# Schematic.net
KiCad netlist of a schematic drawn in Altium Designer
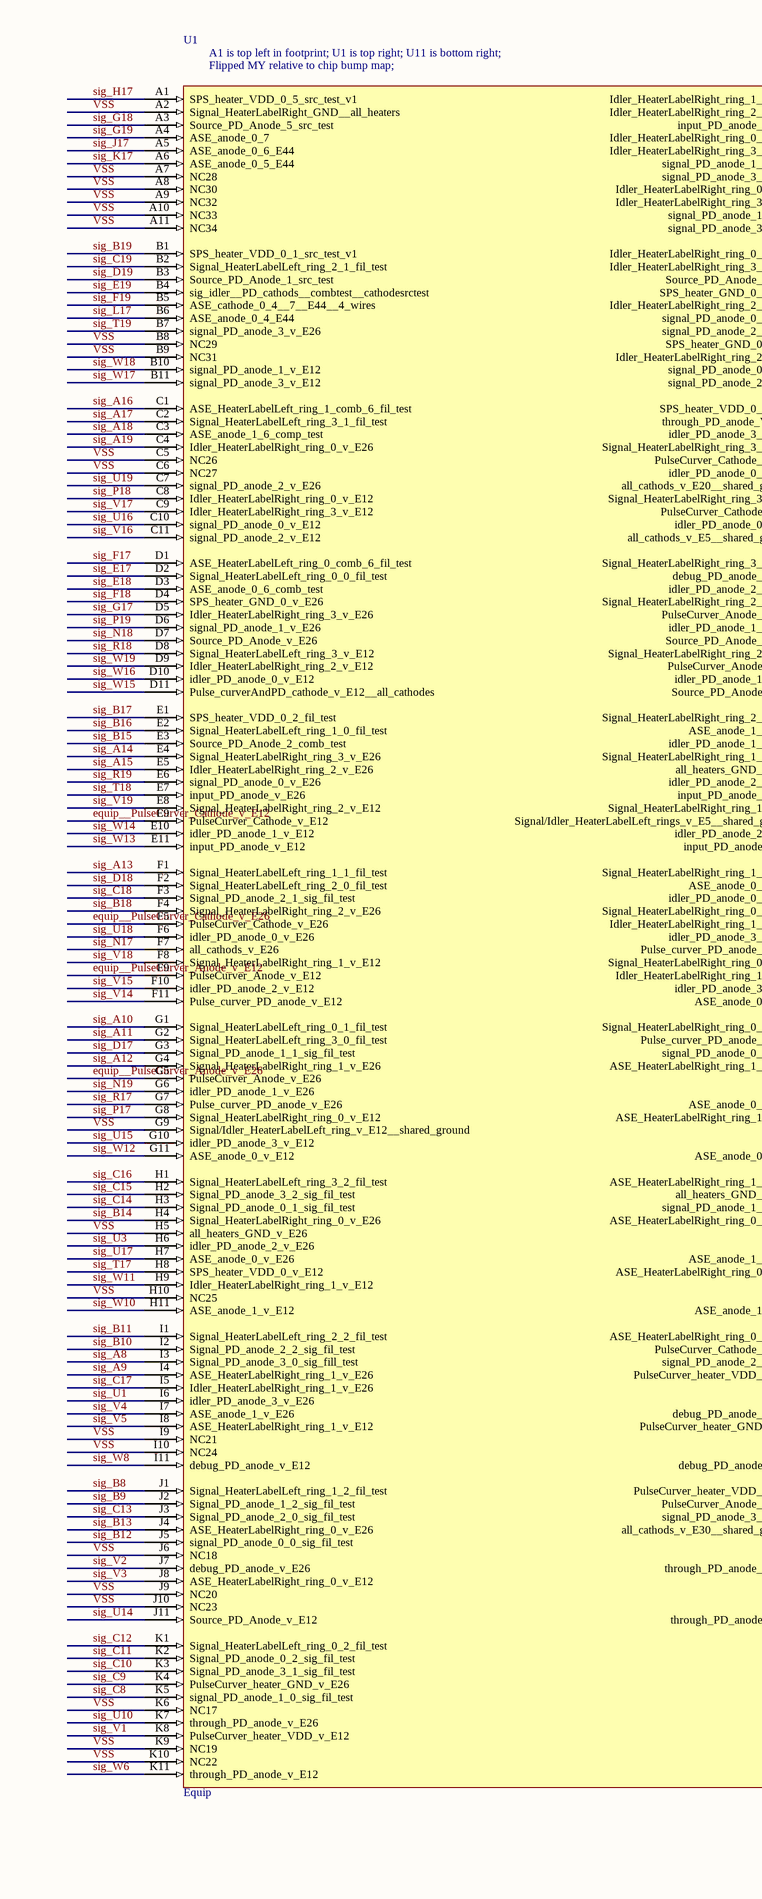
[diagram p0: Schematic.SchDoc, top left]
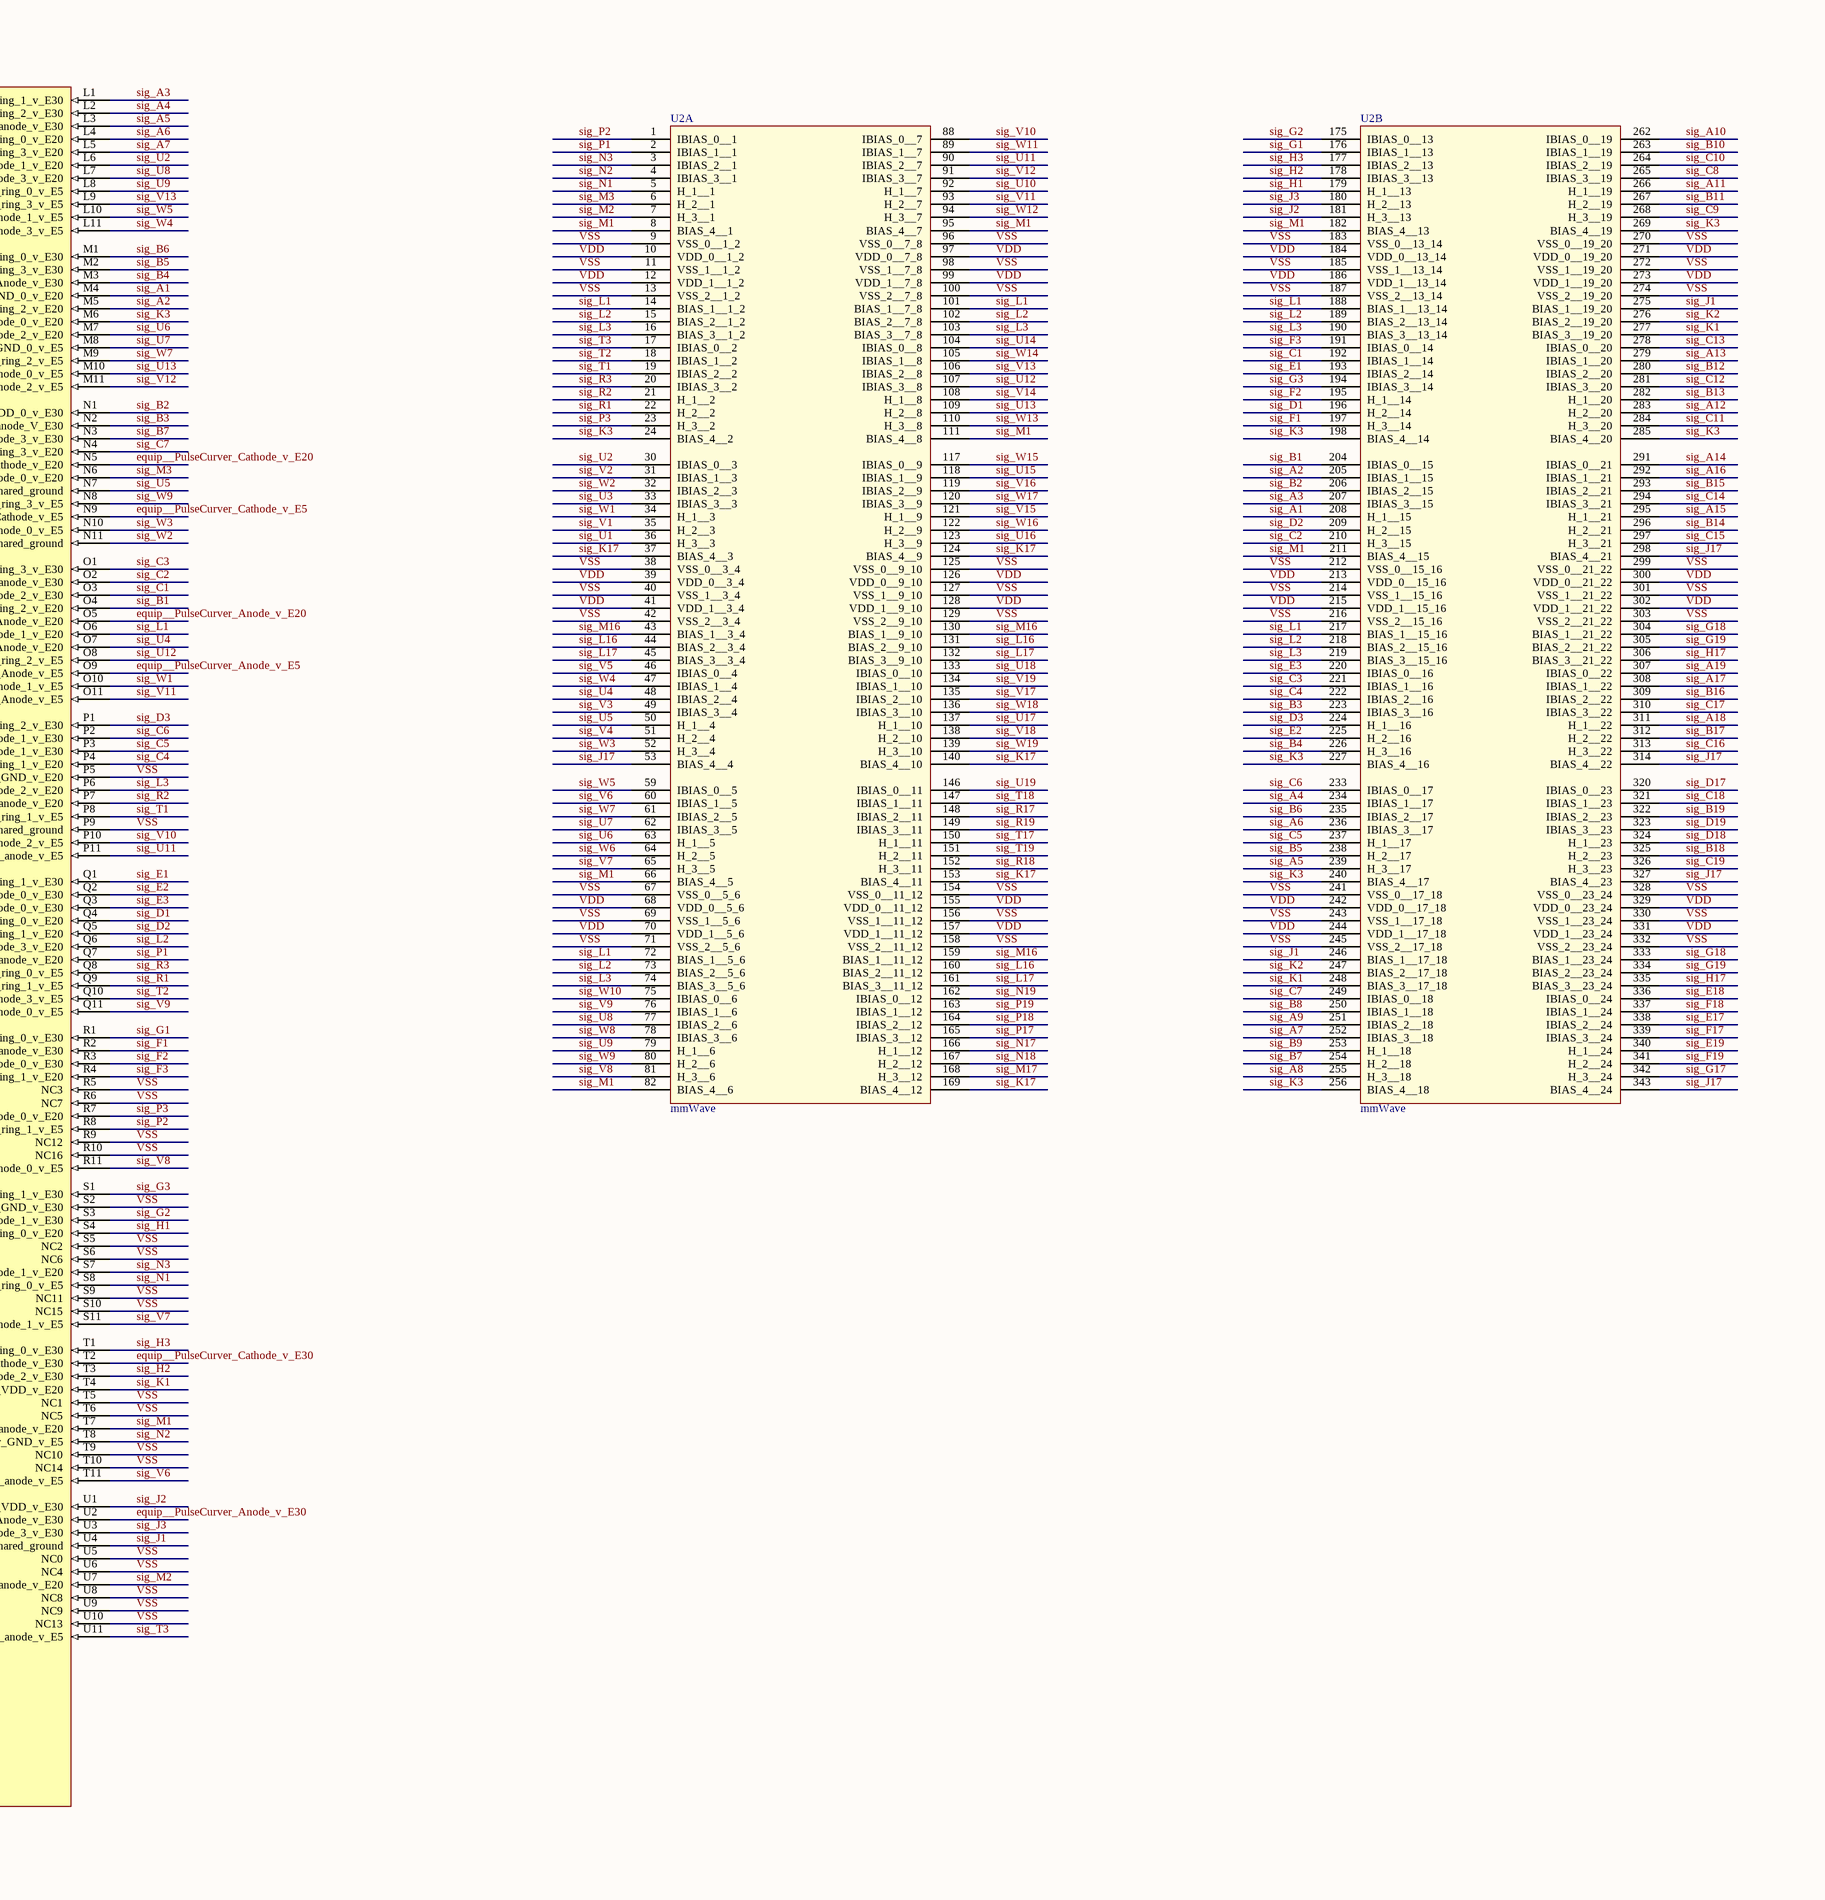
[diagram p1: Schematic.SchDoc, top middle]
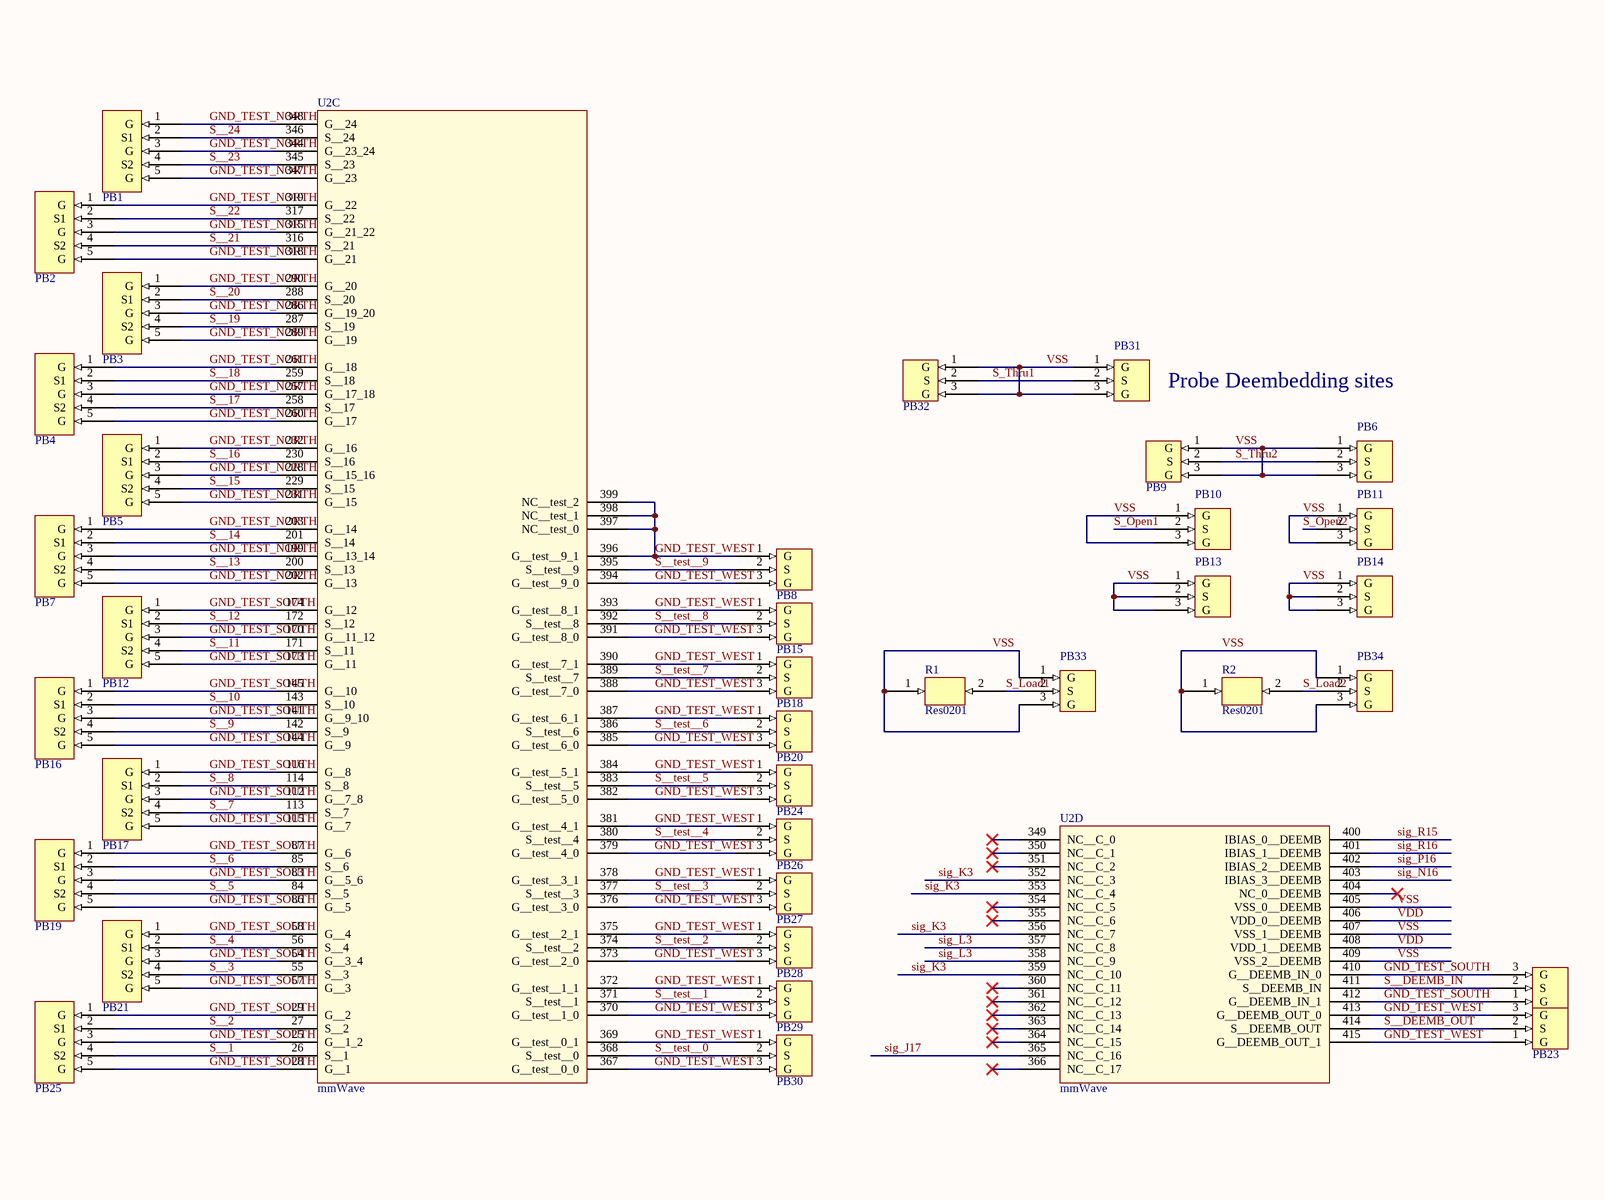
[diagram p2: Schematic.SchDoc, top right]
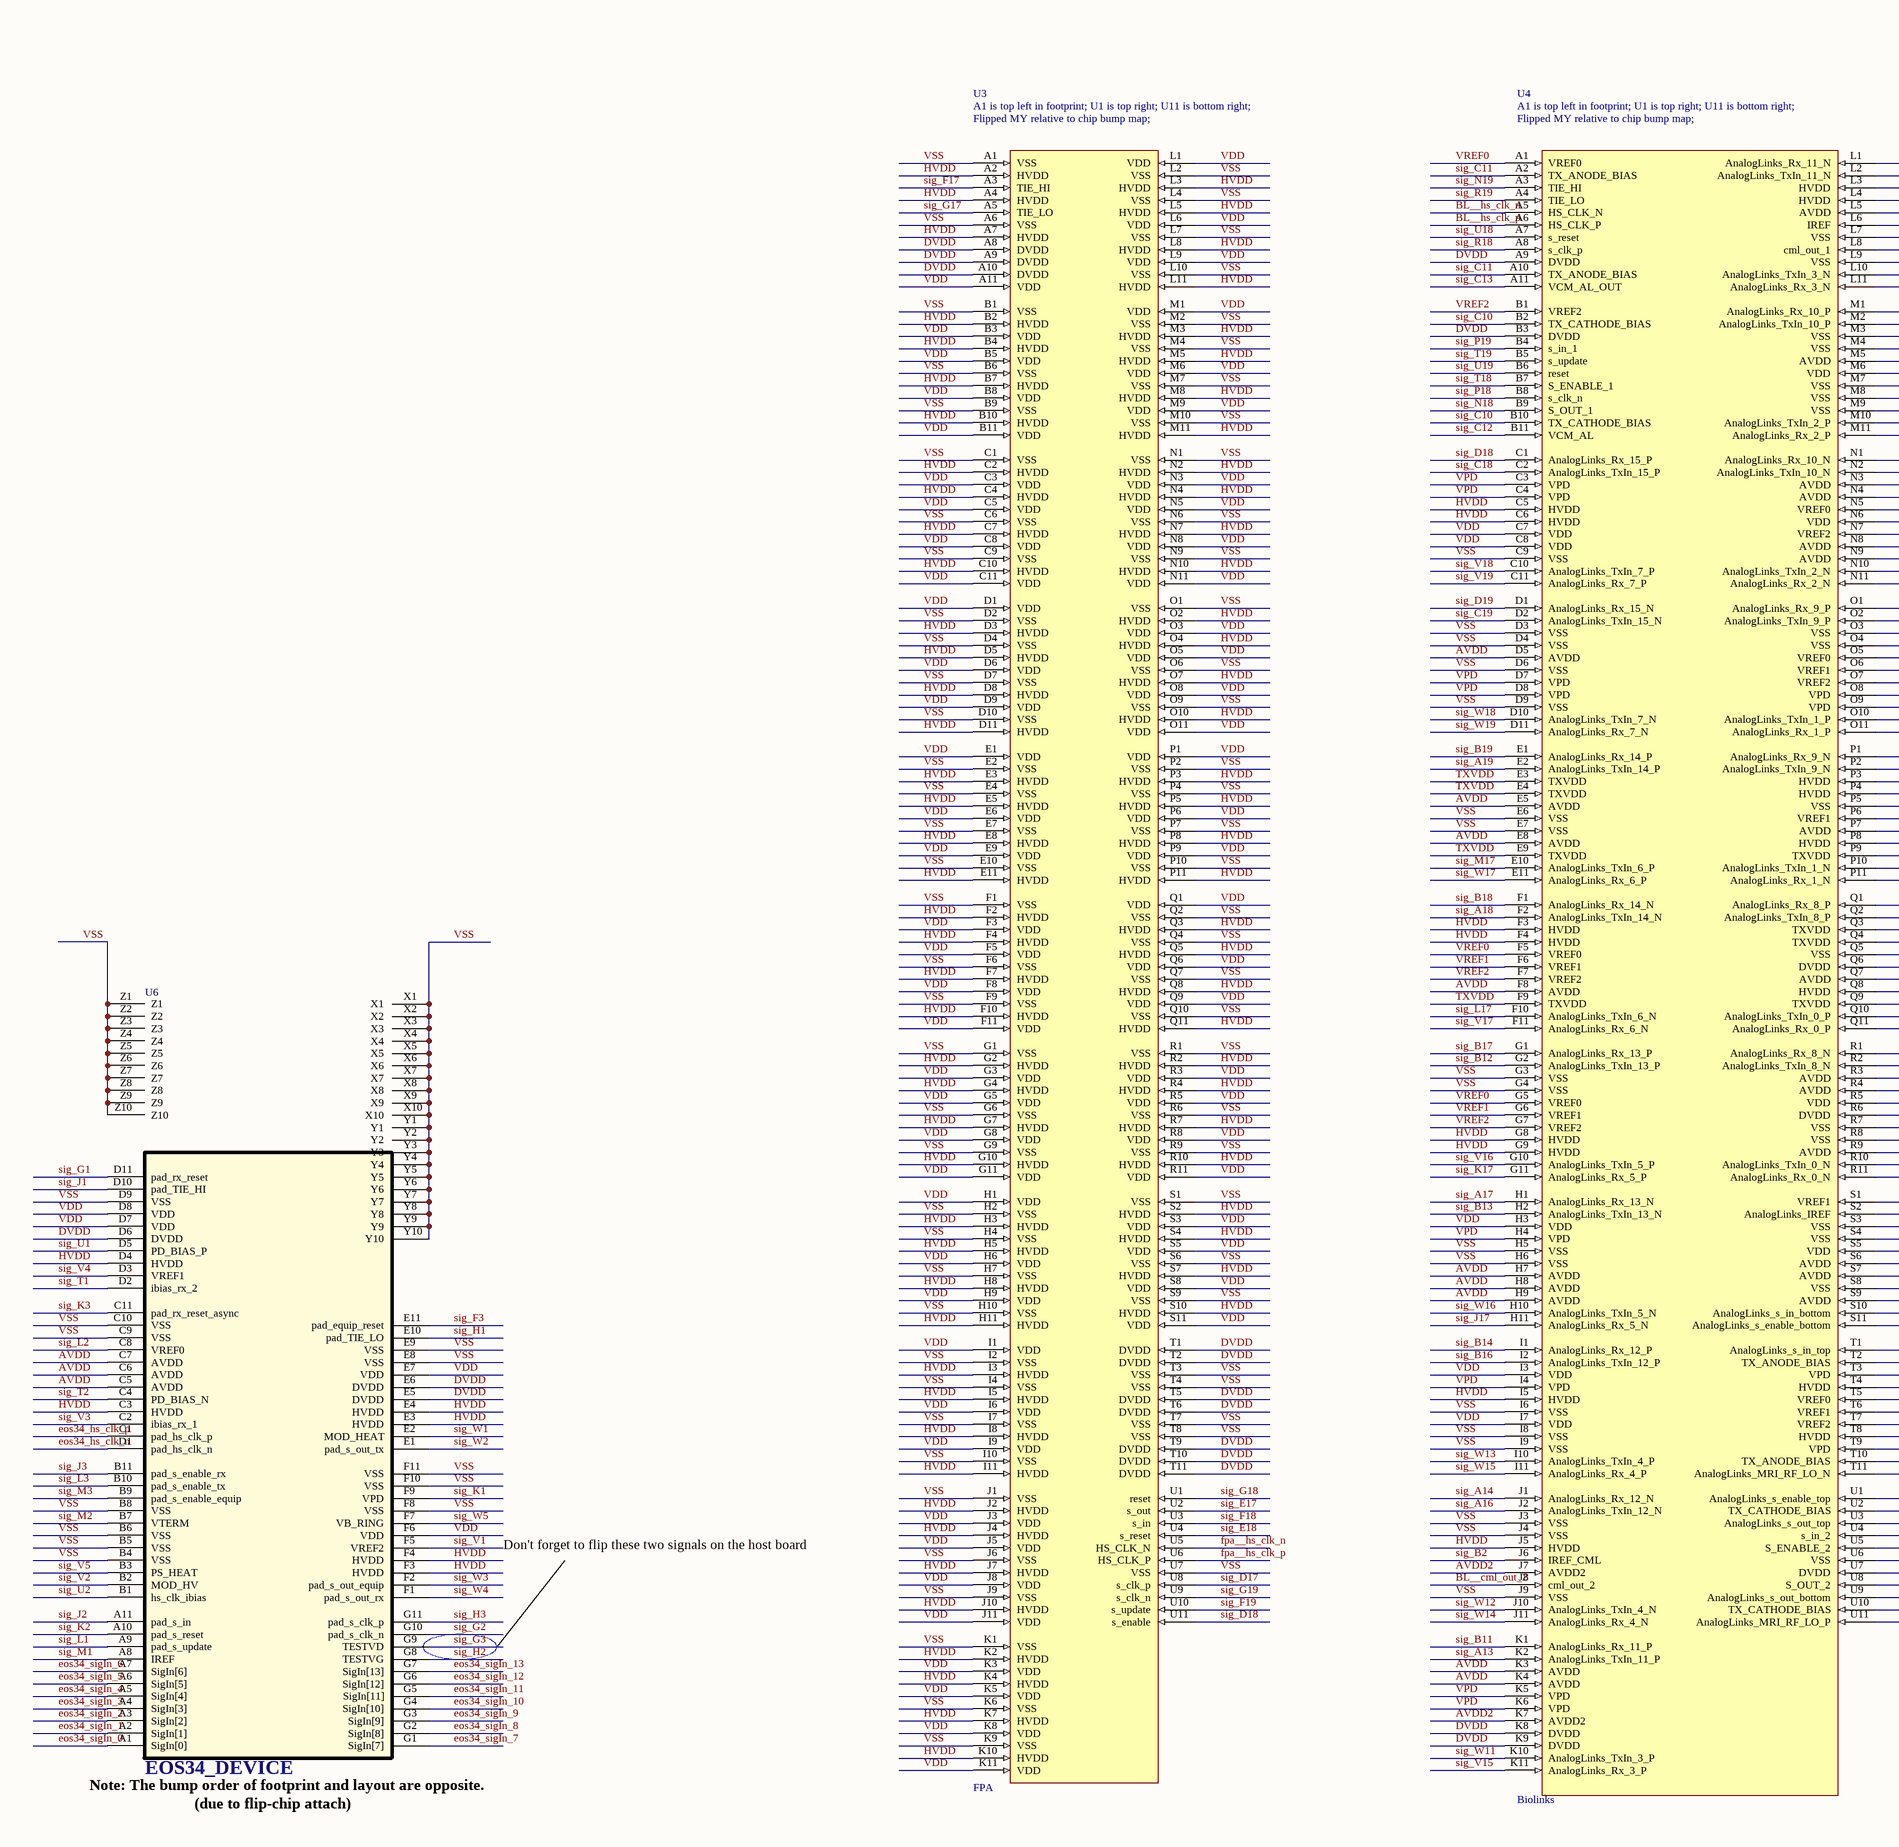
[diagram p3: Schematic.SchDoc, bottom left]
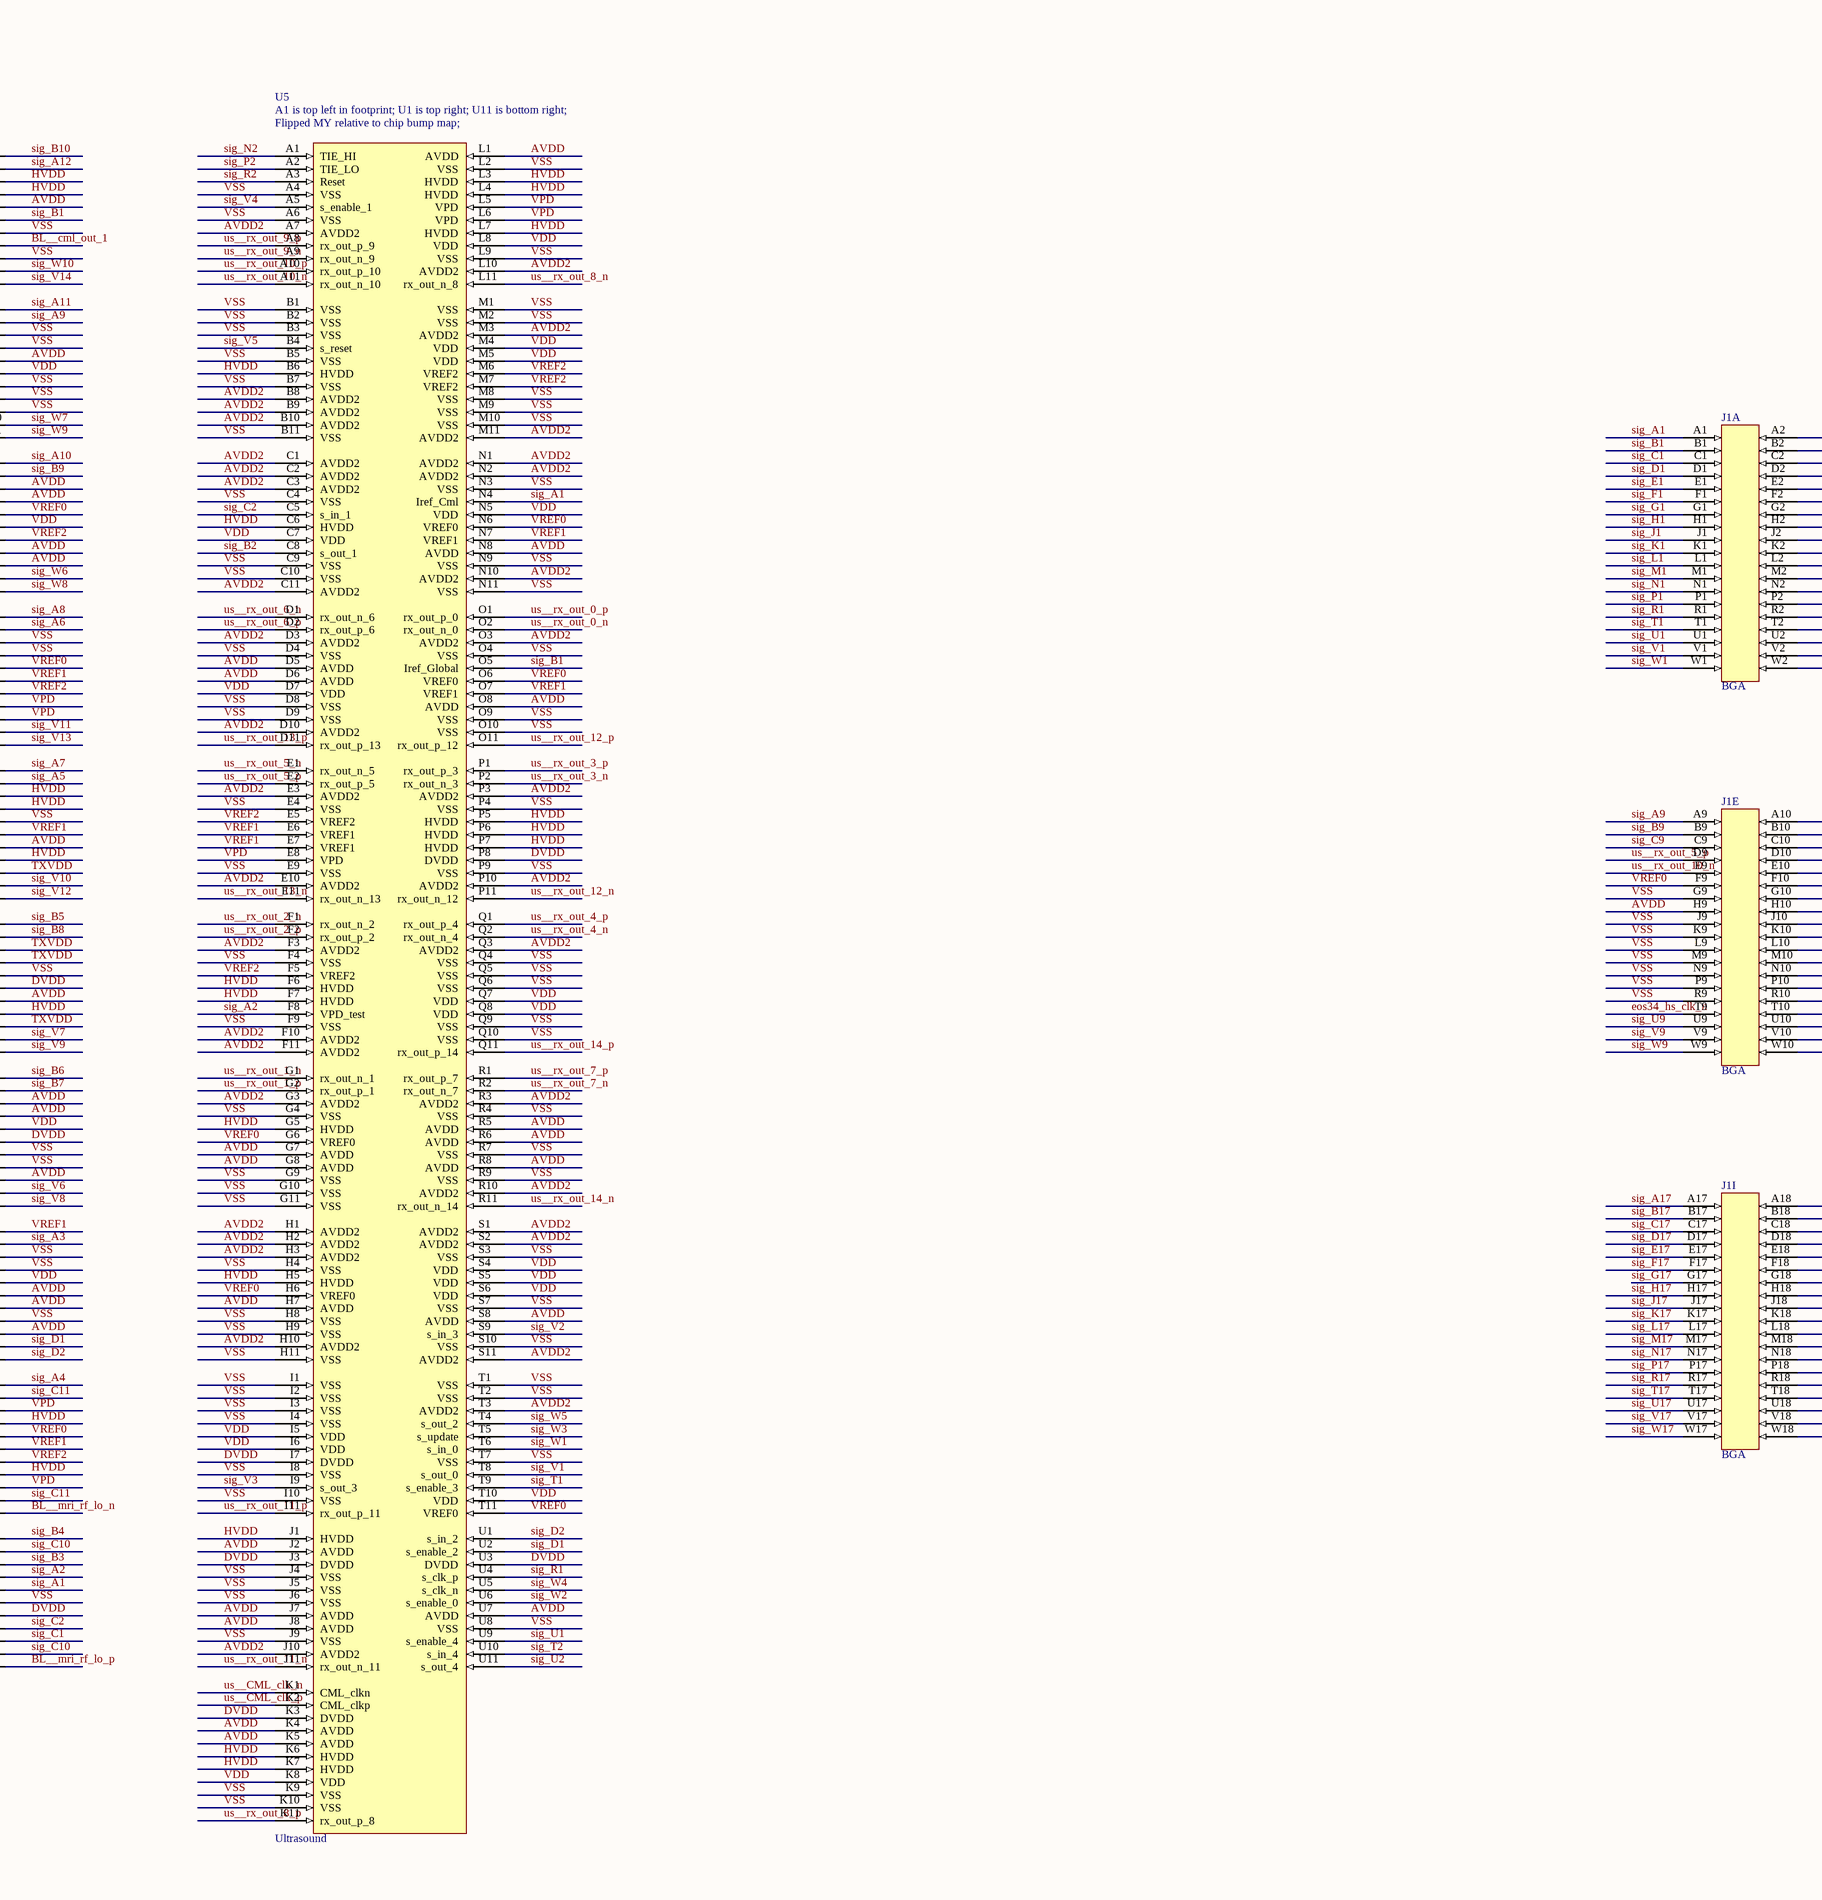
[diagram p4: Schematic.SchDoc, bottom middle]
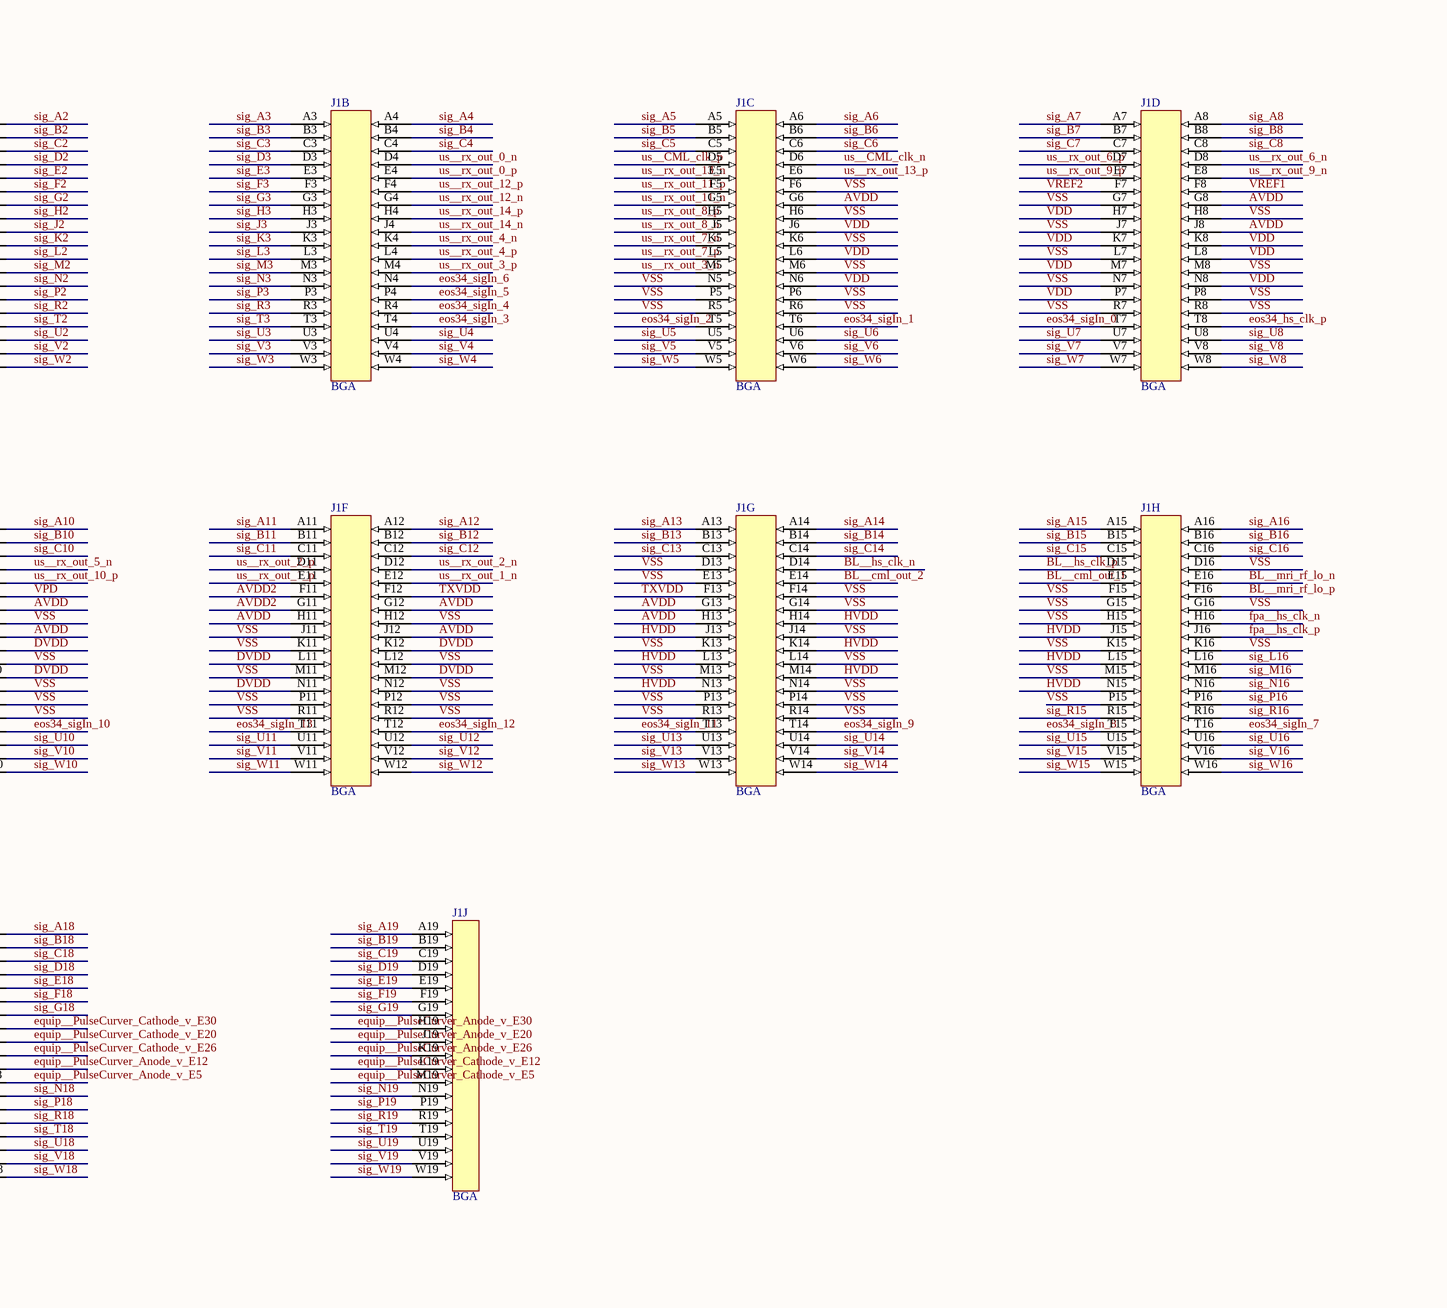
[diagram p5: Schematic.SchDoc, bottom right]

(export (version "E")
  (design (tool "Eeschema 10.0.6"))
  (components
    (comp (ref "J1") (value "BGA") (footprint "BGA361x19") (libsource (lib "Schlib") (part "BGA")))
    (comp (ref "PB1") (value "GSGSG") (footprint "GSGSG_Probe") (libsource (lib "Schlib") (part "GSGSG")))
    (comp (ref "PB2") (value "GSGSG") (footprint "GSGSG_Probe") (libsource (lib "Schlib") (part "GSGSG")))
    (comp (ref "PB3") (value "GSGSG") (footprint "GSGSG_Probe") (libsource (lib "Schlib") (part "GSGSG")))
    (comp (ref "PB4") (value "GSGSG") (footprint "GSGSG_Probe") (libsource (lib "Schlib") (part "GSGSG")))
    (comp (ref "PB5") (value "GSGSG") (footprint "GSGSG_Probe") (libsource (lib "Schlib") (part "GSGSG")))
    (comp (ref "PB6")
      (value "GSG_Probe_Pads")
      (footprint "GSG_Probe")
      (libsource (lib "") (part "GSG_Probe_Pads_1"))
    )
    (comp (ref "PB7") (value "GSGSG") (footprint "GSGSG_Probe") (libsource (lib "Schlib") (part "GSGSG")))
    (comp (ref "PB8")
      (value "GSG_Probe_Pads")
      (footprint "GSG_Probe")
      (libsource (lib "") (part "GSG_Probe_Pads_1"))
    )
    (comp (ref "PB9")
      (value "GSG_Probe_Pads")
      (footprint "GSG_Probe")
      (libsource (lib "") (part "GSG_Probe_Pads_2"))
    )
    (comp (ref "PB10")
      (value "GSG_Probe_Pads")
      (footprint "GSG_Probe")
      (libsource (lib "") (part "GSG_Probe_Pads_1"))
    )
    (comp (ref "PB11")
      (value "GSG_Probe_Pads")
      (footprint "GSG_Probe")
      (libsource (lib "") (part "GSG_Probe_Pads_1"))
    )
    (comp (ref "PB12") (value "GSGSG") (footprint "GSGSG_Probe") (libsource (lib "Schlib") (part "GSGSG")))
    (comp (ref "PB13")
      (value "GSG_Probe_Pads")
      (footprint "GSG_Probe")
      (libsource (lib "") (part "GSG_Probe_Pads_1"))
    )
    (comp (ref "PB14")
      (value "GSG_Probe_Pads")
      (footprint "GSG_Probe")
      (libsource (lib "") (part "GSG_Probe_Pads_1"))
    )
    (comp (ref "PB15")
      (value "GSG_Probe_Pads")
      (footprint "GSG_Probe")
      (libsource (lib "") (part "GSG_Probe_Pads_1"))
    )
    (comp (ref "PB16") (value "GSGSG") (footprint "GSGSG_Probe") (libsource (lib "Schlib") (part "GSGSG")))
    (comp (ref "PB17") (value "GSGSG") (footprint "GSGSG_Probe") (libsource (lib "Schlib") (part "GSGSG")))
    (comp (ref "PB18")
      (value "GSG_Probe_Pads")
      (footprint "GSG_Probe")
      (libsource (lib "") (part "GSG_Probe_Pads_1"))
    )
    (comp (ref "PB19") (value "GSGSG") (footprint "GSGSG_Probe") (libsource (lib "Schlib") (part "GSGSG")))
    (comp (ref "PB20")
      (value "GSG_Probe_Pads")
      (footprint "GSG_Probe")
      (libsource (lib "") (part "GSG_Probe_Pads_1"))
    )
    (comp (ref "PB21") (value "GSGSG") (footprint "GSGSG_Probe") (libsource (lib "Schlib") (part "GSGSG")))
    (comp (ref "PB22")
      (value "GSG_Probe_Pads")
      (footprint "GSG_Probe")
      (libsource (lib "Schlib") (part "GSG_Probe_Pads"))
    )
    (comp (ref "PB23")
      (value "GSG_Probe_Pads")
      (footprint "GSG_Probe")
      (libsource (lib "Schlib") (part "GSG_Probe_Pads"))
    )
    (comp (ref "PB24")
      (value "GSG_Probe_Pads")
      (footprint "GSG_Probe")
      (libsource (lib "") (part "GSG_Probe_Pads_1"))
    )
    (comp (ref "PB25") (value "GSGSG") (footprint "GSGSG_Probe") (libsource (lib "Schlib") (part "GSGSG")))
    (comp (ref "PB26")
      (value "GSG_Probe_Pads")
      (footprint "GSG_Probe")
      (libsource (lib "") (part "GSG_Probe_Pads_1"))
    )
    (comp (ref "PB27")
      (value "GSG_Probe_Pads")
      (footprint "GSG_Probe")
      (libsource (lib "") (part "GSG_Probe_Pads_1"))
    )
    (comp (ref "PB28")
      (value "GSG_Probe_Pads")
      (footprint "GSG_Probe")
      (libsource (lib "") (part "GSG_Probe_Pads_1"))
    )
    (comp (ref "PB29")
      (value "GSG_Probe_Pads")
      (footprint "GSG_Probe")
      (libsource (lib "") (part "GSG_Probe_Pads_1"))
    )
    (comp (ref "PB30")
      (value "GSG_Probe_Pads")
      (footprint "GSG_Probe")
      (libsource (lib "") (part "GSG_Probe_Pads_1"))
    )
    (comp (ref "PB31")
      (value "GSG_Probe_Pads")
      (footprint "GSG_Probe")
      (libsource (lib "") (part "GSG_Probe_Pads_1"))
    )
    (comp (ref "PB32")
      (value "GSG_Probe_Pads")
      (footprint "GSG_Probe")
      (libsource (lib "") (part "GSG_Probe_Pads_2"))
    )
    (comp (ref "PB33")
      (value "GSG_Probe_Pads")
      (footprint "GSG_Probe")
      (libsource (lib "") (part "GSG_Probe_Pads_1"))
    )
    (comp (ref "PB34")
      (value "GSG_Probe_Pads")
      (footprint "GSG_Probe")
      (libsource (lib "") (part "GSG_Probe_Pads_1"))
    )
    (comp (ref "R1") (value "Res0201") (footprint "Res0201_V2") (libsource (lib "Schlib") (part "Res0201")))
    (comp (ref "R2") (value "Res0201") (footprint "Res0201_V2") (libsource (lib "Schlib") (part "Res0201")))
    (comp (ref "U1") (value "Equip") (footprint "Bart_Bravo") (libsource (lib "Schlib") (part "Equip")))
    (comp (ref "U2") (value "mmWave") (footprint "mmWave") (libsource (lib "Schlib") (part "mmWave")))
    (comp (ref "U3") (value "FPA") (footprint "Bart_Bravo") (libsource (lib "Schlib") (part "FPA")))
    (comp (ref "U4") (value "Biolinks") (footprint "Bart_Bravo") (libsource (lib "Schlib") (part "Biolinks")))
    (comp (ref "U5")
      (value "Ultrasound")
      (footprint "Bart_Bravo")
      (libsource (lib "Schlib") (part "Ultrasound"))
    )
    (comp (ref "U6")
      (value "EOS34_DEVICE")
      (footprint "EOS34_device")
      (libsource (lib "Schlib") (part "EOS34_DEVICE"))
    )
  )
  (nets
    (net (code "1") (name "/AVDD") (class "Default")
      (node (ref "J1") (pin "G10") (pintype "input"))
      (node (ref "J1") (pin "G12") (pintype "input"))
      (node (ref "J1") (pin "G13") (pintype "input"))
      (node (ref "J1") (pin "G6") (pintype "input"))
      (node (ref "J1") (pin "G8") (pintype "input"))
      (node (ref "J1") (pin "H11") (pintype "input"))
      (node (ref "J1") (pin "H13") (pintype "input"))
      (node (ref "J1") (pin "H9") (pintype "input"))
      (node (ref "J1") (pin "J10") (pintype "input"))
      (node (ref "J1") (pin "J12") (pintype "input"))
      (node (ref "J1") (pin "J8") (pintype "input"))
      (node (ref "U4") (pin "D5") (pinfunction "AVDD_D5") (pintype "input"))
      (node (ref "U4") (pin "E5") (pinfunction "AVDD_E5") (pintype "input"))
      (node (ref "U4") (pin "E8") (pinfunction "AVDD_E8") (pintype "input"))
      (node (ref "U4") (pin "F8") (pinfunction "AVDD_F8") (pintype "input"))
      (node (ref "U4") (pin "H7") (pinfunction "AVDD_H7") (pintype "input"))
      (node (ref "U4") (pin "H8") (pinfunction "AVDD_H8") (pintype "input"))
      (node (ref "U4") (pin "H9") (pinfunction "AVDD_H9") (pintype "input"))
      (node (ref "U4") (pin "K3") (pinfunction "AVDD_K3") (pintype "input"))
      (node (ref "U4") (pin "K4") (pinfunction "AVDD_K4") (pintype "input"))
      (node (ref "U4") (pin "L5") (pinfunction "AVDD_L5") (pintype "input"))
      (node (ref "U4") (pin "M5") (pinfunction "AVDD_M5") (pintype "input"))
      (node (ref "U4") (pin "N3") (pinfunction "AVDD_N3") (pintype "input"))
      (node (ref "U4") (pin "N4") (pinfunction "AVDD_N4") (pintype "input"))
      (node (ref "U4") (pin "N8") (pinfunction "AVDD_N8") (pintype "input"))
      (node (ref "U4") (pin "N9") (pinfunction "AVDD_N9") (pintype "input"))
      (node (ref "U4") (pin "P7") (pinfunction "AVDD_P7") (pintype "input"))
      (node (ref "U4") (pin "Q7") (pinfunction "AVDD_Q7") (pintype "input"))
      (node (ref "U4") (pin "R3") (pinfunction "AVDD_R3") (pintype "input"))
      (node (ref "U4") (pin "R4") (pinfunction "AVDD_R4") (pintype "input"))
      (node (ref "U4") (pin "R9") (pinfunction "AVDD_R9") (pintype "input"))
      (node (ref "U4") (pin "S6") (pinfunction "AVDD_S6") (pintype "input"))
      (node (ref "U4") (pin "S7") (pinfunction "AVDD_S7") (pintype "input"))
      (node (ref "U4") (pin "S9") (pinfunction "AVDD_S9") (pintype "input"))
      (node (ref "U5") (pin "D5") (pinfunction "AVDD_D5") (pintype "input"))
      (node (ref "U5") (pin "D6") (pinfunction "AVDD_D6") (pintype "input"))
      (node (ref "U5") (pin "G7") (pinfunction "AVDD_G7") (pintype "input"))
      (node (ref "U5") (pin "G8") (pinfunction "AVDD_G8") (pintype "input"))
      (node (ref "U5") (pin "H7") (pinfunction "AVDD_H7") (pintype "input"))
      (node (ref "U5") (pin "J2") (pinfunction "AVDD_J2") (pintype "input"))
      (node (ref "U5") (pin "J7") (pinfunction "AVDD_J7") (pintype "input"))
      (node (ref "U5") (pin "J8") (pinfunction "AVDD_J8") (pintype "input"))
      (node (ref "U5") (pin "K4") (pinfunction "AVDD_K4") (pintype "input"))
      (node (ref "U5") (pin "K5") (pinfunction "AVDD_K5") (pintype "input"))
      (node (ref "U5") (pin "L1") (pinfunction "AVDD_L1") (pintype "input"))
      (node (ref "U5") (pin "N8") (pinfunction "AVDD_N8") (pintype "input"))
      (node (ref "U5") (pin "O8") (pinfunction "AVDD_O8") (pintype "input"))
      (node (ref "U5") (pin "R5") (pinfunction "AVDD_R5") (pintype "input"))
      (node (ref "U5") (pin "R6") (pinfunction "AVDD_R6") (pintype "input"))
      (node (ref "U5") (pin "R8") (pinfunction "AVDD_R8") (pintype "input"))
      (node (ref "U5") (pin "S8") (pinfunction "AVDD_S8") (pintype "input"))
      (node (ref "U5") (pin "U7") (pinfunction "AVDD_U7") (pintype "input"))
      (node (ref "U6") (pin "C5") (pinfunction "AVDD_C5") (pintype "passive"))
      (node (ref "U6") (pin "C6") (pinfunction "AVDD_C6") (pintype "passive"))
      (node (ref "U6") (pin "C7") (pinfunction "AVDD_C7") (pintype "passive"))
    )
    (net (code "2") (name "/AVDD2") (class "Default")
      (node (ref "J1") (pin "F11") (pintype "input"))
      (node (ref "J1") (pin "G11") (pintype "input"))
      (node (ref "U4") (pin "J7") (pinfunction "AVDD2_J7") (pintype "input"))
      (node (ref "U4") (pin "K7") (pinfunction "AVDD2_K7") (pintype "input"))
      (node (ref "U5") (pin "A7") (pinfunction "AVDD2_A7") (pintype "input"))
      (node (ref "U5") (pin "B10") (pinfunction "AVDD2_B10") (pintype "input"))
      (node (ref "U5") (pin "B8") (pinfunction "AVDD2_B8") (pintype "input"))
      (node (ref "U5") (pin "B9") (pinfunction "AVDD2_B9") (pintype "input"))
      (node (ref "U5") (pin "C1") (pinfunction "AVDD2_C1") (pintype "input"))
      (node (ref "U5") (pin "C11") (pinfunction "AVDD2_C11") (pintype "input"))
      (node (ref "U5") (pin "C2") (pinfunction "AVDD2_C2") (pintype "input"))
      (node (ref "U5") (pin "C3") (pinfunction "AVDD2_C3") (pintype "input"))
      (node (ref "U5") (pin "D10") (pinfunction "AVDD2_D10") (pintype "input"))
      (node (ref "U5") (pin "D3") (pinfunction "AVDD2_D3") (pintype "input"))
      (node (ref "U5") (pin "E10") (pinfunction "AVDD2_E10") (pintype "input"))
      (node (ref "U5") (pin "E3") (pinfunction "AVDD2_E3") (pintype "input"))
      (node (ref "U5") (pin "F10") (pinfunction "AVDD2_F10") (pintype "input"))
      (node (ref "U5") (pin "F11") (pinfunction "AVDD2_F11") (pintype "input"))
      (node (ref "U5") (pin "F3") (pinfunction "AVDD2_F3") (pintype "input"))
      (node (ref "U5") (pin "G3") (pinfunction "AVDD2_G3") (pintype "input"))
      (node (ref "U5") (pin "H1") (pinfunction "AVDD2_H1") (pintype "input"))
      (node (ref "U5") (pin "H10") (pinfunction "AVDD2_H10") (pintype "input"))
      (node (ref "U5") (pin "H2") (pinfunction "AVDD2_H2") (pintype "input"))
      (node (ref "U5") (pin "H3") (pinfunction "AVDD2_H3") (pintype "input"))
      (node (ref "U5") (pin "J10") (pinfunction "AVDD2_J10") (pintype "input"))
      (node (ref "U5") (pin "L10") (pinfunction "AVDD2_L10") (pintype "input"))
      (node (ref "U5") (pin "M11") (pinfunction "AVDD2_M11") (pintype "input"))
      (node (ref "U5") (pin "M3") (pinfunction "AVDD2_M3") (pintype "input"))
      (node (ref "U5") (pin "N1") (pinfunction "AVDD2_N1") (pintype "input"))
      (node (ref "U5") (pin "N10") (pinfunction "AVDD2_N10") (pintype "input"))
      (node (ref "U5") (pin "N2") (pinfunction "AVDD2_N2") (pintype "input"))
      (node (ref "U5") (pin "O3") (pinfunction "AVDD2_O3") (pintype "input"))
      (node (ref "U5") (pin "P10") (pinfunction "AVDD2_P10") (pintype "input"))
      (node (ref "U5") (pin "P3") (pinfunction "AVDD2_P3") (pintype "input"))
      (node (ref "U5") (pin "Q3") (pinfunction "AVDD2_Q3") (pintype "input"))
      (node (ref "U5") (pin "R10") (pinfunction "AVDD2_R10") (pintype "input"))
      (node (ref "U5") (pin "R3") (pinfunction "AVDD2_R3") (pintype "input"))
      (node (ref "U5") (pin "S1") (pinfunction "AVDD2_S1") (pintype "input"))
      (node (ref "U5") (pin "S11") (pinfunction "AVDD2_S11") (pintype "input"))
      (node (ref "U5") (pin "S2") (pinfunction "AVDD2_S2") (pintype "input"))
      (node (ref "U5") (pin "T3") (pinfunction "AVDD2_T3") (pintype "input"))
    )
    (net (code "3") (name "/BL__cml_out_1") (class "Default")
      (node (ref "J1") (pin "E15") (pintype "input"))
      (node (ref "U4") (pin "L8") (pinfunction "cml_out_1_L8") (pintype "input"))
    )
    (net (code "4") (name "/BL__cml_out_2") (class "Default")
      (node (ref "J1") (pin "E14") (pintype "input"))
      (node (ref "U4") (pin "J8") (pinfunction "cml_out_2_J8") (pintype "input"))
    )
    (net (code "5") (name "/BL__hs_clk_n") (class "Default")
      (node (ref "J1") (pin "D14") (pintype "input"))
      (node (ref "U4") (pin "A5") (pinfunction "HS_CLK_N_A5") (pintype "input"))
    )
    (net (code "6") (name "/BL__hs_clk_p") (class "Default")
      (node (ref "J1") (pin "D15") (pintype "input"))
      (node (ref "U4") (pin "A6") (pinfunction "HS_CLK_P_A6") (pintype "input"))
    )
    (net (code "7") (name "/BL__mri_rf_lo_n") (class "Default")
      (node (ref "J1") (pin "E16") (pintype "input"))
      (node (ref "U4") (pin "T11") (pinfunction "AnalogLinks_MRI_RF_LO_N_T11") (pintype "input"))
    )
    (net (code "8") (name "/BL__mri_rf_lo_p") (class "Default")
      (node (ref "J1") (pin "F16") (pintype "input"))
      (node (ref "U4") (pin "U11") (pinfunction "AnalogLinks_MRI_RF_LO_P_U11") (pintype "input"))
    )
    (net (code "9") (name "/DVDD") (class "Default")
      (node (ref "J1") (pin "K10") (pintype "input"))
      (node (ref "J1") (pin "K12") (pintype "input"))
      (node (ref "J1") (pin "L11") (pintype "input"))
      (node (ref "J1") (pin "M10") (pintype "input"))
      (node (ref "J1") (pin "M12") (pintype "input"))
      (node (ref "J1") (pin "N11") (pintype "input"))
      (node (ref "U3") (pin "A10") (pinfunction "DVDD_A10") (pintype "input"))
      (node (ref "U3") (pin "A8") (pinfunction "DVDD_A8") (pintype "input"))
      (node (ref "U3") (pin "A9") (pinfunction "DVDD_A9") (pintype "input"))
      (node (ref "U3") (pin "T1") (pinfunction "DVDD_T1") (pintype "input"))
      (node (ref "U3") (pin "T10") (pinfunction "DVDD_T10") (pintype "input"))
      (node (ref "U3") (pin "T11") (pinfunction "DVDD_T11") (pintype "input"))
      (node (ref "U3") (pin "T2") (pinfunction "DVDD_T2") (pintype "input"))
      (node (ref "U3") (pin "T5") (pinfunction "DVDD_T5") (pintype "input"))
      (node (ref "U3") (pin "T6") (pinfunction "DVDD_T6") (pintype "input"))
      (node (ref "U3") (pin "T9") (pinfunction "DVDD_T9") (pintype "input"))
      (node (ref "U4") (pin "A9") (pinfunction "DVDD_A9") (pintype "input"))
      (node (ref "U4") (pin "B3") (pinfunction "DVDD_B3") (pintype "input"))
      (node (ref "U4") (pin "K8") (pinfunction "DVDD_K8") (pintype "input"))
      (node (ref "U4") (pin "K9") (pinfunction "DVDD_K9") (pintype "input"))
      (node (ref "U4") (pin "Q6") (pinfunction "DVDD_Q6") (pintype "input"))
      (node (ref "U4") (pin "R6") (pinfunction "DVDD_R6") (pintype "input"))
      (node (ref "U4") (pin "U7") (pinfunction "DVDD_U7") (pintype "input"))
      (node (ref "U5") (pin "I7") (pinfunction "DVDD_I7") (pintype "input"))
      (node (ref "U5") (pin "J3") (pinfunction "DVDD_J3") (pintype "input"))
      (node (ref "U5") (pin "K3") (pinfunction "DVDD_K3") (pintype "input"))
      (node (ref "U5") (pin "P8") (pinfunction "DVDD_P8") (pintype "input"))
      (node (ref "U5") (pin "U3") (pinfunction "DVDD_U3") (pintype "input"))
      (node (ref "U6") (pin "D6") (pinfunction "DVDD_D6") (pintype "passive"))
      (node (ref "U6") (pin "E5") (pinfunction "DVDD_E5") (pintype "passive"))
      (node (ref "U6") (pin "E6") (pinfunction "DVDD_E6") (pintype "passive"))
    )
    (net (code "10") (name "/GND_TEST_NORTH") (class "Default")
      (node (ref "PB1") (pin "1") (pinfunction "G_1") (pintype "input"))
      (node (ref "PB1") (pin "3") (pinfunction "G_3") (pintype "input"))
      (node (ref "PB1") (pin "5") (pinfunction "G_5") (pintype "input"))
      (node (ref "PB2") (pin "1") (pinfunction "G_1") (pintype "input"))
      (node (ref "PB2") (pin "3") (pinfunction "G_3") (pintype "input"))
      (node (ref "PB2") (pin "5") (pinfunction "G_5") (pintype "input"))
      (node (ref "PB3") (pin "1") (pinfunction "G_1") (pintype "input"))
      (node (ref "PB3") (pin "3") (pinfunction "G_3") (pintype "input"))
      (node (ref "PB3") (pin "5") (pinfunction "G_5") (pintype "input"))
      (node (ref "PB4") (pin "1") (pinfunction "G_1") (pintype "input"))
      (node (ref "PB4") (pin "3") (pinfunction "G_3") (pintype "input"))
      (node (ref "PB4") (pin "5") (pinfunction "G_5") (pintype "input"))
      (node (ref "PB5") (pin "1") (pinfunction "G_1") (pintype "input"))
      (node (ref "PB5") (pin "3") (pinfunction "G_3") (pintype "input"))
      (node (ref "PB5") (pin "5") (pinfunction "G_5") (pintype "input"))
      (node (ref "PB7") (pin "1") (pinfunction "G_1") (pintype "input"))
      (node (ref "PB7") (pin "3") (pinfunction "G_3") (pintype "input"))
      (node (ref "PB7") (pin "5") (pinfunction "G_5") (pintype "input"))
      (node (ref "U2") (pin "199") (pinfunction "G__13_14_199") (pintype "passive"))
      (node (ref "U2") (pin "202") (pinfunction "G__13_202") (pintype "passive"))
      (node (ref "U2") (pin "203") (pinfunction "G__14_203") (pintype "passive"))
      (node (ref "U2") (pin "228") (pinfunction "G__15_16_228") (pintype "passive"))
      (node (ref "U2") (pin "231") (pinfunction "G__15_231") (pintype "passive"))
      (node (ref "U2") (pin "232") (pinfunction "G__16_232") (pintype "passive"))
      (node (ref "U2") (pin "257") (pinfunction "G__17_18_257") (pintype "passive"))
      (node (ref "U2") (pin "260") (pinfunction "G__17_260") (pintype "passive"))
      (node (ref "U2") (pin "261") (pinfunction "G__18_261") (pintype "passive"))
      (node (ref "U2") (pin "286") (pinfunction "G__19_20_286") (pintype "passive"))
      (node (ref "U2") (pin "289") (pinfunction "G__19_289") (pintype "passive"))
      (node (ref "U2") (pin "290") (pinfunction "G__20_290") (pintype "passive"))
      (node (ref "U2") (pin "315") (pinfunction "G__21_22_315") (pintype "passive"))
      (node (ref "U2") (pin "318") (pinfunction "G__21_318") (pintype "passive"))
      (node (ref "U2") (pin "319") (pinfunction "G__22_319") (pintype "passive"))
      (node (ref "U2") (pin "344") (pinfunction "G__23_24_344") (pintype "passive"))
      (node (ref "U2") (pin "347") (pinfunction "G__23_347") (pintype "passive"))
      (node (ref "U2") (pin "348") (pinfunction "G__24_348") (pintype "passive"))
    )
    (net (code "11") (name "/GND_TEST_SOUTH") (class "Default")
      (node (ref "PB12") (pin "1") (pinfunction "G_1") (pintype "input"))
      (node (ref "PB12") (pin "3") (pinfunction "G_3") (pintype "input"))
      (node (ref "PB12") (pin "5") (pinfunction "G_5") (pintype "input"))
      (node (ref "PB16") (pin "1") (pinfunction "G_1") (pintype "input"))
      (node (ref "PB16") (pin "3") (pinfunction "G_3") (pintype "input"))
      (node (ref "PB16") (pin "5") (pinfunction "G_5") (pintype "input"))
      (node (ref "PB17") (pin "1") (pinfunction "G_1") (pintype "input"))
      (node (ref "PB17") (pin "3") (pinfunction "G_3") (pintype "input"))
      (node (ref "PB17") (pin "5") (pinfunction "G_5") (pintype "input"))
      (node (ref "PB19") (pin "1") (pinfunction "G_1") (pintype "input"))
      (node (ref "PB19") (pin "3") (pinfunction "G_3") (pintype "input"))
      (node (ref "PB19") (pin "5") (pinfunction "G_5") (pintype "input"))
      (node (ref "PB21") (pin "1") (pinfunction "G_1") (pintype "input"))
      (node (ref "PB21") (pin "3") (pinfunction "G_3") (pintype "input"))
      (node (ref "PB21") (pin "5") (pinfunction "G_5") (pintype "input"))
      (node (ref "PB22") (pin "1") (pinfunction "G_1") (pintype "input"))
      (node (ref "PB22") (pin "3") (pinfunction "G_3") (pintype "input"))
      (node (ref "PB25") (pin "1") (pinfunction "G_1") (pintype "input"))
      (node (ref "PB25") (pin "3") (pinfunction "G_3") (pintype "input"))
      (node (ref "PB25") (pin "5") (pinfunction "G_5") (pintype "input"))
      (node (ref "U2") (pin "112") (pinfunction "G__7_8_112") (pintype "passive"))
      (node (ref "U2") (pin "115") (pinfunction "G__7_115") (pintype "passive"))
      (node (ref "U2") (pin "116") (pinfunction "G__8_116") (pintype "passive"))
      (node (ref "U2") (pin "141") (pinfunction "G__9_10_141") (pintype "passive"))
      (node (ref "U2") (pin "144") (pinfunction "G__9_144") (pintype "passive"))
      (node (ref "U2") (pin "145") (pinfunction "G__10_145") (pintype "passive"))
      (node (ref "U2") (pin "170") (pinfunction "G__11_12_170") (pintype "passive"))
      (node (ref "U2") (pin "173") (pinfunction "G__11_173") (pintype "passive"))
      (node (ref "U2") (pin "174") (pinfunction "G__12_174") (pintype "passive"))
      (node (ref "U2") (pin "25") (pinfunction "G__1_2_25") (pintype "passive"))
      (node (ref "U2") (pin "28") (pinfunction "G__1_28") (pintype "passive"))
      (node (ref "U2") (pin "29") (pinfunction "G__2_29") (pintype "passive"))
      (node (ref "U2") (pin "410") (pinfunction "G__DEEMB_IN_0_410") (pintype "passive"))
      (node (ref "U2") (pin "412") (pinfunction "G__DEEMB_IN_1_412") (pintype "passive"))
      (node (ref "U2") (pin "54") (pinfunction "G__3_4_54") (pintype "passive"))
      (node (ref "U2") (pin "57") (pinfunction "G__3_57") (pintype "passive"))
      (node (ref "U2") (pin "58") (pinfunction "G__4_58") (pintype "passive"))
      (node (ref "U2") (pin "83") (pinfunction "G__5_6_83") (pintype "passive"))
      (node (ref "U2") (pin "86") (pinfunction "G__5_86") (pintype "passive"))
      (node (ref "U2") (pin "87") (pinfunction "G__6_87") (pintype "passive"))
    )
    (net (code "12") (name "/GND_TEST_WEST") (class "Default")
      (node (ref "PB15") (pin "1") (pinfunction "G_1") (pintype "input"))
      (node (ref "PB15") (pin "3") (pinfunction "G_3") (pintype "input"))
      (node (ref "PB18") (pin "1") (pinfunction "G_1") (pintype "input"))
      (node (ref "PB18") (pin "3") (pinfunction "G_3") (pintype "input"))
      (node (ref "PB20") (pin "1") (pinfunction "G_1") (pintype "input"))
      (node (ref "PB20") (pin "3") (pinfunction "G_3") (pintype "input"))
      (node (ref "PB23") (pin "1") (pinfunction "G_1") (pintype "input"))
      (node (ref "PB23") (pin "3") (pinfunction "G_3") (pintype "input"))
      (node (ref "PB24") (pin "1") (pinfunction "G_1") (pintype "input"))
      (node (ref "PB24") (pin "3") (pinfunction "G_3") (pintype "input"))
      (node (ref "PB26") (pin "1") (pinfunction "G_1") (pintype "input"))
      (node (ref "PB26") (pin "3") (pinfunction "G_3") (pintype "input"))
      (node (ref "PB27") (pin "1") (pinfunction "G_1") (pintype "input"))
      (node (ref "PB27") (pin "3") (pinfunction "G_3") (pintype "input"))
      (node (ref "PB28") (pin "1") (pinfunction "G_1") (pintype "input"))
      (node (ref "PB28") (pin "3") (pinfunction "G_3") (pintype "input"))
      (node (ref "PB29") (pin "1") (pinfunction "G_1") (pintype "input"))
      (node (ref "PB29") (pin "3") (pinfunction "G_3") (pintype "input"))
      (node (ref "PB30") (pin "1") (pinfunction "G_1") (pintype "input"))
      (node (ref "PB30") (pin "3") (pinfunction "G_3") (pintype "input"))
      (node (ref "PB8") (pin "1") (pinfunction "G_1") (pintype "input"))
      (node (ref "PB8") (pin "3") (pinfunction "G_3") (pintype "input"))
      (node (ref "U2") (pin "367") (pinfunction "G__test__0_0_367") (pintype "passive"))
      (node (ref "U2") (pin "369") (pinfunction "G__test__0_1_369") (pintype "passive"))
      (node (ref "U2") (pin "370") (pinfunction "G__test__1_0_370") (pintype "passive"))
      (node (ref "U2") (pin "372") (pinfunction "G__test__1_1_372") (pintype "passive"))
      (node (ref "U2") (pin "373") (pinfunction "G__test__2_0_373") (pintype "passive"))
      (node (ref "U2") (pin "375") (pinfunction "G__test__2_1_375") (pintype "passive"))
      (node (ref "U2") (pin "376") (pinfunction "G__test__3_0_376") (pintype "passive"))
      (node (ref "U2") (pin "378") (pinfunction "G__test__3_1_378") (pintype "passive"))
      (node (ref "U2") (pin "379") (pinfunction "G__test__4_0_379") (pintype "passive"))
      (node (ref "U2") (pin "381") (pinfunction "G__test__4_1_381") (pintype "passive"))
      (node (ref "U2") (pin "382") (pinfunction "G__test__5_0_382") (pintype "passive"))
      (node (ref "U2") (pin "384") (pinfunction "G__test__5_1_384") (pintype "passive"))
      (node (ref "U2") (pin "385") (pinfunction "G__test__6_0_385") (pintype "passive"))
      (node (ref "U2") (pin "387") (pinfunction "G__test__6_1_387") (pintype "passive"))
      (node (ref "U2") (pin "388") (pinfunction "G__test__7_0_388") (pintype "passive"))
      (node (ref "U2") (pin "390") (pinfunction "G__test__7_1_390") (pintype "passive"))
      (node (ref "U2") (pin "391") (pinfunction "G__test__8_0_391") (pintype "passive"))
      (node (ref "U2") (pin "393") (pinfunction "G__test__8_1_393") (pintype "passive"))
      (node (ref "U2") (pin "394") (pinfunction "G__test__9_0_394") (pintype "passive"))
      (node (ref "U2") (pin "396") (pinfunction "G__test__9_1_396") (pintype "passive"))
      (node (ref "U2") (pin "397") (pinfunction "NC__test_0_397") (pintype "passive"))
      (node (ref "U2") (pin "398") (pinfunction "NC__test_1_398") (pintype "passive"))
      (node (ref "U2") (pin "399") (pinfunction "NC__test_2_399") (pintype "passive"))
      (node (ref "U2") (pin "413") (pinfunction "G__DEEMB_OUT_0_413") (pintype "passive"))
      (node (ref "U2") (pin "415") (pinfunction "G__DEEMB_OUT_1_415") (pintype "passive"))
    )
    (net (code "13") (name "/HVDD") (class "Default")
      (node (ref "J1") (pin "H14") (pintype "input"))
      (node (ref "J1") (pin "J13") (pintype "input"))
      (node (ref "J1") (pin "J15") (pintype "input"))
      (node (ref "J1") (pin "K14") (pintype "input"))
      (node (ref "J1") (pin "L13") (pintype "input"))
      (node (ref "J1") (pin "L15") (pintype "input"))
      (node (ref "J1") (pin "M14") (pintype "input"))
      (node (ref "J1") (pin "N13") (pintype "input"))
      (node (ref "J1") (pin "N15") (pintype "input"))
      (node (ref "U3") (pin "A2") (pinfunction "HVDD_A2") (pintype "input"))
      (node (ref "U3") (pin "A4") (pinfunction "HVDD_A4") (pintype "input"))
      (node (ref "U3") (pin "A7") (pinfunction "HVDD_A7") (pintype "input"))
      (node (ref "U3") (pin "B10") (pinfunction "HVDD_B10") (pintype "input"))
      (node (ref "U3") (pin "B2") (pinfunction "HVDD_B2") (pintype "input"))
      (node (ref "U3") (pin "B4") (pinfunction "HVDD_B4") (pintype "input"))
      (node (ref "U3") (pin "B7") (pinfunction "HVDD_B7") (pintype "input"))
      (node (ref "U3") (pin "C10") (pinfunction "HVDD_C10") (pintype "input"))
      (node (ref "U3") (pin "C2") (pinfunction "HVDD_C2") (pintype "input"))
      (node (ref "U3") (pin "C4") (pinfunction "HVDD_C4") (pintype "input"))
      (node (ref "U3") (pin "C7") (pinfunction "HVDD_C7") (pintype "input"))
      (node (ref "U3") (pin "D11") (pinfunction "HVDD_D11") (pintype "input"))
      (node (ref "U3") (pin "D3") (pinfunction "HVDD_D3") (pintype "input"))
      (node (ref "U3") (pin "D5") (pinfunction "HVDD_D5") (pintype "input"))
      (node (ref "U3") (pin "D8") (pinfunction "HVDD_D8") (pintype "input"))
      (node (ref "U3") (pin "E11") (pinfunction "HVDD_E11") (pintype "input"))
      (node (ref "U3") (pin "E3") (pinfunction "HVDD_E3") (pintype "input"))
      (node (ref "U3") (pin "E5") (pinfunction "HVDD_E5") (pintype "input"))
      (node (ref "U3") (pin "E8") (pinfunction "HVDD_E8") (pintype "input"))
      (node (ref "U3") (pin "F10") (pinfunction "HVDD_F10") (pintype "input"))
      (node (ref "U3") (pin "F2") (pinfunction "HVDD_F2") (pintype "input"))
      (node (ref "U3") (pin "F4") (pinfunction "HVDD_F4") (pintype "input"))
      (node (ref "U3") (pin "F7") (pinfunction "HVDD_F7") (pintype "input"))
      (node (ref "U3") (pin "G10") (pinfunction "HVDD_G10") (pintype "input"))
      (node (ref "U3") (pin "G2") (pinfunction "HVDD_G2") (pintype "input"))
      (node (ref "U3") (pin "G4") (pinfunction "HVDD_G4") (pintype "input"))
      (node (ref "U3") (pin "G7") (pinfunction "HVDD_G7") (pintype "input"))
      (node (ref "U3") (pin "H11") (pinfunction "HVDD_H11") (pintype "input"))
      (node (ref "U3") (pin "H3") (pinfunction "HVDD_H3") (pintype "input"))
      (node (ref "U3") (pin "H5") (pinfunction "HVDD_H5") (pintype "input"))
      (node (ref "U3") (pin "H8") (pinfunction "HVDD_H8") (pintype "input"))
      (node (ref "U3") (pin "I11") (pinfunction "HVDD_I11") (pintype "input"))
      (node (ref "U3") (pin "I3") (pinfunction "HVDD_I3") (pintype "input"))
      (node (ref "U3") (pin "I5") (pinfunction "HVDD_I5") (pintype "input"))
      (node (ref "U3") (pin "I8") (pinfunction "HVDD_I8") (pintype "input"))
      (node (ref "U3") (pin "J10") (pinfunction "HVDD_J10") (pintype "input"))
      (node (ref "U3") (pin "J2") (pinfunction "HVDD_J2") (pintype "input"))
      (node (ref "U3") (pin "J4") (pinfunction "HVDD_J4") (pintype "input"))
      (node (ref "U3") (pin "J7") (pinfunction "HVDD_J7") (pintype "input"))
      (node (ref "U3") (pin "K10") (pinfunction "HVDD_K10") (pintype "input"))
      (node (ref "U3") (pin "K2") (pinfunction "HVDD_K2") (pintype "input"))
      (node (ref "U3") (pin "K4") (pinfunction "HVDD_K4") (pintype "input"))
      (node (ref "U3") (pin "K7") (pinfunction "HVDD_K7") (pintype "input"))
      (node (ref "U3") (pin "L11") (pinfunction "HVDD_L11") (pintype "input"))
      (node (ref "U3") (pin "L3") (pinfunction "HVDD_L3") (pintype "input"))
      (node (ref "U3") (pin "L5") (pinfunction "HVDD_L5") (pintype "input"))
      (node (ref "U3") (pin "L8") (pinfunction "HVDD_L8") (pintype "input"))
      (node (ref "U3") (pin "M11") (pinfunction "HVDD_M11") (pintype "input"))
      (node (ref "U3") (pin "M3") (pinfunction "HVDD_M3") (pintype "input"))
      (node (ref "U3") (pin "M5") (pinfunction "HVDD_M5") (pintype "input"))
      (node (ref "U3") (pin "M8") (pinfunction "HVDD_M8") (pintype "input"))
      (node (ref "U3") (pin "N10") (pinfunction "HVDD_N10") (pintype "input"))
      (node (ref "U3") (pin "N2") (pinfunction "HVDD_N2") (pintype "input"))
      (node (ref "U3") (pin "N4") (pinfunction "HVDD_N4") (pintype "input"))
      (node (ref "U3") (pin "N7") (pinfunction "HVDD_N7") (pintype "input"))
      (node (ref "U3") (pin "O10") (pinfunction "HVDD_O10") (pintype "input"))
      (node (ref "U3") (pin "O2") (pinfunction "HVDD_O2") (pintype "input"))
      (node (ref "U3") (pin "O4") (pinfunction "HVDD_O4") (pintype "input"))
      (node (ref "U3") (pin "O7") (pinfunction "HVDD_O7") (pintype "input"))
      (node (ref "U3") (pin "P11") (pinfunction "HVDD_P11") (pintype "input"))
      (node (ref "U3") (pin "P3") (pinfunction "HVDD_P3") (pintype "input"))
      (node (ref "U3") (pin "P5") (pinfunction "HVDD_P5") (pintype "input"))
      (node (ref "U3") (pin "P8") (pinfunction "HVDD_P8") (pintype "input"))
      (node (ref "U3") (pin "Q11") (pinfunction "HVDD_Q11") (pintype "input"))
      (node (ref "U3") (pin "Q3") (pinfunction "HVDD_Q3") (pintype "input"))
      (node (ref "U3") (pin "Q5") (pinfunction "HVDD_Q5") (pintype "input"))
      (node (ref "U3") (pin "Q8") (pinfunction "HVDD_Q8") (pintype "input"))
      (node (ref "U3") (pin "R10") (pinfunction "HVDD_R10") (pintype "input"))
      (node (ref "U3") (pin "R2") (pinfunction "HVDD_R2") (pintype "input"))
      (node (ref "U3") (pin "R4") (pinfunction "HVDD_R4") (pintype "input"))
      (node (ref "U3") (pin "R7") (pinfunction "HVDD_R7") (pintype "input"))
      (node (ref "U3") (pin "S10") (pinfunction "HVDD_S10") (pintype "input"))
      (node (ref "U3") (pin "S2") (pinfunction "HVDD_S2") (pintype "input"))
      (node (ref "U3") (pin "S4") (pinfunction "HVDD_S4") (pintype "input"))
      (node (ref "U3") (pin "S7") (pinfunction "HVDD_S7") (pintype "input"))
      (node (ref "U4") (pin "C5") (pinfunction "HVDD_C5") (pintype "input"))
      (node (ref "U4") (pin "C6") (pinfunction "HVDD_C6") (pintype "input"))
      (node (ref "U4") (pin "F3") (pinfunction "HVDD_F3") (pintype "input"))
      (node (ref "U4") (pin "F4") (pinfunction "HVDD_F4") (pintype "input"))
      (node (ref "U4") (pin "G8") (pinfunction "HVDD_G8") (pintype "input"))
      (node (ref "U4") (pin "G9") (pinfunction "HVDD_G9") (pintype "input"))
      (node (ref "U4") (pin "I5") (pinfunction "HVDD_I5") (pintype "input"))
      (node (ref "U4") (pin "J5") (pinfunction "HVDD_J5") (pintype "input"))
      (node (ref "U4") (pin "L3") (pinfunction "HVDD_L3") (pintype "input"))
      (node (ref "U4") (pin "L4") (pinfunction "HVDD_L4") (pintype "input"))
      (node (ref "U4") (pin "P3") (pinfunction "HVDD_P3") (pintype "input"))
      (node (ref "U4") (pin "P4") (pinfunction "HVDD_P4") (pintype "input"))
      (node (ref "U4") (pin "P8") (pinfunction "HVDD_P8") (pintype "input"))
      (node (ref "U4") (pin "Q8") (pinfunction "HVDD_Q8") (pintype "input"))
      (node (ref "U4") (pin "T4") (pinfunction "HVDD_T4") (pintype "input"))
      (node (ref "U4") (pin "T8") (pinfunction "HVDD_T8") (pintype "input"))
      (node (ref "U5") (pin "B6") (pinfunction "HVDD_B6") (pintype "input"))
      (node (ref "U5") (pin "C6") (pinfunction "HVDD_C6") (pintype "input"))
      (node (ref "U5") (pin "F6") (pinfunction "HVDD_F6") (pintype "input"))
      (node (ref "U5") (pin "F7") (pinfunction "HVDD_F7") (pintype "input"))
      (node (ref "U5") (pin "G5") (pinfunction "HVDD_G5") (pintype "input"))
      (node (ref "U5") (pin "H5") (pinfunction "HVDD_H5") (pintype "input"))
      (node (ref "U5") (pin "J1") (pinfunction "HVDD_J1") (pintype "input"))
      (node (ref "U5") (pin "K6") (pinfunction "HVDD_K6") (pintype "input"))
      (node (ref "U5") (pin "K7") (pinfunction "HVDD_K7") (pintype "input"))
      (node (ref "U5") (pin "L3") (pinfunction "HVDD_L3") (pintype "input"))
      (node (ref "U5") (pin "L4") (pinfunction "HVDD_L4") (pintype "input"))
      (node (ref "U5") (pin "L7") (pinfunction "HVDD_L7") (pintype "input"))
      (node (ref "U5") (pin "P5") (pinfunction "HVDD_P5") (pintype "input"))
      (node (ref "U5") (pin "P6") (pinfunction "HVDD_P6") (pintype "input"))
      (node (ref "U5") (pin "P7") (pinfunction "HVDD_P7") (pintype "input"))
      (node (ref "U6") (pin "C3") (pinfunction "HVDD_C3") (pintype "passive"))
      (node (ref "U6") (pin "D4") (pinfunction "HVDD_D4") (pintype "passive"))
      (node (ref "U6") (pin "E3") (pinfunction "HVDD_E3") (pintype "passive"))
      (node (ref "U6") (pin "E4") (pinfunction "HVDD_E4") (pintype "passive"))
      (node (ref "U6") (pin "F3") (pinfunction "HVDD_F3") (pintype "passive"))
      (node (ref "U6") (pin "F4") (pinfunction "HVDD_F4") (pintype "passive"))
    )
    (net (code "14") (name "/S_Load1") (class "Default")
      (node (ref "PB33") (pin "2") (pinfunction "S_2") (pintype "input"))
      (node (ref "R1") (pin "2") (pintype "input"))
    )
    (net (code "15") (name "/S_Load2") (class "Default")
      (node (ref "PB34") (pin "2") (pinfunction "S_2") (pintype "input"))
      (node (ref "R2") (pin "2") (pintype "input"))
    )
    (net (code "16") (name "/S_Open1") (class "Default")
      (node (ref "PB10") (pin "2") (pinfunction "S_2") (pintype "input"))
    )
    (net (code "17") (name "/S_Open2") (class "Default")
      (node (ref "PB11") (pin "2") (pinfunction "S_2") (pintype "input"))
    )
    (net (code "18") (name "/S_Thru1") (class "Default")
      (node (ref "PB31") (pin "2") (pinfunction "S_2") (pintype "input"))
      (node (ref "PB32") (pin "2") (pinfunction "S_2") (pintype "input"))
    )
    (net (code "19") (name "/S_Thru2") (class "Default")
      (node (ref "PB6") (pin "2") (pinfunction "S_2") (pintype "input"))
      (node (ref "PB9") (pin "2") (pinfunction "S_2") (pintype "input"))
    )
    (net (code "20") (name "/S__1") (class "Default")
      (node (ref "PB25") (pin "4") (pinfunction "S2_4") (pintype "input"))
      (node (ref "U2") (pin "26") (pinfunction "S__1_26") (pintype "passive"))
    )
    (net (code "21") (name "/S__2") (class "Default")
      (node (ref "PB25") (pin "2") (pinfunction "S1_2") (pintype "input"))
      (node (ref "U2") (pin "27") (pinfunction "S__2_27") (pintype "passive"))
    )
    (net (code "22") (name "/S__3") (class "Default")
      (node (ref "PB21") (pin "4") (pinfunction "S2_4") (pintype "input"))
      (node (ref "U2") (pin "55") (pinfunction "S__3_55") (pintype "passive"))
    )
    (net (code "23") (name "/S__4") (class "Default")
      (node (ref "PB21") (pin "2") (pinfunction "S1_2") (pintype "input"))
      (node (ref "U2") (pin "56") (pinfunction "S__4_56") (pintype "passive"))
    )
    (net (code "24") (name "/S__5") (class "Default")
      (node (ref "PB19") (pin "4") (pinfunction "S2_4") (pintype "input"))
      (node (ref "U2") (pin "84") (pinfunction "S__5_84") (pintype "passive"))
    )
    (net (code "25") (name "/S__6") (class "Default")
      (node (ref "PB19") (pin "2") (pinfunction "S1_2") (pintype "input"))
      (node (ref "U2") (pin "85") (pinfunction "S__6_85") (pintype "passive"))
    )
    (net (code "26") (name "/S__7") (class "Default")
      (node (ref "PB17") (pin "4") (pinfunction "S2_4") (pintype "input"))
      (node (ref "U2") (pin "113") (pinfunction "S__7_113") (pintype "passive"))
    )
    (net (code "27") (name "/S__8") (class "Default")
      (node (ref "PB17") (pin "2") (pinfunction "S1_2") (pintype "input"))
      (node (ref "U2") (pin "114") (pinfunction "S__8_114") (pintype "passive"))
    )
    (net (code "28") (name "/S__9") (class "Default")
      (node (ref "PB16") (pin "4") (pinfunction "S2_4") (pintype "input"))
      (node (ref "U2") (pin "142") (pinfunction "S__9_142") (pintype "passive"))
    )
    (net (code "29") (name "/S__10") (class "Default")
      (node (ref "PB16") (pin "2") (pinfunction "S1_2") (pintype "input"))
      (node (ref "U2") (pin "143") (pinfunction "S__10_143") (pintype "passive"))
    )
    (net (code "30") (name "/S__11") (class "Default")
      (node (ref "PB12") (pin "4") (pinfunction "S2_4") (pintype "input"))
      (node (ref "U2") (pin "171") (pinfunction "S__11_171") (pintype "passive"))
    )
    (net (code "31") (name "/S__12") (class "Default")
      (node (ref "PB12") (pin "2") (pinfunction "S1_2") (pintype "input"))
      (node (ref "U2") (pin "172") (pinfunction "S__12_172") (pintype "passive"))
    )
    (net (code "32") (name "/S__13") (class "Default")
      (node (ref "PB7") (pin "4") (pinfunction "S2_4") (pintype "input"))
      (node (ref "U2") (pin "200") (pinfunction "S__13_200") (pintype "passive"))
    )
    (net (code "33") (name "/S__14") (class "Default")
      (node (ref "PB7") (pin "2") (pinfunction "S1_2") (pintype "input"))
      (node (ref "U2") (pin "201") (pinfunction "S__14_201") (pintype "passive"))
    )
    (net (code "34") (name "/S__15") (class "Default")
      (node (ref "PB5") (pin "4") (pinfunction "S2_4") (pintype "input"))
      (node (ref "U2") (pin "229") (pinfunction "S__15_229") (pintype "passive"))
    )
    (net (code "35") (name "/S__16") (class "Default")
      (node (ref "PB5") (pin "2") (pinfunction "S1_2") (pintype "input"))
      (node (ref "U2") (pin "230") (pinfunction "S__16_230") (pintype "passive"))
    )
    (net (code "36") (name "/S__17") (class "Default")
      (node (ref "PB4") (pin "4") (pinfunction "S2_4") (pintype "input"))
      (node (ref "U2") (pin "258") (pinfunction "S__17_258") (pintype "passive"))
    )
    (net (code "37") (name "/S__18") (class "Default")
      (node (ref "PB4") (pin "2") (pinfunction "S1_2") (pintype "input"))
      (node (ref "U2") (pin "259") (pinfunction "S__18_259") (pintype "passive"))
    )
    (net (code "38") (name "/S__19") (class "Default")
      (node (ref "PB3") (pin "4") (pinfunction "S2_4") (pintype "input"))
      (node (ref "U2") (pin "287") (pinfunction "S__19_287") (pintype "passive"))
    )
    (net (code "39") (name "/S__20") (class "Default")
      (node (ref "PB3") (pin "2") (pinfunction "S1_2") (pintype "input"))
      (node (ref "U2") (pin "288") (pinfunction "S__20_288") (pintype "passive"))
    )
    (net (code "40") (name "/S__21") (class "Default")
      (node (ref "PB2") (pin "4") (pinfunction "S2_4") (pintype "input"))
      (node (ref "U2") (pin "316") (pinfunction "S__21_316") (pintype "passive"))
    )
    (net (code "41") (name "/S__22") (class "Default")
      (node (ref "PB2") (pin "2") (pinfunction "S1_2") (pintype "input"))
      (node (ref "U2") (pin "317") (pinfunction "S__22_317") (pintype "passive"))
    )
    (net (code "42") (name "/S__23") (class "Default")
      (node (ref "PB1") (pin "4") (pinfunction "S2_4") (pintype "input"))
      (node (ref "U2") (pin "345") (pinfunction "S__23_345") (pintype "passive"))
    )
    (net (code "43") (name "/S__24") (class "Default")
      (node (ref "PB1") (pin "2") (pinfunction "S1_2") (pintype "input"))
      (node (ref "U2") (pin "346") (pinfunction "S__24_346") (pintype "passive"))
    )
    (net (code "44") (name "/S__DEEMB_IN") (class "Default")
      (node (ref "PB22") (pin "2") (pinfunction "S_2") (pintype "input"))
      (node (ref "U2") (pin "411") (pinfunction "S__DEEMB_IN_411") (pintype "passive"))
    )
    (net (code "45") (name "/S__DEEMB_OUT") (class "Default")
      (node (ref "PB23") (pin "2") (pinfunction "S_2") (pintype "input"))
      (node (ref "U2") (pin "414") (pinfunction "S__DEEMB_OUT_414") (pintype "passive"))
    )
    (net (code "46") (name "/S__test__0") (class "Default")
      (node (ref "PB30") (pin "2") (pinfunction "S_2") (pintype "input"))
      (node (ref "U2") (pin "368") (pinfunction "S__test__0_368") (pintype "passive"))
    )
    (net (code "47") (name "/S__test__1") (class "Default")
      (node (ref "PB29") (pin "2") (pinfunction "S_2") (pintype "input"))
      (node (ref "U2") (pin "371") (pinfunction "S__test__1_371") (pintype "passive"))
    )
    (net (code "48") (name "/S__test__2") (class "Default")
      (node (ref "PB28") (pin "2") (pinfunction "S_2") (pintype "input"))
      (node (ref "U2") (pin "374") (pinfunction "S__test__2_374") (pintype "passive"))
    )
    (net (code "49") (name "/S__test__3") (class "Default")
      (node (ref "PB27") (pin "2") (pinfunction "S_2") (pintype "input"))
      (node (ref "U2") (pin "377") (pinfunction "S__test__3_377") (pintype "passive"))
    )
    (net (code "50") (name "/S__test__4") (class "Default")
      (node (ref "PB26") (pin "2") (pinfunction "S_2") (pintype "input"))
      (node (ref "U2") (pin "380") (pinfunction "S__test__4_380") (pintype "passive"))
    )
    (net (code "51") (name "/S__test__5") (class "Default")
      (node (ref "PB24") (pin "2") (pinfunction "S_2") (pintype "input"))
      (node (ref "U2") (pin "383") (pinfunction "S__test__5_383") (pintype "passive"))
    )
    (net (code "52") (name "/S__test__6") (class "Default")
      (node (ref "PB20") (pin "2") (pinfunction "S_2") (pintype "input"))
      (node (ref "U2") (pin "386") (pinfunction "S__test__6_386") (pintype "passive"))
    )
    (net (code "53") (name "/S__test__7") (class "Default")
      (node (ref "PB18") (pin "2") (pinfunction "S_2") (pintype "input"))
      (node (ref "U2") (pin "389") (pinfunction "S__test__7_389") (pintype "passive"))
    )
    (net (code "54") (name "/S__test__8") (class "Default")
      (node (ref "PB15") (pin "2") (pinfunction "S_2") (pintype "input"))
      (node (ref "U2") (pin "392") (pinfunction "S__test__8_392") (pintype "passive"))
    )
    (net (code "55") (name "/S__test__9") (class "Default")
      (node (ref "PB8") (pin "2") (pinfunction "S_2") (pintype "input"))
      (node (ref "U2") (pin "395") (pinfunction "S__test__9_395") (pintype "passive"))
    )
    (net (code "56") (name "/TXVDD") (class "Default")
      (node (ref "J1") (pin "F12") (pintype "input"))
      (node (ref "J1") (pin "F13") (pintype "input"))
      (node (ref "U4") (pin "E3") (pinfunction "TXVDD_E3") (pintype "input"))
      (node (ref "U4") (pin "E4") (pinfunction "TXVDD_E4") (pintype "input"))
      (node (ref "U4") (pin "E9") (pinfunction "TXVDD_E9") (pintype "input"))
      (node (ref "U4") (pin "F9") (pinfunction "TXVDD_F9") (pintype "input"))
      (node (ref "U4") (pin "P9") (pinfunction "TXVDD_P9") (pintype "input"))
      (node (ref "U4") (pin "Q3") (pinfunction "TXVDD_Q3") (pintype "input"))
      (node (ref "U4") (pin "Q4") (pinfunction "TXVDD_Q4") (pintype "input"))
      (node (ref "U4") (pin "Q9") (pinfunction "TXVDD_Q9") (pintype "input"))
    )
    (net (code "57") (name "/VDD") (class "Default")
      (node (ref "J1") (pin "H7") (pintype "input"))
      (node (ref "J1") (pin "J6") (pintype "input"))
      (node (ref "J1") (pin "K7") (pintype "input"))
      (node (ref "J1") (pin "K8") (pintype "input"))
      (node (ref "J1") (pin "L6") (pintype "input"))
      (node (ref "J1") (pin "L8") (pintype "input"))
      (node (ref "J1") (pin "M7") (pintype "input"))
      (node (ref "J1") (pin "N6") (pintype "input"))
      (node (ref "J1") (pin "N8") (pintype "input"))
      (node (ref "J1") (pin "P7") (pintype "input"))
      (node (ref "U2") (pin "10") (pinfunction "VDD_0__1_2_10") (pintype "passive"))
      (node (ref "U2") (pin "12") (pinfunction "VDD_1__1_2_12") (pintype "passive"))
      (node (ref "U2") (pin "126") (pinfunction "VDD_0__9_10_126") (pintype "passive"))
      (node (ref "U2") (pin "128") (pinfunction "VDD_1__9_10_128") (pintype "passive"))
      (node (ref "U2") (pin "155") (pinfunction "VDD_0__11_12_155") (pintype "passive"))
      (node (ref "U2") (pin "157") (pinfunction "VDD_1__11_12_157") (pintype "passive"))
      (node (ref "U2") (pin "184") (pinfunction "VDD_0__13_14_184") (pintype "passive"))
      (node (ref "U2") (pin "186") (pinfunction "VDD_1__13_14_186") (pintype "passive"))
      (node (ref "U2") (pin "213") (pinfunction "VDD_0__15_16_213") (pintype "passive"))
      (node (ref "U2") (pin "215") (pinfunction "VDD_1__15_16_215") (pintype "passive"))
      (node (ref "U2") (pin "242") (pinfunction "VDD_0__17_18_242") (pintype "passive"))
      (node (ref "U2") (pin "244") (pinfunction "VDD_1__17_18_244") (pintype "passive"))
      (node (ref "U2") (pin "271") (pinfunction "VDD_0__19_20_271") (pintype "passive"))
      (node (ref "U2") (pin "273") (pinfunction "VDD_1__19_20_273") (pintype "passive"))
      (node (ref "U2") (pin "300") (pinfunction "VDD_0__21_22_300") (pintype "passive"))
      (node (ref "U2") (pin "302") (pinfunction "VDD_1__21_22_302") (pintype "passive"))
      (node (ref "U2") (pin "329") (pinfunction "VDD_0__23_24_329") (pintype "passive"))
      (node (ref "U2") (pin "331") (pinfunction "VDD_1__23_24_331") (pintype "passive"))
      (node (ref "U2") (pin "39") (pinfunction "VDD_0__3_4_39") (pintype "passive"))
      (node (ref "U2") (pin "406") (pinfunction "VDD_0__DEEMB_406") (pintype "passive"))
      (node (ref "U2") (pin "408") (pinfunction "VDD_1__DEEMB_408") (pintype "passive"))
      (node (ref "U2") (pin "41") (pinfunction "VDD_1__3_4_41") (pintype "passive"))
      (node (ref "U2") (pin "68") (pinfunction "VDD_0__5_6_68") (pintype "passive"))
      (node (ref "U2") (pin "70") (pinfunction "VDD_1__5_6_70") (pintype "passive"))
      (node (ref "U2") (pin "97") (pinfunction "VDD_0__7_8_97") (pintype "passive"))
      (node (ref "U2") (pin "99") (pinfunction "VDD_1__7_8_99") (pintype "passive"))
      (node (ref "U3") (pin "A11") (pinfunction "VDD_A11") (pintype "input"))
      (node (ref "U3") (pin "B11") (pinfunction "VDD_B11") (pintype "input"))
      (node (ref "U3") (pin "B3") (pinfunction "VDD_B3") (pintype "input"))
      (node (ref "U3") (pin "B5") (pinfunction "VDD_B5") (pintype "input"))
      (node (ref "U3") (pin "B8") (pinfunction "VDD_B8") (pintype "input"))
      (node (ref "U3") (pin "C11") (pinfunction "VDD_C11") (pintype "input"))
      (node (ref "U3") (pin "C3") (pinfunction "VDD_C3") (pintype "input"))
      (node (ref "U3") (pin "C5") (pinfunction "VDD_C5") (pintype "input"))
      (node (ref "U3") (pin "C8") (pinfunction "VDD_C8") (pintype "input"))
      (node (ref "U3") (pin "D1") (pinfunction "VDD_D1") (pintype "input"))
      (node (ref "U3") (pin "D6") (pinfunction "VDD_D6") (pintype "input"))
      (node (ref "U3") (pin "D9") (pinfunction "VDD_D9") (pintype "input"))
      (node (ref "U3") (pin "E1") (pinfunction "VDD_E1") (pintype "input"))
      (node (ref "U3") (pin "E6") (pinfunction "VDD_E6") (pintype "input"))
      (node (ref "U3") (pin "E9") (pinfunction "VDD_E9") (pintype "input"))
      (node (ref "U3") (pin "F11") (pinfunction "VDD_F11") (pintype "input"))
      (node (ref "U3") (pin "F3") (pinfunction "VDD_F3") (pintype "input"))
      (node (ref "U3") (pin "F5") (pinfunction "VDD_F5") (pintype "input"))
      (node (ref "U3") (pin "F8") (pinfunction "VDD_F8") (pintype "input"))
      (node (ref "U3") (pin "G11") (pinfunction "VDD_G11") (pintype "input"))
      (node (ref "U3") (pin "G3") (pinfunction "VDD_G3") (pintype "input"))
      (node (ref "U3") (pin "G5") (pinfunction "VDD_G5") (pintype "input"))
      (node (ref "U3") (pin "G8") (pinfunction "VDD_G8") (pintype "input"))
      (node (ref "U3") (pin "H1") (pinfunction "VDD_H1") (pintype "input"))
      (node (ref "U3") (pin "H6") (pinfunction "VDD_H6") (pintype "input"))
      (node (ref "U3") (pin "H9") (pinfunction "VDD_H9") (pintype "input"))
      (node (ref "U3") (pin "I1") (pinfunction "VDD_I1") (pintype "input"))
      (node (ref "U3") (pin "I6") (pinfunction "VDD_I6") (pintype "input"))
      (node (ref "U3") (pin "I9") (pinfunction "VDD_I9") (pintype "input"))
      (node (ref "U3") (pin "J11") (pinfunction "VDD_J11") (pintype "input"))
      (node (ref "U3") (pin "J3") (pinfunction "VDD_J3") (pintype "input"))
      (node (ref "U3") (pin "J5") (pinfunction "VDD_J5") (pintype "input"))
      (node (ref "U3") (pin "J8") (pinfunction "VDD_J8") (pintype "input"))
      (node (ref "U3") (pin "K11") (pinfunction "VDD_K11") (pintype "input"))
      (node (ref "U3") (pin "K3") (pinfunction "VDD_K3") (pintype "input"))
      (node (ref "U3") (pin "K5") (pinfunction "VDD_K5") (pintype "input"))
      (node (ref "U3") (pin "K8") (pinfunction "VDD_K8") (pintype "input"))
      (node (ref "U3") (pin "L1") (pinfunction "VDD_L1") (pintype "input"))
      (node (ref "U3") (pin "L6") (pinfunction "VDD_L6") (pintype "input"))
      (node (ref "U3") (pin "L9") (pinfunction "VDD_L9") (pintype "input"))
      (node (ref "U3") (pin "M1") (pinfunction "VDD_M1") (pintype "input"))
      (node (ref "U3") (pin "M6") (pinfunction "VDD_M6") (pintype "input"))
      (node (ref "U3") (pin "M9") (pinfunction "VDD_M9") (pintype "input"))
      (node (ref "U3") (pin "N11") (pinfunction "VDD_N11") (pintype "input"))
      (node (ref "U3") (pin "N3") (pinfunction "VDD_N3") (pintype "input"))
      (node (ref "U3") (pin "N5") (pinfunction "VDD_N5") (pintype "input"))
      (node (ref "U3") (pin "N8") (pinfunction "VDD_N8") (pintype "input"))
      (node (ref "U3") (pin "O11") (pinfunction "VDD_O11") (pintype "input"))
      (node (ref "U3") (pin "O3") (pinfunction "VDD_O3") (pintype "input"))
      (node (ref "U3") (pin "O5") (pinfunction "VDD_O5") (pintype "input"))
      (node (ref "U3") (pin "O8") (pinfunction "VDD_O8") (pintype "input"))
      (node (ref "U3") (pin "P1") (pinfunction "VDD_P1") (pintype "input"))
      (node (ref "U3") (pin "P6") (pinfunction "VDD_P6") (pintype "input"))
      (node (ref "U3") (pin "P9") (pinfunction "VDD_P9") (pintype "input"))
      (node (ref "U3") (pin "Q1") (pinfunction "VDD_Q1") (pintype "input"))
      (node (ref "U3") (pin "Q6") (pinfunction "VDD_Q6") (pintype "input"))
      (node (ref "U3") (pin "Q9") (pinfunction "VDD_Q9") (pintype "input"))
      (node (ref "U3") (pin "R11") (pinfunction "VDD_R11") (pintype "input"))
      (node (ref "U3") (pin "R3") (pinfunction "VDD_R3") (pintype "input"))
      (node (ref "U3") (pin "R5") (pinfunction "VDD_R5") (pintype "input"))
      (node (ref "U3") (pin "R8") (pinfunction "VDD_R8") (pintype "input"))
      (node (ref "U3") (pin "S11") (pinfunction "VDD_S11") (pintype "input"))
      (node (ref "U3") (pin "S3") (pinfunction "VDD_S3") (pintype "input"))
      (node (ref "U3") (pin "S5") (pinfunction "VDD_S5") (pintype "input"))
      (node (ref "U3") (pin "S8") (pinfunction "VDD_S8") (pintype "input"))
      (node (ref "U4") (pin "C7") (pinfunction "VDD_C7") (pintype "input"))
      (node (ref "U4") (pin "C8") (pinfunction "VDD_C8") (pintype "input"))
      (node (ref "U4") (pin "H3") (pinfunction "VDD_H3") (pintype "input"))
      (node (ref "U4") (pin "I3") (pinfunction "VDD_I3") (pintype "input"))
      (node (ref "U4") (pin "I7") (pinfunction "VDD_I7") (pintype "input"))
      (node (ref "U4") (pin "M6") (pinfunction "VDD_M6") (pintype "input"))
      (node (ref "U4") (pin "N6") (pinfunction "VDD_N6") (pintype "input"))
      (node (ref "U4") (pin "R5") (pinfunction "VDD_R5") (pintype "input"))
      (node (ref "U4") (pin "S5") (pinfunction "VDD_S5") (pintype "input"))
      (node (ref "U5") (pin "C7") (pinfunction "VDD_C7") (pintype "input"))
      (node (ref "U5") (pin "D7") (pinfunction "VDD_D7") (pintype "input"))
      (node (ref "U5") (pin "I5") (pinfunction "VDD_I5") (pintype "input"))
      (node (ref "U5") (pin "I6") (pinfunction "VDD_I6") (pintype "input"))
      (node (ref "U5") (pin "K8") (pinfunction "VDD_K8") (pintype "input"))
      (node (ref "U5") (pin "L8") (pinfunction "VDD_L8") (pintype "input"))
      (node (ref "U5") (pin "M4") (pinfunction "VDD_M4") (pintype "input"))
      (node (ref "U5") (pin "M5") (pinfunction "VDD_M5") (pintype "input"))
      (node (ref "U5") (pin "N5") (pinfunction "VDD_N5") (pintype "input"))
      (node (ref "U5") (pin "Q7") (pinfunction "VDD_Q7") (pintype "input"))
      (node (ref "U5") (pin "Q8") (pinfunction "VDD_Q8") (pintype "input"))
      (node (ref "U5") (pin "S4") (pinfunction "VDD_S4") (pintype "input"))
      (node (ref "U5") (pin "S5") (pinfunction "VDD_S5") (pintype "input"))
      (node (ref "U5") (pin "S6") (pinfunction "VDD_S6") (pintype "input"))
      (node (ref "U5") (pin "T10") (pinfunction "VDD_T10") (pintype "input"))
      (node (ref "U6") (pin "D7") (pinfunction "VDD_D7") (pintype "passive"))
      (node (ref "U6") (pin "D8") (pinfunction "VDD_D8") (pintype "passive"))
      (node (ref "U6") (pin "E7") (pinfunction "VDD_E7") (pintype "passive"))
      (node (ref "U6") (pin "F6") (pinfunction "VDD_F6") (pintype "passive"))
    )
    (net (code "58") (name "/VPD") (class "Default")
      (node (ref "J1") (pin "F10") (pintype "input"))
      (node (ref "U4") (pin "C3") (pinfunction "VPD_C3") (pintype "input"))
      (node (ref "U4") (pin "C4") (pinfunction "VPD_C4") (pintype "input"))
      (node (ref "U4") (pin "D7") (pinfunction "VPD_D7") (pintype "input"))
      (node (ref "U4") (pin "D8") (pinfunction "VPD_D8") (pintype "input"))
      (node (ref "U4") (pin "H4") (pinfunction "VPD_H4") (pintype "input"))
      (node (ref "U4") (pin "I4") (pinfunction "VPD_I4") (pintype "input"))
      (node (ref "U4") (pin "K5") (pinfunction "VPD_K5") (pintype "input"))
      (node (ref "U4") (pin "K6") (pinfunction "VPD_K6") (pintype "input"))
      (node (ref "U4") (pin "O8") (pinfunction "VPD_O8") (pintype "input"))
      (node (ref "U4") (pin "O9") (pinfunction "VPD_O9") (pintype "input"))
      (node (ref "U4") (pin "T3") (pinfunction "VPD_T3") (pintype "input"))
      (node (ref "U4") (pin "T9") (pinfunction "VPD_T9") (pintype "input"))
      (node (ref "U5") (pin "E8") (pinfunction "VPD_E8") (pintype "input"))
      (node (ref "U5") (pin "L5") (pinfunction "VPD_L5") (pintype "input"))
      (node (ref "U5") (pin "L6") (pinfunction "VPD_L6") (pintype "input"))
    )
    (net (code "59") (name "/VREF0") (class "Default")
      (node (ref "J1") (pin "F9") (pintype "input"))
      (node (ref "U4") (pin "A1") (pinfunction "VREF0_A1") (pintype "input"))
      (node (ref "U4") (pin "F5") (pinfunction "VREF0_F5") (pintype "input"))
      (node (ref "U4") (pin "G5") (pinfunction "VREF0_G5") (pintype "input"))
      (node (ref "U4") (pin "N5") (pinfunction "VREF0_N5") (pintype "input"))
      (node (ref "U4") (pin "O5") (pinfunction "VREF0_O5") (pintype "input"))
      (node (ref "U4") (pin "T5") (pinfunction "VREF0_T5") (pintype "input"))
      (node (ref "U5") (pin "G6") (pinfunction "VREF0_G6") (pintype "input"))
      (node (ref "U5") (pin "H6") (pinfunction "VREF0_H6") (pintype "input"))
      (node (ref "U5") (pin "N6") (pinfunction "VREF0_N6") (pintype "input"))
      (node (ref "U5") (pin "O6") (pinfunction "VREF0_O6") (pintype "input"))
      (node (ref "U5") (pin "T11") (pinfunction "VREF0_T11") (pintype "input"))
    )
    (net (code "60") (name "/VREF1") (class "Default")
      (node (ref "J1") (pin "F8") (pintype "input"))
      (node (ref "U4") (pin "F6") (pinfunction "VREF1_F6") (pintype "input"))
      (node (ref "U4") (pin "G6") (pinfunction "VREF1_G6") (pintype "input"))
      (node (ref "U4") (pin "O6") (pinfunction "VREF1_O6") (pintype "input"))
      (node (ref "U4") (pin "P6") (pinfunction "VREF1_P6") (pintype "input"))
      (node (ref "U4") (pin "S1") (pinfunction "VREF1_S1") (pintype "input"))
      (node (ref "U4") (pin "T6") (pinfunction "VREF1_T6") (pintype "input"))
      (node (ref "U5") (pin "E6") (pinfunction "VREF1_E6") (pintype "input"))
      (node (ref "U5") (pin "E7") (pinfunction "VREF1_E7") (pintype "input"))
      (node (ref "U5") (pin "N7") (pinfunction "VREF1_N7") (pintype "input"))
      (node (ref "U5") (pin "O7") (pinfunction "VREF1_O7") (pintype "input"))
    )
    (net (code "61") (name "/VREF2") (class "Default")
      (node (ref "J1") (pin "F7") (pintype "input"))
      (node (ref "U4") (pin "B1") (pinfunction "VREF2_B1") (pintype "input"))
      (node (ref "U4") (pin "F7") (pinfunction "VREF2_F7") (pintype "input"))
      (node (ref "U4") (pin "G7") (pinfunction "VREF2_G7") (pintype "input"))
      (node (ref "U4") (pin "N7") (pinfunction "VREF2_N7") (pintype "input"))
      (node (ref "U4") (pin "O7") (pinfunction "VREF2_O7") (pintype "input"))
      (node (ref "U4") (pin "T7") (pinfunction "VREF2_T7") (pintype "input"))
      (node (ref "U5") (pin "E5") (pinfunction "VREF2_E5") (pintype "input"))
      (node (ref "U5") (pin "F5") (pinfunction "VREF2_F5") (pintype "input"))
      (node (ref "U5") (pin "M6") (pinfunction "VREF2_M6") (pintype "input"))
      (node (ref "U5") (pin "M7") (pinfunction "VREF2_M7") (pintype "input"))
    )
    (net (code "62") (name "/VSS") (class "Default")
      (node (ref "J1") (pin "D13") (pintype "input"))
      (node (ref "J1") (pin "D16") (pintype "input"))
      (node (ref "J1") (pin "E13") (pintype "input"))
      (node (ref "J1") (pin "F14") (pintype "input"))
      (node (ref "J1") (pin "F15") (pintype "input"))
      (node (ref "J1") (pin "F6") (pintype "input"))
      (node (ref "J1") (pin "G14") (pintype "input"))
      (node (ref "J1") (pin "G15") (pintype "input"))
      (node (ref "J1") (pin "G16") (pintype "input"))
      (node (ref "J1") (pin "G7") (pintype "input"))
      (node (ref "J1") (pin "G9") (pintype "input"))
      (node (ref "J1") (pin "H10") (pintype "input"))
      (node (ref "J1") (pin "H12") (pintype "input"))
      (node (ref "J1") (pin "H15") (pintype "input"))
      (node (ref "J1") (pin "H6") (pintype "input"))
      (node (ref "J1") (pin "H8") (pintype "input"))
      (node (ref "J1") (pin "J11") (pintype "input"))
      (node (ref "J1") (pin "J14") (pintype "input"))
      (node (ref "J1") (pin "J7") (pintype "input"))
      (node (ref "J1") (pin "J9") (pintype "input"))
      (node (ref "J1") (pin "K11") (pintype "input"))
      (node (ref "J1") (pin "K13") (pintype "input"))
      (node (ref "J1") (pin "K15") (pintype "input"))
      (node (ref "J1") (pin "K16") (pintype "input"))
      (node (ref "J1") (pin "K6") (pintype "input"))
      (node (ref "J1") (pin "K9") (pintype "input"))
      (node (ref "J1") (pin "L10") (pintype "input"))
      (node (ref "J1") (pin "L12") (pintype "input"))
      (node (ref "J1") (pin "L14") (pintype "input"))
      (node (ref "J1") (pin "L7") (pintype "input"))
      (node (ref "J1") (pin "L9") (pintype "input"))
      (node (ref "J1") (pin "M11") (pintype "input"))
      (node (ref "J1") (pin "M13") (pintype "input"))
      (node (ref "J1") (pin "M15") (pintype "input"))
      (node (ref "J1") (pin "M6") (pintype "input"))
      (node (ref "J1") (pin "M8") (pintype "input"))
      (node (ref "J1") (pin "M9") (pintype "input"))
      (node (ref "J1") (pin "N10") (pintype "input"))
      (node (ref "J1") (pin "N12") (pintype "input"))
      (node (ref "J1") (pin "N14") (pintype "input"))
      (node (ref "J1") (pin "N5") (pintype "input"))
      (node (ref "J1") (pin "N7") (pintype "input"))
      (node (ref "J1") (pin "N9") (pintype "input"))
      (node (ref "J1") (pin "P10") (pintype "input"))
      (node (ref "J1") (pin "P11") (pintype "input"))
      (node (ref "J1") (pin "P12") (pintype "input"))
      (node (ref "J1") (pin "P13") (pintype "input"))
      (node (ref "J1") (pin "P14") (pintype "input"))
      (node (ref "J1") (pin "P15") (pintype "input"))
      (node (ref "J1") (pin "P5") (pintype "input"))
      (node (ref "J1") (pin "P6") (pintype "input"))
      (node (ref "J1") (pin "P8") (pintype "input"))
      (node (ref "J1") (pin "P9") (pintype "input"))
      (node (ref "J1") (pin "R10") (pintype "input"))
      (node (ref "J1") (pin "R11") (pintype "input"))
      (node (ref "J1") (pin "R12") (pintype "input"))
      (node (ref "J1") (pin "R13") (pintype "input"))
      (node (ref "J1") (pin "R14") (pintype "input"))
      (node (ref "J1") (pin "R5") (pintype "input"))
      (node (ref "J1") (pin "R6") (pintype "input"))
      (node (ref "J1") (pin "R7") (pintype "input"))
      (node (ref "J1") (pin "R8") (pintype "input"))
      (node (ref "J1") (pin "R9") (pintype "input"))
      (node (ref "PB10") (pin "1") (pinfunction "G_1") (pintype "input"))
      (node (ref "PB10") (pin "3") (pinfunction "G_3") (pintype "input"))
      (node (ref "PB11") (pin "1") (pinfunction "G_1") (pintype "input"))
      (node (ref "PB11") (pin "3") (pinfunction "G_3") (pintype "input"))
      (node (ref "PB13") (pin "1") (pinfunction "G_1") (pintype "input"))
      (node (ref "PB13") (pin "2") (pinfunction "S_2") (pintype "input"))
      (node (ref "PB13") (pin "3") (pinfunction "G_3") (pintype "input"))
      (node (ref "PB14") (pin "1") (pinfunction "G_1") (pintype "input"))
      (node (ref "PB14") (pin "2") (pinfunction "S_2") (pintype "input"))
      (node (ref "PB14") (pin "3") (pinfunction "G_3") (pintype "input"))
      (node (ref "PB31") (pin "1") (pinfunction "G_1") (pintype "input"))
      (node (ref "PB31") (pin "3") (pinfunction "G_3") (pintype "input"))
      (node (ref "PB32") (pin "1") (pinfunction "G_1") (pintype "input"))
      (node (ref "PB32") (pin "3") (pinfunction "G_3") (pintype "input"))
      (node (ref "PB33") (pin "1") (pinfunction "G_1") (pintype "input"))
      (node (ref "PB33") (pin "3") (pinfunction "G_3") (pintype "input"))
      (node (ref "PB34") (pin "1") (pinfunction "G_1") (pintype "input"))
      (node (ref "PB34") (pin "3") (pinfunction "G_3") (pintype "input"))
      (node (ref "PB6") (pin "1") (pinfunction "G_1") (pintype "input"))
      (node (ref "PB6") (pin "3") (pinfunction "G_3") (pintype "input"))
      (node (ref "PB9") (pin "1") (pinfunction "G_1") (pintype "input"))
      (node (ref "PB9") (pin "3") (pinfunction "G_3") (pintype "input"))
      (node (ref "R1") (pin "1") (pintype "input"))
      (node (ref "R2") (pin "1") (pintype "input"))
      (node (ref "U1") (pin "A10") (pinfunction "NC33_A10") (pintype "input"))
      (node (ref "U1") (pin "A11") (pinfunction "NC34_A11") (pintype "input"))
      (node (ref "U1") (pin "A2") (pinfunction "Signal_HeaterLabelRight_GND__all_heaters_A2") (pintype "input"))
      (node (ref "U1") (pin "A7") (pinfunction "NC28_A7") (pintype "input"))
      (node (ref "U1") (pin "A8") (pinfunction "NC30_A8") (pintype "input"))
      (node (ref "U1") (pin "A9") (pinfunction "NC32_A9") (pintype "input"))
      (node (ref "U1") (pin "B8") (pinfunction "NC29_B8") (pintype "input"))
      (node (ref "U1") (pin "B9") (pinfunction "NC31_B9") (pintype "input"))
      (node (ref "U1") (pin "C5") (pinfunction "NC26_C5") (pintype "input"))
      (node (ref "U1") (pin "C6") (pinfunction "NC27_C6") (pintype "input"))
      (node (ref "U1") (pin "G9") (pinfunction "Signal/Idler_HeaterLabelLeft_ring_v_E12__shared_ground_G9") (pintype "input"))
      (node (ref "U1") (pin "H10") (pinfunction "NC25_H10") (pintype "input"))
      (node (ref "U1") (pin "H5") (pinfunction "all_heaters_GND_v_E26_H5") (pintype "input"))
      (node (ref "U1") (pin "I10") (pinfunction "NC24_I10") (pintype "input"))
      (node (ref "U1") (pin "I9") (pinfunction "NC21_I9") (pintype "input"))
      (node (ref "U1") (pin "J10") (pinfunction "NC23_J10") (pintype "input"))
      (node (ref "U1") (pin "J6") (pinfunction "NC18_J6") (pintype "input"))
      (node (ref "U1") (pin "J9") (pinfunction "NC20_J9") (pintype "input"))
      (node (ref "U1") (pin "K10") (pinfunction "NC22_K10") (pintype "input"))
      (node (ref "U1") (pin "K6") (pinfunction "NC17_K6") (pintype "input"))
      (node (ref "U1") (pin "K9") (pinfunction "NC19_K9") (pintype "input"))
      (node (ref "U1") (pin "P5") (pinfunction "all_heaters_GND_v_E20_P5") (pintype "input"))
      (node (ref "U1") (pin "P9") (pinfunction "Signal/Idler_HeaterLabelLeft_rings_v_E5__shared_ground_P9") (pintype "input"))
      (node (ref "U1") (pin "R10") (pinfunction "NC16_R10") (pintype "input"))
      (node (ref "U1") (pin "R5") (pinfunction "NC3_R5") (pintype "input"))
      (node (ref "U1") (pin "R6") (pinfunction "NC7_R6") (pintype "input"))
      (node (ref "U1") (pin "R9") (pinfunction "NC12_R9") (pintype "input"))
      (node (ref "U1") (pin "S10") (pinfunction "NC15_S10") (pintype "input"))
      (node (ref "U1") (pin "S2") (pinfunction "all_heaters_GND_v_E30_S2") (pintype "input"))
      (node (ref "U1") (pin "S5") (pinfunction "NC2_S5") (pintype "input"))
      (node (ref "U1") (pin "S6") (pinfunction "NC6_S6") (pintype "input"))
      (node (ref "U1") (pin "S9") (pinfunction "NC11_S9") (pintype "input"))
      (node (ref "U1") (pin "T10") (pinfunction "NC14_T10") (pintype "input"))
      (node (ref "U1") (pin "T5") (pinfunction "NC1_T5") (pintype "input"))
      (node (ref "U1") (pin "T6") (pinfunction "NC5_T6") (pintype "input"))
      (node (ref "U1") (pin "T9") (pinfunction "NC10_T9") (pintype "input"))
      (node (ref "U1") (pin "U10") (pinfunction "NC13_U10") (pintype "input"))
      (node (ref "U1") (pin "U5") (pinfunction "NC0_U5") (pintype "input"))
      (node (ref "U1") (pin "U6") (pinfunction "NC4_U6") (pintype "input"))
      (node (ref "U1") (pin "U8") (pinfunction "NC8_U8") (pintype "input"))
      (node (ref "U1") (pin "U9") (pinfunction "NC9_U9") (pintype "input"))
      (node (ref "U2") (pin "100") (pinfunction "VSS_2__7_8_100") (pintype "passive"))
      (node (ref "U2") (pin "11") (pinfunction "VSS_1__1_2_11") (pintype "passive"))
      (node (ref "U2") (pin "125") (pinfunction "VSS_0__9_10_125") (pintype "passive"))
      (node (ref "U2") (pin "127") (pinfunction "VSS_1__9_10_127") (pintype "passive"))
      (node (ref "U2") (pin "129") (pinfunction "VSS_2__9_10_129") (pintype "passive"))
      (node (ref "U2") (pin "13") (pinfunction "VSS_2__1_2_13") (pintype "passive"))
      (node (ref "U2") (pin "154") (pinfunction "VSS_0__11_12_154") (pintype "passive"))
      (node (ref "U2") (pin "156") (pinfunction "VSS_1__11_12_156") (pintype "passive"))
      (node (ref "U2") (pin "158") (pinfunction "VSS_2__11_12_158") (pintype "passive"))
      (node (ref "U2") (pin "183") (pinfunction "VSS_0__13_14_183") (pintype "passive"))
      (node (ref "U2") (pin "185") (pinfunction "VSS_1__13_14_185") (pintype "passive"))
      (node (ref "U2") (pin "187") (pinfunction "VSS_2__13_14_187") (pintype "passive"))
      (node (ref "U2") (pin "212") (pinfunction "VSS_0__15_16_212") (pintype "passive"))
      (node (ref "U2") (pin "214") (pinfunction "VSS_1__15_16_214") (pintype "passive"))
      (node (ref "U2") (pin "216") (pinfunction "VSS_2__15_16_216") (pintype "passive"))
      (node (ref "U2") (pin "241") (pinfunction "VSS_0__17_18_241") (pintype "passive"))
      (node (ref "U2") (pin "243") (pinfunction "VSS_1__17_18_243") (pintype "passive"))
      (node (ref "U2") (pin "245") (pinfunction "VSS_2__17_18_245") (pintype "passive"))
      (node (ref "U2") (pin "270") (pinfunction "VSS_0__19_20_270") (pintype "passive"))
      (node (ref "U2") (pin "272") (pinfunction "VSS_1__19_20_272") (pintype "passive"))
      (node (ref "U2") (pin "274") (pinfunction "VSS_2__19_20_274") (pintype "passive"))
      (node (ref "U2") (pin "299") (pinfunction "VSS_0__21_22_299") (pintype "passive"))
      (node (ref "U2") (pin "301") (pinfunction "VSS_1__21_22_301") (pintype "passive"))
      (node (ref "U2") (pin "303") (pinfunction "VSS_2__21_22_303") (pintype "passive"))
      (node (ref "U2") (pin "328") (pinfunction "VSS_0__23_24_328") (pintype "passive"))
      (node (ref "U2") (pin "330") (pinfunction "VSS_1__23_24_330") (pintype "passive"))
      (node (ref "U2") (pin "332") (pinfunction "VSS_2__23_24_332") (pintype "passive"))
      (node (ref "U2") (pin "38") (pinfunction "VSS_0__3_4_38") (pintype "passive"))
      (node (ref "U2") (pin "40") (pinfunction "VSS_1__3_4_40") (pintype "passive"))
      (node (ref "U2") (pin "405") (pinfunction "VSS_0__DEEMB_405") (pintype "passive"))
      (node (ref "U2") (pin "407") (pinfunction "VSS_1__DEEMB_407") (pintype "passive"))
      (node (ref "U2") (pin "409") (pinfunction "VSS_2__DEEMB_409") (pintype "passive"))
      (node (ref "U2") (pin "42") (pinfunction "VSS_2__3_4_42") (pintype "passive"))
      (node (ref "U2") (pin "67") (pinfunction "VSS_0__5_6_67") (pintype "passive"))
      (node (ref "U2") (pin "69") (pinfunction "VSS_1__5_6_69") (pintype "passive"))
      (node (ref "U2") (pin "71") (pinfunction "VSS_2__5_6_71") (pintype "passive"))
      (node (ref "U2") (pin "9") (pinfunction "VSS_0__1_2_9") (pintype "passive"))
      (node (ref "U2") (pin "96") (pinfunction "VSS_0__7_8_96") (pintype "passive"))
      (node (ref "U2") (pin "98") (pinfunction "VSS_1__7_8_98") (pintype "passive"))
      (node (ref "U3") (pin "A1") (pinfunction "VSS_A1") (pintype "input"))
      (node (ref "U3") (pin "A6") (pinfunction "VSS_A6") (pintype "input"))
      (node (ref "U3") (pin "B1") (pinfunction "VSS_B1") (pintype "input"))
      (node (ref "U3") (pin "B6") (pinfunction "VSS_B6") (pintype "input"))
      (node (ref "U3") (pin "B9") (pinfunction "VSS_B9") (pintype "input"))
      (node (ref "U3") (pin "C1") (pinfunction "VSS_C1") (pintype "input"))
      (node (ref "U3") (pin "C6") (pinfunction "VSS_C6") (pintype "input"))
      (node (ref "U3") (pin "C9") (pinfunction "VSS_C9") (pintype "input"))
      (node (ref "U3") (pin "D10") (pinfunction "VSS_D10") (pintype "input"))
      (node (ref "U3") (pin "D2") (pinfunction "VSS_D2") (pintype "input"))
      (node (ref "U3") (pin "D4") (pinfunction "VSS_D4") (pintype "input"))
      (node (ref "U3") (pin "D7") (pinfunction "VSS_D7") (pintype "input"))
      (node (ref "U3") (pin "E10") (pinfunction "VSS_E10") (pintype "input"))
      (node (ref "U3") (pin "E2") (pinfunction "VSS_E2") (pintype "input"))
      (node (ref "U3") (pin "E4") (pinfunction "VSS_E4") (pintype "input"))
      (node (ref "U3") (pin "E7") (pinfunction "VSS_E7") (pintype "input"))
      (node (ref "U3") (pin "F1") (pinfunction "VSS_F1") (pintype "input"))
      (node (ref "U3") (pin "F6") (pinfunction "VSS_F6") (pintype "input"))
      (node (ref "U3") (pin "F9") (pinfunction "VSS_F9") (pintype "input"))
      (node (ref "U3") (pin "G1") (pinfunction "VSS_G1") (pintype "input"))
      (node (ref "U3") (pin "G6") (pinfunction "VSS_G6") (pintype "input"))
      (node (ref "U3") (pin "G9") (pinfunction "VSS_G9") (pintype "input"))
      (node (ref "U3") (pin "H10") (pinfunction "VSS_H10") (pintype "input"))
      (node (ref "U3") (pin "H2") (pinfunction "VSS_H2") (pintype "input"))
      (node (ref "U3") (pin "H4") (pinfunction "VSS_H4") (pintype "input"))
      (node (ref "U3") (pin "H7") (pinfunction "VSS_H7") (pintype "input"))
      (node (ref "U3") (pin "I10") (pinfunction "VSS_I10") (pintype "input"))
      (node (ref "U3") (pin "I2") (pinfunction "VSS_I2") (pintype "input"))
      (node (ref "U3") (pin "I4") (pinfunction "VSS_I4") (pintype "input"))
      (node (ref "U3") (pin "I7") (pinfunction "VSS_I7") (pintype "input"))
      (node (ref "U3") (pin "J1") (pinfunction "VSS_J1") (pintype "input"))
      (node (ref "U3") (pin "J6") (pinfunction "VSS_J6") (pintype "input"))
      (node (ref "U3") (pin "J9") (pinfunction "VSS_J9") (pintype "input"))
      (node (ref "U3") (pin "K1") (pinfunction "VSS_K1") (pintype "input"))
      (node (ref "U3") (pin "K6") (pinfunction "VSS_K6") (pintype "input"))
      (node (ref "U3") (pin "K9") (pinfunction "VSS_K9") (pintype "input"))
      (node (ref "U3") (pin "L10") (pinfunction "VSS_L10") (pintype "input"))
      (node (ref "U3") (pin "L2") (pinfunction "VSS_L2") (pintype "input"))
      (node (ref "U3") (pin "L4") (pinfunction "VSS_L4") (pintype "input"))
      (node (ref "U3") (pin "L7") (pinfunction "VSS_L7") (pintype "input"))
      (node (ref "U3") (pin "M10") (pinfunction "VSS_M10") (pintype "input"))
      (node (ref "U3") (pin "M2") (pinfunction "VSS_M2") (pintype "input"))
      (node (ref "U3") (pin "M4") (pinfunction "VSS_M4") (pintype "input"))
      (node (ref "U3") (pin "M7") (pinfunction "VSS_M7") (pintype "input"))
      (node (ref "U3") (pin "N1") (pinfunction "VSS_N1") (pintype "input"))
      (node (ref "U3") (pin "N6") (pinfunction "VSS_N6") (pintype "input"))
      (node (ref "U3") (pin "N9") (pinfunction "VSS_N9") (pintype "input"))
      (node (ref "U3") (pin "O1") (pinfunction "VSS_O1") (pintype "input"))
      (node (ref "U3") (pin "O6") (pinfunction "VSS_O6") (pintype "input"))
      (node (ref "U3") (pin "O9") (pinfunction "VSS_O9") (pintype "input"))
      (node (ref "U3") (pin "P10") (pinfunction "VSS_P10") (pintype "input"))
      (node (ref "U3") (pin "P2") (pinfunction "VSS_P2") (pintype "input"))
      (node (ref "U3") (pin "P4") (pinfunction "VSS_P4") (pintype "input"))
      (node (ref "U3") (pin "P7") (pinfunction "VSS_P7") (pintype "input"))
      (node (ref "U3") (pin "Q10") (pinfunction "VSS_Q10") (pintype "input"))
      (node (ref "U3") (pin "Q2") (pinfunction "VSS_Q2") (pintype "input"))
      (node (ref "U3") (pin "Q4") (pinfunction "VSS_Q4") (pintype "input"))
      (node (ref "U3") (pin "Q7") (pinfunction "VSS_Q7") (pintype "input"))
      (node (ref "U3") (pin "R1") (pinfunction "VSS_R1") (pintype "input"))
      (node (ref "U3") (pin "R6") (pinfunction "VSS_R6") (pintype "input"))
      (node (ref "U3") (pin "R9") (pinfunction "VSS_R9") (pintype "input"))
      (node (ref "U3") (pin "S1") (pinfunction "VSS_S1") (pintype "input"))
      (node (ref "U3") (pin "S6") (pinfunction "VSS_S6") (pintype "input"))
      (node (ref "U3") (pin "S9") (pinfunction "VSS_S9") (pintype "input"))
      (node (ref "U3") (pin "T3") (pinfunction "VSS_T3") (pintype "input"))
      (node (ref "U3") (pin "T4") (pinfunction "VSS_T4") (pintype "input"))
      (node (ref "U3") (pin "T7") (pinfunction "VSS_T7") (pintype "input"))
      (node (ref "U3") (pin "T8") (pinfunction "VSS_T8") (pintype "input"))
      (node (ref "U3") (pin "U7") (pinfunction "VSS_U7") (pintype "input"))
      (node (ref "U4") (pin "C9") (pinfunction "VSS_C9") (pintype "input"))
      (node (ref "U4") (pin "D3") (pinfunction "VSS_D3") (pintype "input"))
      (node (ref "U4") (pin "D4") (pinfunction "VSS_D4") (pintype "input"))
      (node (ref "U4") (pin "D6") (pinfunction "VSS_D6") (pintype "input"))
      (node (ref "U4") (pin "D9") (pinfunction "VSS_D9") (pintype "input"))
      (node (ref "U4") (pin "E6") (pinfunction "VSS_E6") (pintype "input"))
      (node (ref "U4") (pin "E7") (pinfunction "VSS_E7") (pintype "input"))
      (node (ref "U4") (pin "G3") (pinfunction "VSS_G3") (pintype "input"))
      (node (ref "U4") (pin "G4") (pinfunction "VSS_G4") (pintype "input"))
      (node (ref "U4") (pin "H5") (pinfunction "VSS_H5") (pintype "input"))
      (node (ref "U4") (pin "H6") (pinfunction "VSS_H6") (pintype "input"))
      (node (ref "U4") (pin "I6") (pinfunction "VSS_I6") (pintype "input"))
      (node (ref "U4") (pin "I8") (pinfunction "VSS_I8") (pintype "input"))
      (node (ref "U4") (pin "I9") (pinfunction "VSS_I9") (pintype "input"))
      (node (ref "U4") (pin "J3") (pinfunction "VSS_J3") (pintype "input"))
      (node (ref "U4") (pin "J4") (pinfunction "VSS_J4") (pintype "input"))
      (node (ref "U4") (pin "J9") (pinfunction "VSS_J9") (pintype "input"))
      (node (ref "U4") (pin "L7") (pinfunction "VSS_L7") (pintype "input"))
      (node (ref "U4") (pin "L9") (pinfunction "VSS_L9") (pintype "input"))
      (node (ref "U4") (pin "M3") (pinfunction "VSS_M3") (pintype "input"))
      (node (ref "U4") (pin "M4") (pinfunction "VSS_M4") (pintype "input"))
      (node (ref "U4") (pin "M7") (pinfunction "VSS_M7") (pintype "input"))
      (node (ref "U4") (pin "M8") (pinfunction "VSS_M8") (pintype "input"))
      (node (ref "U4") (pin "M9") (pinfunction "VSS_M9") (pintype "input"))
      (node (ref "U4") (pin "O3") (pinfunction "VSS_O3") (pintype "input"))
      (node (ref "U4") (pin "O4") (pinfunction "VSS_O4") (pintype "input"))
      (node (ref "U4") (pin "P5") (pinfunction "VSS_P5") (pintype "input"))
      (node (ref "U4") (pin "Q5") (pinfunction "VSS_Q5") (pintype "input"))
      (node (ref "U4") (pin "R7") (pinfunction "VSS_R7") (pintype "input"))
      (node (ref "U4") (pin "R8") (pinfunction "VSS_R8") (pintype "input"))
      (node (ref "U4") (pin "S3") (pinfunction "VSS_S3") (pintype "input"))
      (node (ref "U4") (pin "S4") (pinfunction "VSS_S4") (pintype "input"))
      (node (ref "U4") (pin "S8") (pinfunction "VSS_S8") (pintype "input"))
      (node (ref "U4") (pin "U6") (pinfunction "VSS_U6") (pintype "input"))
      (node (ref "U5") (pin "A4") (pinfunction "VSS_A4") (pintype "input"))
      (node (ref "U5") (pin "A6") (pinfunction "VSS_A6") (pintype "input"))
      (node (ref "U5") (pin "B1") (pinfunction "VSS_B1") (pintype "input"))
      (node (ref "U5") (pin "B11") (pinfunction "VSS_B11") (pintype "input"))
      (node (ref "U5") (pin "B2") (pinfunction "VSS_B2") (pintype "input"))
      (node (ref "U5") (pin "B3") (pinfunction "VSS_B3") (pintype "input"))
      (node (ref "U5") (pin "B5") (pinfunction "VSS_B5") (pintype "input"))
      (node (ref "U5") (pin "B7") (pinfunction "VSS_B7") (pintype "input"))
      (node (ref "U5") (pin "C10") (pinfunction "VSS_C10") (pintype "input"))
      (node (ref "U5") (pin "C4") (pinfunction "VSS_C4") (pintype "input"))
      (node (ref "U5") (pin "C9") (pinfunction "VSS_C9") (pintype "input"))
      (node (ref "U5") (pin "D4") (pinfunction "VSS_D4") (pintype "input"))
      (node (ref "U5") (pin "D8") (pinfunction "VSS_D8") (pintype "input"))
      (node (ref "U5") (pin "D9") (pinfunction "VSS_D9") (pintype "input"))
      (node (ref "U5") (pin "E4") (pinfunction "VSS_E4") (pintype "input"))
      (node (ref "U5") (pin "E9") (pinfunction "VSS_E9") (pintype "input"))
      (node (ref "U5") (pin "F4") (pinfunction "VSS_F4") (pintype "input"))
      (node (ref "U5") (pin "F9") (pinfunction "VSS_F9") (pintype "input"))
      (node (ref "U5") (pin "G10") (pinfunction "VSS_G10") (pintype "input"))
      (node (ref "U5") (pin "G11") (pinfunction "VSS_G11") (pintype "input"))
      (node (ref "U5") (pin "G4") (pinfunction "VSS_G4") (pintype "input"))
      (node (ref "U5") (pin "G9") (pinfunction "VSS_G9") (pintype "input"))
      (node (ref "U5") (pin "H11") (pinfunction "VSS_H11") (pintype "input"))
      (node (ref "U5") (pin "H4") (pinfunction "VSS_H4") (pintype "input"))
      (node (ref "U5") (pin "H8") (pinfunction "VSS_H8") (pintype "input"))
      (node (ref "U5") (pin "H9") (pinfunction "VSS_H9") (pintype "input"))
      (node (ref "U5") (pin "I1") (pinfunction "VSS_I1") (pintype "input"))
      (node (ref "U5") (pin "I10") (pinfunction "VSS_I10") (pintype "input"))
      (node (ref "U5") (pin "I2") (pinfunction "VSS_I2") (pintype "input"))
      (node (ref "U5") (pin "I3") (pinfunction "VSS_I3") (pintype "input"))
      (node (ref "U5") (pin "I4") (pinfunction "VSS_I4") (pintype "input"))
      (node (ref "U5") (pin "I8") (pinfunction "VSS_I8") (pintype "input"))
      (node (ref "U5") (pin "J4") (pinfunction "VSS_J4") (pintype "input"))
      (node (ref "U5") (pin "J5") (pinfunction "VSS_J5") (pintype "input"))
      (node (ref "U5") (pin "J6") (pinfunction "VSS_J6") (pintype "input"))
      (node (ref "U5") (pin "J9") (pinfunction "VSS_J9") (pintype "input"))
      (node (ref "U5") (pin "K10") (pinfunction "VSS_K10") (pintype "input"))
      (node (ref "U5") (pin "K9") (pinfunction "VSS_K9") (pintype "input"))
      (node (ref "U5") (pin "L2") (pinfunction "VSS_L2") (pintype "input"))
      (node (ref "U5") (pin "L9") (pinfunction "VSS_L9") (pintype "input"))
      (node (ref "U5") (pin "M1") (pinfunction "VSS_M1") (pintype "input"))
      (node (ref "U5") (pin "M10") (pinfunction "VSS_M10") (pintype "input"))
      (node (ref "U5") (pin "M2") (pinfunction "VSS_M2") (pintype "input"))
      (node (ref "U5") (pin "M8") (pinfunction "VSS_M8") (pintype "input"))
      (node (ref "U5") (pin "M9") (pinfunction "VSS_M9") (pintype "input"))
      (node (ref "U5") (pin "N11") (pinfunction "VSS_N11") (pintype "input"))
      (node (ref "U5") (pin "N3") (pinfunction "VSS_N3") (pintype "input"))
      (node (ref "U5") (pin "N9") (pinfunction "VSS_N9") (pintype "input"))
      (node (ref "U5") (pin "O10") (pinfunction "VSS_O10") (pintype "input"))
      (node (ref "U5") (pin "O4") (pinfunction "VSS_O4") (pintype "input"))
      (node (ref "U5") (pin "O9") (pinfunction "VSS_O9") (pintype "input"))
      (node (ref "U5") (pin "P4") (pinfunction "VSS_P4") (pintype "input"))
      (node (ref "U5") (pin "P9") (pinfunction "VSS_P9") (pintype "input"))
      (node (ref "U5") (pin "Q10") (pinfunction "VSS_Q10") (pintype "input"))
      (node (ref "U5") (pin "Q4") (pinfunction "VSS_Q4") (pintype "input"))
      (node (ref "U5") (pin "Q5") (pinfunction "VSS_Q5") (pintype "input"))
      (node (ref "U5") (pin "Q6") (pinfunction "VSS_Q6") (pintype "input"))
      (node (ref "U5") (pin "Q9") (pinfunction "VSS_Q9") (pintype "input"))
      (node (ref "U5") (pin "R4") (pinfunction "VSS_R4") (pintype "input"))
      (node (ref "U5") (pin "R7") (pinfunction "VSS_R7") (pintype "input"))
      (node (ref "U5") (pin "R9") (pinfunction "VSS_R9") (pintype "input"))
      (node (ref "U5") (pin "S10") (pinfunction "VSS_S10") (pintype "input"))
      (node (ref "U5") (pin "S3") (pinfunction "VSS_S3") (pintype "input"))
      (node (ref "U5") (pin "S7") (pinfunction "VSS_S7") (pintype "input"))
      (node (ref "U5") (pin "T1") (pinfunction "VSS_T1") (pintype "input"))
      (node (ref "U5") (pin "T2") (pinfunction "VSS_T2") (pintype "input"))
      (node (ref "U5") (pin "T7") (pinfunction "VSS_T7") (pintype "input"))
      (node (ref "U5") (pin "U8") (pinfunction "VSS_U8") (pintype "input"))
      (node (ref "U6") (pin "B4") (pinfunction "VSS_B4") (pintype "passive"))
      (node (ref "U6") (pin "B5") (pinfunction "VSS_B5") (pintype "passive"))
      (node (ref "U6") (pin "B6") (pinfunction "VSS_B6") (pintype "passive"))
      (node (ref "U6") (pin "B8") (pinfunction "VSS_B8") (pintype "passive"))
      (node (ref "U6") (pin "C10") (pinfunction "VSS_C10") (pintype "passive"))
      (node (ref "U6") (pin "C9") (pinfunction "VSS_C9") (pintype "passive"))
      (node (ref "U6") (pin "D9") (pinfunction "VSS_D9") (pintype "passive"))
      (node (ref "U6") (pin "E8") (pinfunction "VSS_E8") (pintype "passive"))
      (node (ref "U6") (pin "E9") (pinfunction "VSS_E9") (pintype "passive"))
      (node (ref "U6") (pin "F10") (pinfunction "VSS_F10") (pintype "passive"))
      (node (ref "U6") (pin "F11") (pinfunction "VSS_F11") (pintype "passive"))
      (node (ref "U6") (pin "F8") (pinfunction "VSS_F8") (pintype "passive"))
      (node (ref "U6") (pin "X1") (pinfunction "X1_X1") (pintype "passive"))
      (node (ref "U6") (pin "X10") (pinfunction "X10_X10") (pintype "passive"))
      (node (ref "U6") (pin "X2") (pinfunction "X2_X2") (pintype "passive"))
      (node (ref "U6") (pin "X3") (pinfunction "X3_X3") (pintype "passive"))
      (node (ref "U6") (pin "X4") (pinfunction "X4_X4") (pintype "passive"))
      (node (ref "U6") (pin "X5") (pinfunction "X5_X5") (pintype "passive"))
      (node (ref "U6") (pin "X6") (pinfunction "X6_X6") (pintype "passive"))
      (node (ref "U6") (pin "X7") (pinfunction "X7_X7") (pintype "passive"))
      (node (ref "U6") (pin "X8") (pinfunction "X8_X8") (pintype "passive"))
      (node (ref "U6") (pin "X9") (pinfunction "X9_X9") (pintype "passive"))
      (node (ref "U6") (pin "Y1") (pinfunction "Y1_Y1") (pintype "passive"))
      (node (ref "U6") (pin "Y10") (pinfunction "Y10_Y10") (pintype "passive"))
      (node (ref "U6") (pin "Y2") (pinfunction "Y2_Y2") (pintype "passive"))
      (node (ref "U6") (pin "Y3") (pinfunction "Y3_Y3") (pintype "passive"))
      (node (ref "U6") (pin "Y4") (pinfunction "Y4_Y4") (pintype "passive"))
      (node (ref "U6") (pin "Y5") (pinfunction "Y5_Y5") (pintype "passive"))
      (node (ref "U6") (pin "Y6") (pinfunction "Y6_Y6") (pintype "passive"))
      (node (ref "U6") (pin "Y7") (pinfunction "Y7_Y7") (pintype "passive"))
      (node (ref "U6") (pin "Y8") (pinfunction "Y8_Y8") (pintype "passive"))
      (node (ref "U6") (pin "Y9") (pinfunction "Y9_Y9") (pintype "passive"))
      (node (ref "U6") (pin "Z1") (pinfunction "Z1_Z1") (pintype "passive"))
      (node (ref "U6") (pin "Z10") (pinfunction "Z10_Z10") (pintype "passive"))
      (node (ref "U6") (pin "Z2") (pinfunction "Z2_Z2") (pintype "passive"))
      (node (ref "U6") (pin "Z3") (pinfunction "Z3_Z3") (pintype "passive"))
      (node (ref "U6") (pin "Z4") (pinfunction "Z4_Z4") (pintype "passive"))
      (node (ref "U6") (pin "Z5") (pinfunction "Z5_Z5") (pintype "passive"))
      (node (ref "U6") (pin "Z6") (pinfunction "Z6_Z6") (pintype "passive"))
      (node (ref "U6") (pin "Z7") (pinfunction "Z7_Z7") (pintype "passive"))
      (node (ref "U6") (pin "Z8") (pinfunction "Z8_Z8") (pintype "passive"))
      (node (ref "U6") (pin "Z9") (pinfunction "Z9_Z9") (pintype "passive"))
    )
    (net (code "63") (name "/eos34_hs_clk_n") (class "Default")
      (node (ref "J1") (pin "T9") (pintype "input"))
      (node (ref "U6") (pin "D1") (pinfunction "pad_hs_clk_n_D1") (pintype "passive"))
    )
    (net (code "64") (name "/eos34_hs_clk_p") (class "Default")
      (node (ref "J1") (pin "T8") (pintype "input"))
      (node (ref "U6") (pin "C1") (pinfunction "pad_hs_clk_p_C1") (pintype "passive"))
    )
    (net (code "65") (name "/eos34_sigIn_0") (class "Default")
      (node (ref "J1") (pin "T7") (pintype "input"))
      (node (ref "U6") (pin "A1") (pinfunction "SigIn[0]_A1") (pintype "passive"))
    )
    (net (code "66") (name "/eos34_sigIn_1") (class "Default")
      (node (ref "J1") (pin "T6") (pintype "input"))
      (node (ref "U6") (pin "A2") (pinfunction "SigIn[1]_A2") (pintype "passive"))
    )
    (net (code "67") (name "/eos34_sigIn_2") (class "Default")
      (node (ref "J1") (pin "T5") (pintype "input"))
      (node (ref "U6") (pin "A3") (pinfunction "SigIn[2]_A3") (pintype "passive"))
    )
    (net (code "68") (name "/eos34_sigIn_3") (class "Default")
      (node (ref "J1") (pin "T4") (pintype "input"))
      (node (ref "U6") (pin "A4") (pinfunction "SigIn[3]_A4") (pintype "passive"))
    )
    (net (code "69") (name "/eos34_sigIn_4") (class "Default")
      (node (ref "J1") (pin "R4") (pintype "input"))
      (node (ref "U6") (pin "A5") (pinfunction "SigIn[4]_A5") (pintype "passive"))
    )
    (net (code "70") (name "/eos34_sigIn_5") (class "Default")
      (node (ref "J1") (pin "P4") (pintype "input"))
      (node (ref "U6") (pin "A6") (pinfunction "SigIn[5]_A6") (pintype "passive"))
    )
    (net (code "71") (name "/eos34_sigIn_6") (class "Default")
      (node (ref "J1") (pin "N4") (pintype "input"))
      (node (ref "U6") (pin "A7") (pinfunction "SigIn[6]_A7") (pintype "passive"))
    )
    (net (code "72") (name "/eos34_sigIn_7") (class "Default")
      (node (ref "J1") (pin "T16") (pintype "input"))
      (node (ref "U6") (pin "G1") (pinfunction "SigIn[7]_G1") (pintype "passive"))
    )
    (net (code "73") (name "/eos34_sigIn_8") (class "Default")
      (node (ref "J1") (pin "T15") (pintype "input"))
      (node (ref "U6") (pin "G2") (pinfunction "SigIn[8]_G2") (pintype "passive"))
    )
    (net (code "74") (name "/eos34_sigIn_9") (class "Default")
      (node (ref "J1") (pin "T14") (pintype "input"))
      (node (ref "U6") (pin "G3") (pinfunction "SigIn[9]_G3") (pintype "passive"))
    )
    (net (code "75") (name "/eos34_sigIn_10") (class "Default")
      (node (ref "J1") (pin "T10") (pintype "input"))
      (node (ref "U6") (pin "G4") (pinfunction "SigIn[10]_G4") (pintype "passive"))
    )
    (net (code "76") (name "/eos34_sigIn_11") (class "Default")
      (node (ref "J1") (pin "T13") (pintype "input"))
      (node (ref "U6") (pin "G5") (pinfunction "SigIn[11]_G5") (pintype "passive"))
    )
    (net (code "77") (name "/eos34_sigIn_12") (class "Default")
      (node (ref "J1") (pin "T12") (pintype "input"))
      (node (ref "U6") (pin "G6") (pinfunction "SigIn[12]_G6") (pintype "passive"))
    )
    (net (code "78") (name "/eos34_sigIn_13") (class "Default")
      (node (ref "J1") (pin "T11") (pintype "input"))
      (node (ref "U6") (pin "G7") (pinfunction "SigIn[13]_G7") (pintype "passive"))
    )
    (net (code "79") (name "/equip__PulseCurver_Anode_v_E5") (class "Default")
      (node (ref "J1") (pin "M18") (pintype "input"))
      (node (ref "U1") (pin "O9") (pinfunction "PulseCurver_Anode_v_E5_O9") (pintype "input"))
    )
    (net (code "80") (name "/equip__PulseCurver_Anode_v_E12") (class "Default")
      (node (ref "J1") (pin "L18") (pintype "input"))
      (node (ref "U1") (pin "F9") (pinfunction "PulseCurver_Anode_v_E12_F9") (pintype "input"))
    )
    (net (code "81") (name "/equip__PulseCurver_Anode_v_E20") (class "Default")
      (node (ref "J1") (pin "J19") (pintype "input"))
      (node (ref "U1") (pin "O5") (pinfunction "PulseCurver_Anode_v_E20_O5") (pintype "input"))
    )
    (net (code "82") (name "/equip__PulseCurver_Anode_v_E26") (class "Default")
      (node (ref "J1") (pin "K19") (pintype "input"))
      (node (ref "U1") (pin "G5") (pinfunction "PulseCurver_Anode_v_E26_G5") (pintype "input"))
    )
    (net (code "83") (name "/equip__PulseCurver_Anode_v_E30") (class "Default")
      (node (ref "J1") (pin "H19") (pintype "input"))
      (node (ref "U1") (pin "U2") (pinfunction "PulseCurver_Anode_v_E30_U2") (pintype "input"))
    )
    (net (code "84") (name "/equip__PulseCurver_Cathode_v_E5") (class "Default")
      (node (ref "J1") (pin "M19") (pintype "input"))
      (node (ref "U1") (pin "N9") (pinfunction "PulseCurver_Cathode_v_E5_N9") (pintype "input"))
    )
    (net (code "85") (name "/equip__PulseCurver_Cathode_v_E12") (class "Default")
      (node (ref "J1") (pin "L19") (pintype "input"))
      (node (ref "U1") (pin "E9") (pinfunction "PulseCurver_Cathode_v_E12_E9") (pintype "input"))
    )
    (net (code "86") (name "/equip__PulseCurver_Cathode_v_E20") (class "Default")
      (node (ref "J1") (pin "J18") (pintype "input"))
      (node (ref "U1") (pin "N5") (pinfunction "PulseCurver_Cathode_v_E20_N5") (pintype "input"))
    )
    (net (code "87") (name "/equip__PulseCurver_Cathode_v_E26") (class "Default")
      (node (ref "J1") (pin "K18") (pintype "input"))
      (node (ref "U1") (pin "F5") (pinfunction "PulseCurver_Cathode_v_E26_F5") (pintype "input"))
    )
    (net (code "88") (name "/equip__PulseCurver_Cathode_v_E30") (class "Default")
      (node (ref "J1") (pin "H18") (pintype "input"))
      (node (ref "U1") (pin "T2") (pinfunction "PulseCurver_Cathode_v_E30_T2") (pintype "input"))
    )
    (net (code "89") (name "/fpa__hs_clk_n") (class "Default")
      (node (ref "J1") (pin "H16") (pintype "input"))
      (node (ref "U3") (pin "U5") (pinfunction "HS_CLK_N_U5") (pintype "input"))
    )
    (net (code "90") (name "/fpa__hs_clk_p") (class "Default")
      (node (ref "J1") (pin "J16") (pintype "input"))
      (node (ref "U3") (pin "U6") (pinfunction "HS_CLK_P_U6") (pintype "input"))
    )
    (net (code "91") (name "/sig_A1") (class "Default")
      (node (ref "J1") (pin "A1") (pintype "input"))
      (node (ref "U1") (pin "M4") (pinfunction "SPS_heater_GND_0_v_E20_M4") (pintype "input"))
      (node (ref "U2") (pin "208") (pinfunction "H_1__15_208") (pintype "passive"))
      (node (ref "U4") (pin "U5") (pinfunction "S_ENABLE_2_U5") (pintype "input"))
      (node (ref "U5") (pin "N4") (pinfunction "Iref_Cml_N4") (pintype "input"))
    )
    (net (code "92") (name "/sig_A2") (class "Default")
      (node (ref "J1") (pin "A2") (pintype "input"))
      (node (ref "U1") (pin "M5") (pinfunction "Idler_HeaterLabelRight_ring_2_v_E20_M5") (pintype "input"))
      (node (ref "U2") (pin "205") (pinfunction "IBIAS_1__15_205") (pintype "passive"))
      (node (ref "U4") (pin "U4") (pinfunction "s_in_2_U4") (pintype "input"))
      (node (ref "U5") (pin "F8") (pinfunction "VPD_test_F8") (pintype "input"))
    )
    (net (code "93") (name "/sig_A3") (class "Default")
      (node (ref "J1") (pin "A3") (pintype "input"))
      (node (ref "U1") (pin "L1") (pinfunction "Idler_HeaterLabelRight_ring_1_v_E30_L1") (pintype "input"))
      (node (ref "U2") (pin "207") (pinfunction "IBIAS_3__15_207") (pintype "passive"))
      (node (ref "U4") (pin "S2") (pinfunction "AnalogLinks_IREF_S2") (pintype "input"))
    )
    (net (code "94") (name "/sig_A4") (class "Default")
      (node (ref "J1") (pin "A4") (pintype "input"))
      (node (ref "U1") (pin "L2") (pinfunction "Idler_HeaterLabelRight_ring_2_v_E30_L2") (pintype "input"))
      (node (ref "U2") (pin "234") (pinfunction "IBIAS_1__17_234") (pintype "passive"))
      (node (ref "U4") (pin "T1") (pinfunction "AnalogLinks_s_in_top_T1") (pintype "input"))
    )
    (net (code "95") (name "/sig_A5") (class "Default")
      (node (ref "J1") (pin "A5") (pintype "input"))
      (node (ref "U1") (pin "L3") (pinfunction "input_PD_anode_v_E30_L3") (pintype "input"))
      (node (ref "U2") (pin "239") (pinfunction "H_3__17_239") (pintype "passive"))
      (node (ref "U4") (pin "P2") (pinfunction "AnalogLinks_TxIn_9_N_P2") (pintype "input"))
    )
    (net (code "96") (name "/sig_A6") (class "Default")
      (node (ref "J1") (pin "A6") (pintype "input"))
      (node (ref "U1") (pin "L4") (pinfunction "Idler_HeaterLabelRight_ring_0_v_E20_L4") (pintype "input"))
      (node (ref "U2") (pin "236") (pinfunction "IBIAS_3__17_236") (pintype "passive"))
      (node (ref "U4") (pin "O2") (pinfunction "AnalogLinks_TxIn_9_P_O2") (pintype "input"))
    )
    (net (code "97") (name "/sig_A7") (class "Default")
      (node (ref "J1") (pin "A7") (pintype "input"))
      (node (ref "U1") (pin "L5") (pinfunction "Idler_HeaterLabelRight_ring_3_v_E20_L5") (pintype "input"))
      (node (ref "U2") (pin "252") (pinfunction "IBIAS_3__18_252") (pintype "passive"))
      (node (ref "U4") (pin "P1") (pinfunction "AnalogLinks_Rx_9_N_P1") (pintype "input"))
    )
    (net (code "98") (name "/sig_A8") (class "Default")
      (node (ref "J1") (pin "A8") (pintype "input"))
      (node (ref "U1") (pin "I3") (pinfunction "Signal_PD_anode_3_0_sig_fill_test_I3") (pintype "input"))
      (node (ref "U2") (pin "255") (pinfunction "H_3__18_255") (pintype "passive"))
      (node (ref "U4") (pin "O1") (pinfunction "AnalogLinks_Rx_9_P_O1") (pintype "input"))
    )
    (net (code "99") (name "/sig_A9") (class "Default")
      (node (ref "J1") (pin "A9") (pintype "input"))
      (node (ref "U1") (pin "I4") (pinfunction "ASE_HeaterLabelRight_ring_1_v_E26_I4") (pintype "input"))
      (node (ref "U2") (pin "251") (pinfunction "IBIAS_2__18_251") (pintype "passive"))
      (node (ref "U4") (pin "M2") (pinfunction "AnalogLinks_TxIn_10_P_M2") (pintype "input"))
    )
    (net (code "100") (name "/sig_A10") (class "Default")
      (node (ref "J1") (pin "A10") (pintype "input"))
      (node (ref "U1") (pin "G1") (pinfunction "Signal_HeaterLabelLeft_ring_0_1_fil_test_G1") (pintype "input"))
      (node (ref "U2") (pin "262") (pinfunction "IBIAS_0__19_262") (pintype "passive"))
      (node (ref "U4") (pin "N1") (pinfunction "AnalogLinks_Rx_10_N_N1") (pintype "input"))
    )
    (net (code "101") (name "/sig_A11") (class "Default")
      (node (ref "J1") (pin "A11") (pintype "input"))
      (node (ref "U1") (pin "G2") (pinfunction "Signal_HeaterLabelLeft_ring_3_0_fil_test_G2") (pintype "input"))
      (node (ref "U2") (pin "266") (pinfunction "H_1__19_266") (pintype "passive"))
      (node (ref "U4") (pin "M1") (pinfunction "AnalogLinks_Rx_10_P_M1") (pintype "input"))
    )
    (net (code "102") (name "/sig_A12") (class "Default")
      (node (ref "J1") (pin "A12") (pintype "input"))
      (node (ref "U1") (pin "G4") (pinfunction "Signal_HeaterLabelRight_ring_1_v_E26_G4") (pintype "input"))
      (node (ref "U2") (pin "283") (pinfunction "H_2__20_283") (pintype "passive"))
      (node (ref "U4") (pin "L2") (pinfunction "AnalogLinks_TxIn_11_N_L2") (pintype "input"))
    )
    (net (code "103") (name "/sig_A13") (class "Default")
      (node (ref "J1") (pin "A13") (pintype "input"))
      (node (ref "U1") (pin "F1") (pinfunction "Signal_HeaterLabelLeft_ring_1_1_fil_test_F1") (pintype "input"))
      (node (ref "U2") (pin "279") (pinfunction "IBIAS_1__20_279") (pintype "passive"))
      (node (ref "U4") (pin "K2") (pinfunction "AnalogLinks_TxIn_11_P_K2") (pintype "input"))
    )
    (net (code "104") (name "/sig_A14") (class "Default")
      (node (ref "J1") (pin "A14") (pintype "input"))
      (node (ref "U1") (pin "E4") (pinfunction "Signal_HeaterLabelRight_ring_3_v_E26_E4") (pintype "input"))
      (node (ref "U2") (pin "291") (pinfunction "IBIAS_0__21_291") (pintype "passive"))
      (node (ref "U4") (pin "J1") (pinfunction "AnalogLinks_Rx_12_N_J1") (pintype "input"))
    )
    (net (code "105") (name "/sig_A15") (class "Default")
      (node (ref "J1") (pin "A15") (pintype "input"))
      (node (ref "U1") (pin "E5") (pinfunction "Idler_HeaterLabelRight_ring_2_v_E26_E5") (pintype "input"))
      (node (ref "U2") (pin "295") (pinfunction "H_1__21_295") (pintype "passive"))
    )
    (net (code "106") (name "/sig_A16") (class "Default")
      (node (ref "J1") (pin "A16") (pintype "input"))
      (node (ref "U1") (pin "C1") (pinfunction "ASE_HeaterLabelLeft_ring_1_comb_6_fil_test_C1") (pintype "input"))
      (node (ref "U2") (pin "292") (pinfunction "IBIAS_1__21_292") (pintype "passive"))
      (node (ref "U4") (pin "J2") (pinfunction "AnalogLinks_TxIn_12_N_J2") (pintype "input"))
    )
    (net (code "107") (name "/sig_A17") (class "Default")
      (node (ref "J1") (pin "A17") (pintype "input"))
      (node (ref "U1") (pin "C2") (pinfunction "Signal_HeaterLabelLeft_ring_3_1_fil_test_C2") (pintype "input"))
      (node (ref "U2") (pin "308") (pinfunction "IBIAS_1__22_308") (pintype "passive"))
      (node (ref "U4") (pin "H1") (pinfunction "AnalogLinks_Rx_13_N_H1") (pintype "input"))
    )
    (net (code "108") (name "/sig_A18") (class "Default")
      (node (ref "J1") (pin "A18") (pintype "input"))
      (node (ref "U1") (pin "C3") (pinfunction "ASE_anode_1_6_comp_test_C3") (pintype "input"))
      (node (ref "U2") (pin "311") (pinfunction "H_1__22_311") (pintype "passive"))
      (node (ref "U4") (pin "F2") (pinfunction "AnalogLinks_TxIn_14_N_F2") (pintype "input"))
    )
    (net (code "109") (name "/sig_A19") (class "Default")
      (node (ref "J1") (pin "A19") (pintype "input"))
      (node (ref "U1") (pin "C4") (pinfunction "Idler_HeaterLabelRight_ring_0_v_E26_C4") (pintype "input"))
      (node (ref "U2") (pin "307") (pinfunction "IBIAS_0__22_307") (pintype "passive"))
      (node (ref "U4") (pin "E2") (pinfunction "AnalogLinks_TxIn_14_P_E2") (pintype "input"))
    )
    (net (code "110") (name "/sig_B1") (class "Default")
      (node (ref "J1") (pin "B1") (pintype "input"))
      (node (ref "U1") (pin "O4") (pinfunction "Signal_HeaterLabelRight_ring_2_v_E20_O4") (pintype "input"))
      (node (ref "U2") (pin "204") (pinfunction "IBIAS_0__15_204") (pintype "passive"))
      (node (ref "U4") (pin "L6") (pinfunction "IREF_L6") (pintype "input"))
      (node (ref "U5") (pin "O5") (pinfunction "Iref_Global_O5") (pintype "input"))
    )
    (net (code "111") (name "/sig_B2") (class "Default")
      (node (ref "J1") (pin "B2") (pintype "input"))
      (node (ref "U1") (pin "N1") (pinfunction "SPS_heater_VDD_0_v_E30_N1") (pintype "input"))
      (node (ref "U2") (pin "206") (pinfunction "IBIAS_2__15_206") (pintype "passive"))
      (node (ref "U4") (pin "J6") (pinfunction "IREF_CML_J6") (pintype "input"))
      (node (ref "U5") (pin "C8") (pinfunction "s_out_1_C8") (pintype "input"))
    )
    (net (code "112") (name "/sig_B3") (class "Default")
      (node (ref "J1") (pin "B3") (pintype "input"))
      (node (ref "U1") (pin "N2") (pinfunction "through_PD_anode_V_E30_N2") (pintype "input"))
      (node (ref "U2") (pin "223") (pinfunction "IBIAS_3__16_223") (pintype "passive"))
      (node (ref "U4") (pin "U3") (pinfunction "AnalogLinks_s_out_top_U3") (pintype "input"))
    )
    (net (code "113") (name "/sig_B4") (class "Default")
      (node (ref "J1") (pin "B4") (pintype "input"))
      (node (ref "U1") (pin "M3") (pinfunction "Source_PD_Anode_v_E30_M3") (pintype "input"))
      (node (ref "U2") (pin "226") (pinfunction "H_3__16_226") (pintype "passive"))
      (node (ref "U4") (pin "U1") (pinfunction "AnalogLinks_s_enable_top_U1") (pintype "input"))
    )
    (net (code "114") (name "/sig_B5") (class "Default")
      (node (ref "J1") (pin "B5") (pintype "input"))
      (node (ref "U1") (pin "M2") (pinfunction "Idler_HeaterLabelRight_ring_3_v_E30_M2") (pintype "input"))
      (node (ref "U2") (pin "238") (pinfunction "H_2__17_238") (pintype "passive"))
      (node (ref "U4") (pin "Q1") (pinfunction "AnalogLinks_Rx_8_P_Q1") (pintype "input"))
    )
    (net (code "115") (name "/sig_B6") (class "Default")
      (node (ref "J1") (pin "B6") (pintype "input"))
      (node (ref "U1") (pin "M1") (pinfunction "Idler_HeaterLabelRight_ring_0_v_E30_M1") (pintype "input"))
      (node (ref "U2") (pin "235") (pinfunction "IBIAS_2__17_235") (pintype "passive"))
      (node (ref "U4") (pin "R1") (pinfunction "AnalogLinks_Rx_8_N_R1") (pintype "input"))
    )
    (net (code "116") (name "/sig_B7") (class "Default")
      (node (ref "J1") (pin "B7") (pintype "input"))
      (node (ref "U1") (pin "N3") (pinfunction "idler_PD_anode_3_v_E30_N3") (pintype "input"))
      (node (ref "U2") (pin "254") (pinfunction "H_2__18_254") (pintype "passive"))
      (node (ref "U4") (pin "R2") (pinfunction "AnalogLinks_TxIn_8_N_R2") (pintype "input"))
    )
    (net (code "117") (name "/sig_B8") (class "Default")
      (node (ref "J1") (pin "B8") (pintype "input"))
      (node (ref "U1") (pin "J1") (pinfunction "Signal_HeaterLabelLeft_ring_1_2_fil_test_J1") (pintype "input"))
      (node (ref "U2") (pin "250") (pinfunction "IBIAS_1__18_250") (pintype "passive"))
      (node (ref "U4") (pin "Q2") (pinfunction "AnalogLinks_TxIn_8_P_Q2") (pintype "input"))
    )
    (net (code "118") (name "/sig_B9") (class "Default")
      (node (ref "J1") (pin "B9") (pintype "input"))
      (node (ref "U1") (pin "J2") (pinfunction "Signal_PD_anode_1_2_sig_fil_test_J2") (pintype "input"))
      (node (ref "U2") (pin "253") (pinfunction "H_1__18_253") (pintype "passive"))
      (node (ref "U4") (pin "N2") (pinfunction "AnalogLinks_TxIn_10_N_N2") (pintype "input"))
    )
    (net (code "119") (name "/sig_B10") (class "Default")
      (node (ref "J1") (pin "B10") (pintype "input"))
      (node (ref "U1") (pin "I2") (pinfunction "Signal_PD_anode_2_2_sig_fil_test_I2") (pintype "input"))
      (node (ref "U2") (pin "263") (pinfunction "IBIAS_1__19_263") (pintype "passive"))
      (node (ref "U4") (pin "L1") (pinfunction "AnalogLinks_Rx_11_N_L1") (pintype "input"))
    )
    (net (code "120") (name "/sig_B11") (class "Default")
      (node (ref "J1") (pin "B11") (pintype "input"))
      (node (ref "U1") (pin "I1") (pinfunction "Signal_HeaterLabelLeft_ring_2_2_fil_test_I1") (pintype "input"))
      (node (ref "U2") (pin "267") (pinfunction "H_2__19_267") (pintype "passive"))
      (node (ref "U4") (pin "K1") (pinfunction "AnalogLinks_Rx_11_P_K1") (pintype "input"))
    )
    (net (code "121") (name "/sig_B12") (class "Default")
      (node (ref "J1") (pin "B12") (pintype "input"))
      (node (ref "U1") (pin "J5") (pinfunction "signal_PD_anode_0_0_sig_fil_test_J5") (pintype "input"))
      (node (ref "U2") (pin "280") (pinfunction "IBIAS_2__20_280") (pintype "passive"))
      (node (ref "U4") (pin "G2") (pinfunction "AnalogLinks_TxIn_13_P_G2") (pintype "input"))
    )
    (net (code "122") (name "/sig_B13") (class "Default")
      (node (ref "J1") (pin "B13") (pintype "input"))
      (node (ref "U1") (pin "J4") (pinfunction "ASE_HeaterLabelRight_ring_0_v_E26_J4") (pintype "input"))
      (node (ref "U2") (pin "282") (pinfunction "H_1__20_282") (pintype "passive"))
      (node (ref "U4") (pin "H2") (pinfunction "AnalogLinks_TxIn_13_N_H2") (pintype "input"))
    )
    (net (code "123") (name "/sig_B14") (class "Default")
      (node (ref "J1") (pin "B14") (pintype "input"))
      (node (ref "U1") (pin "H4") (pinfunction "Signal_HeaterLabelRight_ring_0_v_E26_H4") (pintype "input"))
      (node (ref "U2") (pin "296") (pinfunction "H_2__21_296") (pintype "passive"))
      (node (ref "U4") (pin "I1") (pinfunction "AnalogLinks_Rx_12_P_I1") (pintype "input"))
    )
    (net (code "124") (name "/sig_B15") (class "Default")
      (node (ref "J1") (pin "B15") (pintype "input"))
      (node (ref "U1") (pin "E3") (pinfunction "Source_PD_Anode_2_comb_test_E3") (pintype "input"))
      (node (ref "U2") (pin "293") (pinfunction "IBIAS_2__21_293") (pintype "passive"))
    )
    (net (code "125") (name "/sig_B16") (class "Default")
      (node (ref "J1") (pin "B16") (pintype "input"))
      (node (ref "U1") (pin "E2") (pinfunction "Signal_HeaterLabelLeft_ring_1_0_fil_test_E2") (pintype "input"))
      (node (ref "U2") (pin "309") (pinfunction "IBIAS_2__22_309") (pintype "passive"))
      (node (ref "U4") (pin "I2") (pinfunction "AnalogLinks_TxIn_12_P_I2") (pintype "input"))
    )
    (net (code "126") (name "/sig_B17") (class "Default")
      (node (ref "J1") (pin "B17") (pintype "input"))
      (node (ref "U1") (pin "E1") (pinfunction "SPS_heater_VDD_0_2_fil_test_E1") (pintype "input"))
      (node (ref "U2") (pin "312") (pinfunction "H_2__22_312") (pintype "passive"))
      (node (ref "U4") (pin "G1") (pinfunction "AnalogLinks_Rx_13_P_G1") (pintype "input"))
    )
    (net (code "127") (name "/sig_B18") (class "Default")
      (node (ref "J1") (pin "B18") (pintype "input"))
      (node (ref "U1") (pin "F4") (pinfunction "Signal_HeaterLabelRight_ring_2_v_E26_F4") (pintype "input"))
      (node (ref "U2") (pin "325") (pinfunction "H_2__23_325") (pintype "passive"))
      (node (ref "U4") (pin "F1") (pinfunction "AnalogLinks_Rx_14_N_F1") (pintype "input"))
    )
    (net (code "128") (name "/sig_B19") (class "Default")
      (node (ref "J1") (pin "B19") (pintype "input"))
      (node (ref "U1") (pin "B1") (pinfunction "SPS_heater_VDD_0_1_src_test_v1_B1") (pintype "input"))
      (node (ref "U2") (pin "322") (pinfunction "IBIAS_2__23_322") (pintype "passive"))
      (node (ref "U4") (pin "E1") (pinfunction "AnalogLinks_Rx_14_P_E1") (pintype "input"))
    )
    (net (code "129") (name "/sig_C1") (class "Default")
      (node (ref "J1") (pin "C1") (pintype "input"))
      (node (ref "U1") (pin "O3") (pinfunction "idler_PD_anode_2_v_E30_O3") (pintype "input"))
      (node (ref "U2") (pin "192") (pinfunction "IBIAS_1__14_192") (pintype "passive"))
      (node (ref "U4") (pin "U9") (pinfunction "AnalogLinks_s_out_bottom_U9") (pintype "input"))
    )
    (net (code "130") (name "/sig_C2") (class "Default")
      (node (ref "J1") (pin "C2") (pintype "input"))
      (node (ref "U1") (pin "O2") (pinfunction "debug_PD_anode_v_E30_O2") (pintype "input"))
      (node (ref "U2") (pin "210") (pinfunction "H_3__15_210") (pintype "passive"))
      (node (ref "U4") (pin "U8") (pinfunction "S_OUT_2_U8") (pintype "input"))
      (node (ref "U5") (pin "C5") (pinfunction "s_in_1_C5") (pintype "input"))
    )
    (net (code "131") (name "/sig_C3") (class "Default")
      (node (ref "J1") (pin "C3") (pintype "input"))
      (node (ref "U1") (pin "O1") (pinfunction "Signal_HeaterLabelRight_ring_3_v_E30_O1") (pintype "input"))
      (node (ref "U2") (pin "221") (pinfunction "IBIAS_1__16_221") (pintype "passive"))
    )
    (net (code "132") (name "/sig_C4") (class "Default")
      (node (ref "J1") (pin "C4") (pintype "input"))
      (node (ref "U1") (pin "P4") (pinfunction "Signal_HeaterLabelRight_ring_1_v_E20_P4") (pintype "input"))
      (node (ref "U2") (pin "222") (pinfunction "IBIAS_2__16_222") (pintype "passive"))
    )
    (net (code "133") (name "/sig_C5") (class "Default")
      (node (ref "J1") (pin "C5") (pintype "input"))
      (node (ref "U1") (pin "P3") (pinfunction "idler_PD_anode_1_v_E30_P3") (pintype "input"))
      (node (ref "U2") (pin "237") (pinfunction "H_1__17_237") (pintype "passive"))
    )
    (net (code "134") (name "/sig_C6") (class "Default")
      (node (ref "J1") (pin "C6") (pintype "input"))
      (node (ref "U1") (pin "P2") (pinfunction "ASE_anode_1_v_E30_P2") (pintype "input"))
      (node (ref "U2") (pin "233") (pinfunction "IBIAS_0__17_233") (pintype "passive"))
    )
    (net (code "135") (name "/sig_C7") (class "Default")
      (node (ref "J1") (pin "C7") (pintype "input"))
      (node (ref "U1") (pin "N4") (pinfunction "Signal_HeaterLabelRight_ring_3_v_E20_N4") (pintype "input"))
      (node (ref "U2") (pin "249") (pinfunction "IBIAS_0__18_249") (pintype "passive"))
    )
    (net (code "136") (name "/sig_C8") (class "Default")
      (node (ref "J1") (pin "C8") (pintype "input"))
      (node (ref "U1") (pin "K5") (pinfunction "signal_PD_anode_1_0_sig_fil_test_K5") (pintype "input"))
      (node (ref "U2") (pin "265") (pinfunction "IBIAS_3__19_265") (pintype "passive"))
    )
    (net (code "137") (name "/sig_C9") (class "Default")
      (node (ref "J1") (pin "C9") (pintype "input"))
      (node (ref "U1") (pin "K4") (pinfunction "PulseCurver_heater_GND_v_E26_K4") (pintype "input"))
      (node (ref "U2") (pin "268") (pinfunction "H_3__19_268") (pintype "passive"))
    )
    (net (code "138") (name "/sig_C10") (class "Default")
      (node (ref "J1") (pin "C10") (pintype "input"))
      (node (ref "U1") (pin "K3") (pinfunction "Signal_PD_anode_3_1_sig_fil_test_K3") (pintype "input"))
      (node (ref "U2") (pin "264") (pinfunction "IBIAS_2__19_264") (pintype "passive"))
      (node (ref "U4") (pin "B10") (pinfunction "TX_CATHODE_BIAS_B10") (pintype "input"))
      (node (ref "U4") (pin "B2") (pinfunction "TX_CATHODE_BIAS_B2") (pintype "input"))
      (node (ref "U4") (pin "U10") (pinfunction "TX_CATHODE_BIAS_U10") (pintype "input"))
      (node (ref "U4") (pin "U2") (pinfunction "TX_CATHODE_BIAS_U2") (pintype "input"))
    )
    (net (code "139") (name "/sig_C11") (class "Default")
      (node (ref "J1") (pin "C11") (pintype "input"))
      (node (ref "U1") (pin "K2") (pinfunction "Signal_PD_anode_0_2_sig_fil_test_K2") (pintype "input"))
      (node (ref "U2") (pin "284") (pinfunction "H_3__20_284") (pintype "passive"))
      (node (ref "U4") (pin "A10") (pinfunction "TX_ANODE_BIAS_A10") (pintype "input"))
      (node (ref "U4") (pin "A2") (pinfunction "TX_ANODE_BIAS_A2") (pintype "input"))
      (node (ref "U4") (pin "T10") (pinfunction "TX_ANODE_BIAS_T10") (pintype "input"))
      (node (ref "U4") (pin "T2") (pinfunction "TX_ANODE_BIAS_T2") (pintype "input"))
    )
    (net (code "140") (name "/sig_C12") (class "Default")
      (node (ref "J1") (pin "C12") (pintype "input"))
      (node (ref "U1") (pin "K1") (pinfunction "Signal_HeaterLabelLeft_ring_0_2_fil_test_K1") (pintype "input"))
      (node (ref "U2") (pin "281") (pinfunction "IBIAS_3__20_281") (pintype "passive"))
      (node (ref "U4") (pin "B11") (pinfunction "VCM_AL_B11") (pintype "input"))
    )
    (net (code "141") (name "/sig_C13") (class "Default")
      (node (ref "J1") (pin "C13") (pintype "input"))
      (node (ref "U1") (pin "J3") (pinfunction "Signal_PD_anode_2_0_sig_fil_test_J3") (pintype "input"))
      (node (ref "U2") (pin "278") (pinfunction "IBIAS_0__20_278") (pintype "passive"))
      (node (ref "U4") (pin "A11") (pinfunction "VCM_AL_OUT_A11") (pintype "input"))
    )
    (net (code "142") (name "/sig_C14") (class "Default")
      (node (ref "J1") (pin "C14") (pintype "input"))
      (node (ref "U1") (pin "H3") (pinfunction "Signal_PD_anode_0_1_sig_fil_test_H3") (pintype "input"))
      (node (ref "U2") (pin "294") (pinfunction "IBIAS_3__21_294") (pintype "passive"))
    )
    (net (code "143") (name "/sig_C15") (class "Default")
      (node (ref "J1") (pin "C15") (pintype "input"))
      (node (ref "U1") (pin "H2") (pinfunction "Signal_PD_anode_3_2_sig_fil_test_H2") (pintype "input"))
      (node (ref "U2") (pin "297") (pinfunction "H_3__21_297") (pintype "passive"))
    )
    (net (code "144") (name "/sig_C16") (class "Default")
      (node (ref "J1") (pin "C16") (pintype "input"))
      (node (ref "U1") (pin "H1") (pinfunction "Signal_HeaterLabelLeft_ring_3_2_fil_test_H1") (pintype "input"))
      (node (ref "U2") (pin "313") (pinfunction "H_3__22_313") (pintype "passive"))
    )
    (net (code "145") (name "/sig_C17") (class "Default")
      (node (ref "J1") (pin "C17") (pintype "input"))
      (node (ref "U1") (pin "I5") (pinfunction "Idler_HeaterLabelRight_ring_1_v_E26_I5") (pintype "input"))
      (node (ref "U2") (pin "310") (pinfunction "IBIAS_3__22_310") (pintype "passive"))
    )
    (net (code "146") (name "/sig_C18") (class "Default")
      (node (ref "J1") (pin "C18") (pintype "input"))
      (node (ref "U1") (pin "F3") (pinfunction "Signal_PD_anode_2_1_sig_fil_test_F3") (pintype "input"))
      (node (ref "U2") (pin "321") (pinfunction "IBIAS_1__23_321") (pintype "passive"))
      (node (ref "U4") (pin "C2") (pinfunction "AnalogLinks_TxIn_15_P_C2") (pintype "input"))
    )
    (net (code "147") (name "/sig_C19") (class "Default")
      (node (ref "J1") (pin "C19") (pintype "input"))
      (node (ref "U1") (pin "B2") (pinfunction "Signal_HeaterLabelLeft_ring_2_1_fil_test_B2") (pintype "input"))
      (node (ref "U2") (pin "326") (pinfunction "H_3__23_326") (pintype "passive"))
      (node (ref "U4") (pin "D2") (pinfunction "AnalogLinks_TxIn_15_N_D2") (pintype "input"))
    )
    (net (code "148") (name "/sig_D1") (class "Default")
      (node (ref "J1") (pin "D1") (pintype "input"))
      (node (ref "U1") (pin "Q4") (pinfunction "Signal_HeaterLabelRight_ring_0_v_E20_Q4") (pintype "input"))
      (node (ref "U2") (pin "196") (pinfunction "H_2__14_196") (pintype "passive"))
      (node (ref "U4") (pin "S10") (pinfunction "AnalogLinks_s_in_bottom_S10") (pintype "input"))
      (node (ref "U5") (pin "U2") (pinfunction "s_enable_2_U2") (pintype "input"))
    )
    (net (code "149") (name "/sig_D2") (class "Default")
      (node (ref "J1") (pin "D2") (pintype "input"))
      (node (ref "U1") (pin "Q5") (pinfunction "Idler_HeaterLabelRight_ring_1_v_E20_Q5") (pintype "input"))
      (node (ref "U2") (pin "209") (pinfunction "H_2__15_209") (pintype "passive"))
      (node (ref "U4") (pin "S11") (pinfunction "AnalogLinks_s_enable_bottom_S11") (pintype "input"))
      (node (ref "U5") (pin "U1") (pinfunction "s_in_2_U1") (pintype "input"))
    )
    (net (code "150") (name "/sig_D3") (class "Default")
      (node (ref "J1") (pin "D3") (pintype "input"))
      (node (ref "U1") (pin "P1") (pinfunction "Signal_HeaterLabelRight_ring_2_v_E30_P1") (pintype "input"))
      (node (ref "U2") (pin "224") (pinfunction "H_1__16_224") (pintype "passive"))
    )
    (net (code "151") (name "/sig_D17") (class "Default")
      (node (ref "J1") (pin "D17") (pintype "input"))
      (node (ref "U1") (pin "G3") (pinfunction "Signal_PD_anode_1_1_sig_fil_test_G3") (pintype "input"))
      (node (ref "U2") (pin "320") (pinfunction "IBIAS_0__23_320") (pintype "passive"))
      (node (ref "U3") (pin "U8") (pinfunction "s_clk_p_U8") (pintype "input"))
    )
    (net (code "152") (name "/sig_D18") (class "Default")
      (node (ref "J1") (pin "D18") (pintype "input"))
      (node (ref "U1") (pin "F2") (pinfunction "Signal_HeaterLabelLeft_ring_2_0_fil_test_F2") (pintype "input"))
      (node (ref "U2") (pin "324") (pinfunction "H_1__23_324") (pintype "passive"))
      (node (ref "U3") (pin "U11") (pinfunction "s_enable_U11") (pintype "input"))
      (node (ref "U4") (pin "C1") (pinfunction "AnalogLinks_Rx_15_P_C1") (pintype "input"))
    )
    (net (code "153") (name "/sig_D19") (class "Default")
      (node (ref "J1") (pin "D19") (pintype "input"))
      (node (ref "U1") (pin "B3") (pinfunction "Source_PD_Anode_1_src_test_B3") (pintype "input"))
      (node (ref "U2") (pin "323") (pinfunction "IBIAS_3__23_323") (pintype "passive"))
      (node (ref "U4") (pin "D1") (pinfunction "AnalogLinks_Rx_15_N_D1") (pintype "input"))
    )
    (net (code "154") (name "/sig_E1") (class "Default")
      (node (ref "J1") (pin "E1") (pintype "input"))
      (node (ref "U1") (pin "Q1") (pinfunction "Signal_HeaterLabelRight_ring_1_v_E30_Q1") (pintype "input"))
      (node (ref "U2") (pin "193") (pinfunction "IBIAS_2__14_193") (pintype "passive"))
    )
    (net (code "155") (name "/sig_E2") (class "Default")
      (node (ref "J1") (pin "E2") (pintype "input"))
      (node (ref "U1") (pin "Q2") (pinfunction "ASE_anode_0_v_E30_Q2") (pintype "input"))
      (node (ref "U2") (pin "225") (pinfunction "H_2__16_225") (pintype "passive"))
    )
    (net (code "156") (name "/sig_E3") (class "Default")
      (node (ref "J1") (pin "E3") (pintype "input"))
      (node (ref "U1") (pin "Q3") (pinfunction "idler_PD_anode_0_v_E30_Q3") (pintype "input"))
      (node (ref "U2") (pin "220") (pinfunction "IBIAS_0__16_220") (pintype "passive"))
    )
    (net (code "157") (name "/sig_E17") (class "Default")
      (node (ref "J1") (pin "E17") (pintype "input"))
      (node (ref "U1") (pin "D2") (pinfunction "Signal_HeaterLabelLeft_ring_0_0_fil_test_D2") (pintype "input"))
      (node (ref "U2") (pin "338") (pinfunction "IBIAS_2__24_338") (pintype "passive"))
      (node (ref "U3") (pin "U2") (pinfunction "s_out_U2") (pintype "input"))
    )
    (net (code "158") (name "/sig_E18") (class "Default")
      (node (ref "J1") (pin "E18") (pintype "input"))
      (node (ref "U1") (pin "D3") (pinfunction "ASE_anode_0_6_comb_test_D3") (pintype "input"))
      (node (ref "U2") (pin "336") (pinfunction "IBIAS_0__24_336") (pintype "passive"))
      (node (ref "U3") (pin "U4") (pinfunction "s_reset_U4") (pintype "input"))
    )
    (net (code "159") (name "/sig_E19") (class "Default")
      (node (ref "J1") (pin "E19") (pintype "input"))
      (node (ref "U1") (pin "B4") (pinfunction "sig_idler__PD_cathods__combtest__cathodesrctest_B4") (pintype "input"))
      (node (ref "U2") (pin "340") (pinfunction "H_1__24_340") (pintype "passive"))
    )
    (net (code "160") (name "/sig_F1") (class "Default")
      (node (ref "J1") (pin "F1") (pintype "input"))
      (node (ref "U1") (pin "R2") (pinfunction "Pulse_curver_PD_anode_v_E30_R2") (pintype "input"))
      (node (ref "U2") (pin "197") (pinfunction "H_3__14_197") (pintype "passive"))
    )
    (net (code "161") (name "/sig_F2") (class "Default")
      (node (ref "J1") (pin "F2") (pintype "input"))
      (node (ref "U1") (pin "R3") (pinfunction "signal_PD_anode_0_v_E30_R3") (pintype "input"))
      (node (ref "U2") (pin "195") (pinfunction "H_1__14_195") (pintype "passive"))
    )
    (net (code "162") (name "/sig_F3") (class "Default")
      (node (ref "J1") (pin "F3") (pintype "input"))
      (node (ref "U1") (pin "R4") (pinfunction "ASE_HeaterLabelRight_ring_1_v_E20_R4") (pintype "input"))
      (node (ref "U2") (pin "191") (pinfunction "IBIAS_0__14_191") (pintype "passive"))
      (node (ref "U6") (pin "E11") (pinfunction "pad_equip_reset_E11") (pintype "passive"))
    )
    (net (code "163") (name "/sig_F17") (class "Default")
      (node (ref "J1") (pin "F17") (pintype "input"))
      (node (ref "U1") (pin "D1") (pinfunction "ASE_HeaterLabelLeft_ring_0_comb_6_fil_test_D1") (pintype "input"))
      (node (ref "U2") (pin "339") (pinfunction "IBIAS_3__24_339") (pintype "passive"))
      (node (ref "U3") (pin "A3") (pinfunction "TIE_HI_A3") (pintype "input"))
    )
    (net (code "164") (name "/sig_F18") (class "Default")
      (node (ref "J1") (pin "F18") (pintype "input"))
      (node (ref "U1") (pin "D4") (pinfunction "SPS_heater_GND_0_v_E26_D4") (pintype "input"))
      (node (ref "U2") (pin "337") (pinfunction "IBIAS_1__24_337") (pintype "passive"))
      (node (ref "U3") (pin "U3") (pinfunction "s_in_U3") (pintype "input"))
    )
    (net (code "165") (name "/sig_F19") (class "Default")
      (node (ref "J1") (pin "F19") (pintype "input"))
      (node (ref "U1") (pin "B5") (pinfunction "ASE_cathode_0_4__7__E44__4_wires_B5") (pintype "input"))
      (node (ref "U2") (pin "341") (pinfunction "H_2__24_341") (pintype "passive"))
      (node (ref "U3") (pin "U10") (pinfunction "s_update_U10") (pintype "input"))
    )
    (net (code "166") (name "/sig_G1") (class "Default")
      (node (ref "J1") (pin "G1") (pintype "input"))
      (node (ref "U1") (pin "R1") (pinfunction "Signal_HeaterLabelRight_ring_0_v_E30_R1") (pintype "input"))
      (node (ref "U2") (pin "176") (pinfunction "IBIAS_1__13_176") (pintype "passive"))
      (node (ref "U6") (pin "D11") (pinfunction "pad_rx_reset_D11") (pintype "passive"))
    )
    (net (code "167") (name "/sig_G2") (class "Default")
      (node (ref "J1") (pin "G2") (pintype "input"))
      (node (ref "U1") (pin "S3") (pinfunction "signal_PD_anode_1_v_E30_S3") (pintype "input"))
      (node (ref "U2") (pin "175") (pinfunction "IBIAS_0__13_175") (pintype "passive"))
      (node (ref "U6") (pin "G10") (pinfunction "pad_s_clk_n_G10") (pintype "passive"))
    )
    (net (code "168") (name "/sig_G3") (class "Default")
      (node (ref "J1") (pin "G3") (pintype "input"))
      (node (ref "U1") (pin "S1") (pinfunction "ASE_HeaterLabelRight_ring_1_v_E30_S1") (pintype "input"))
      (node (ref "U2") (pin "194") (pinfunction "IBIAS_3__14_194") (pintype "passive"))
      (node (ref "U6") (pin "G9") (pinfunction "TESTVD_G9") (pintype "passive"))
    )
    (net (code "169") (name "/sig_G17") (class "Default")
      (node (ref "J1") (pin "G17") (pintype "input"))
      (node (ref "U1") (pin "D5") (pinfunction "Idler_HeaterLabelRight_ring_3_v_E26_D5") (pintype "input"))
      (node (ref "U2") (pin "342") (pinfunction "H_3__24_342") (pintype "passive"))
      (node (ref "U3") (pin "A5") (pinfunction "TIE_LO_A5") (pintype "input"))
    )
    (net (code "170") (name "/sig_G18") (class "Default")
      (node (ref "J1") (pin "G18") (pintype "input"))
      (node (ref "U1") (pin "A3") (pinfunction "Source_PD_Anode_5_src_test_A3") (pintype "input"))
      (node (ref "U2") (pin "304") (pinfunction "BIAS_1__21_22_304") (pintype "passive"))
      (node (ref "U2") (pin "333") (pinfunction "BIAS_1__23_24_333") (pintype "passive"))
      (node (ref "U3") (pin "U1") (pinfunction "reset_U1") (pintype "input"))
    )
    (net (code "171") (name "/sig_G19") (class "Default")
      (node (ref "J1") (pin "G19") (pintype "input"))
      (node (ref "U1") (pin "A4") (pinfunction "ASE_anode_0_7_A4") (pintype "input"))
      (node (ref "U2") (pin "305") (pinfunction "BIAS_2__21_22_305") (pintype "passive"))
      (node (ref "U2") (pin "334") (pinfunction "BIAS_2__23_24_334") (pintype "passive"))
      (node (ref "U3") (pin "U9") (pinfunction "s_clk_n_U9") (pintype "input"))
    )
    (net (code "172") (name "/sig_H1") (class "Default")
      (node (ref "J1") (pin "H1") (pintype "input"))
      (node (ref "U1") (pin "S4") (pinfunction "ASE_HeaterLabelRight_ring_0_v_E20_S4") (pintype "input"))
      (node (ref "U2") (pin "179") (pinfunction "H_1__13_179") (pintype "passive"))
      (node (ref "U6") (pin "E10") (pinfunction "pad_TIE_LO_E10") (pintype "passive"))
    )
    (net (code "173") (name "/sig_H2") (class "Default")
      (node (ref "J1") (pin "H2") (pintype "input"))
      (node (ref "U1") (pin "T3") (pinfunction "signal_PD_anode_2_v_E30_T3") (pintype "input"))
      (node (ref "U2") (pin "178") (pinfunction "IBIAS_3__13_178") (pintype "passive"))
      (node (ref "U6") (pin "G8") (pinfunction "TESTVG_G8") (pintype "passive"))
    )
    (net (code "174") (name "/sig_H3") (class "Default")
      (node (ref "J1") (pin "H3") (pintype "input"))
      (node (ref "U1") (pin "T1") (pinfunction "ASE_HeaterLabelRight_ring_0_v_E30_T1") (pintype "input"))
      (node (ref "U2") (pin "177") (pinfunction "IBIAS_2__13_177") (pintype "passive"))
      (node (ref "U6") (pin "G11") (pinfunction "pad_s_clk_p_G11") (pintype "passive"))
    )
    (net (code "175") (name "/sig_H17") (class "Default")
      (node (ref "J1") (pin "H17") (pintype "input"))
      (node (ref "U1") (pin "A1") (pinfunction "SPS_heater_VDD_0_5_src_test_v1_A1") (pintype "input"))
      (node (ref "U2") (pin "306") (pinfunction "BIAS_3__21_22_306") (pintype "passive"))
      (node (ref "U2") (pin "335") (pinfunction "BIAS_3__23_24_335") (pintype "passive"))
    )
    (net (code "176") (name "/sig_J1") (class "Default")
      (node (ref "J1") (pin "J1") (pintype "input"))
      (node (ref "U1") (pin "U4") (pinfunction "all_cathods_v_E30__shared_ground_U4") (pintype "input"))
      (node (ref "U2") (pin "246") (pinfunction "BIAS_1__17_18_246") (pintype "passive"))
      (node (ref "U2") (pin "275") (pinfunction "BIAS_1__19_20_275") (pintype "passive"))
      (node (ref "U6") (pin "D10") (pinfunction "pad_TIE_HI_D10") (pintype "passive"))
    )
    (net (code "177") (name "/sig_J2") (class "Default")
      (node (ref "J1") (pin "J2") (pintype "input"))
      (node (ref "U1") (pin "U1") (pinfunction "PulseCurver_heater_VDD_v_E30_U1") (pintype "input"))
      (node (ref "U2") (pin "181") (pinfunction "H_3__13_181") (pintype "passive"))
      (node (ref "U6") (pin "A11") (pinfunction "pad_s_in_A11") (pintype "passive"))
    )
    (net (code "178") (name "/sig_J3") (class "Default")
      (node (ref "J1") (pin "J3") (pintype "input"))
      (node (ref "U1") (pin "U3") (pinfunction "signal_PD_anode_3_v_E30_U3") (pintype "input"))
      (node (ref "U2") (pin "180") (pinfunction "H_2__13_180") (pintype "passive"))
      (node (ref "U6") (pin "B11") (pinfunction "pad_s_enable_rx_B11") (pintype "passive"))
    )
    (net (code "179") (name "/sig_J17") (class "Default")
      (node (ref "J1") (pin "J17") (pintype "input"))
      (node (ref "U1") (pin "A5") (pinfunction "ASE_anode_0_6_E44_A5") (pintype "input"))
      (node (ref "U2") (pin "298") (pinfunction "BIAS_4__21_298") (pintype "passive"))
      (node (ref "U2") (pin "314") (pinfunction "BIAS_4__22_314") (pintype "passive"))
      (node (ref "U2") (pin "327") (pinfunction "BIAS_4__23_327") (pintype "passive"))
      (node (ref "U2") (pin "343") (pinfunction "BIAS_4__24_343") (pintype "passive"))
      (node (ref "U2") (pin "365") (pinfunction "NC__C_16_365") (pintype "passive"))
      (node (ref "U2") (pin "53") (pinfunction "BIAS_4__4_53") (pintype "passive"))
      (node (ref "U4") (pin "H11") (pinfunction "AnalogLinks_Rx_5_N_H11") (pintype "input"))
    )
    (net (code "180") (name "/sig_K1") (class "Default")
      (node (ref "J1") (pin "K1") (pintype "input"))
      (node (ref "U1") (pin "T4") (pinfunction "PulseCurver_heater_VDD_v_E20_T4") (pintype "input"))
      (node (ref "U2") (pin "248") (pinfunction "BIAS_3__17_18_248") (pintype "passive"))
      (node (ref "U2") (pin "277") (pinfunction "BIAS_3__19_20_277") (pintype "passive"))
      (node (ref "U6") (pin "F9") (pinfunction "VPD_F9") (pintype "passive"))
    )
    (net (code "181") (name "/sig_K2") (class "Default")
      (node (ref "J1") (pin "K2") (pintype "input"))
      (node (ref "U2") (pin "247") (pinfunction "BIAS_2__17_18_247") (pintype "passive"))
      (node (ref "U2") (pin "276") (pinfunction "BIAS_2__19_20_276") (pintype "passive"))
      (node (ref "U6") (pin "A10") (pinfunction "pad_s_reset_A10") (pintype "passive"))
    )
    (net (code "182") (name "/sig_K3") (class "Default")
      (node (ref "J1") (pin "K3") (pintype "input"))
      (node (ref "U1") (pin "M6") (pinfunction "signal_PD_anode_0_v_E20_M6") (pintype "input"))
      (node (ref "U2") (pin "198") (pinfunction "BIAS_4__14_198") (pintype "passive"))
      (node (ref "U2") (pin "227") (pinfunction "BIAS_4__16_227") (pintype "passive"))
      (node (ref "U2") (pin "24") (pinfunction "BIAS_4__2_24") (pintype "passive"))
      (node (ref "U2") (pin "240") (pinfunction "BIAS_4__17_240") (pintype "passive"))
      (node (ref "U2") (pin "256") (pinfunction "BIAS_4__18_256") (pintype "passive"))
      (node (ref "U2") (pin "269") (pinfunction "BIAS_4__19_269") (pintype "passive"))
      (node (ref "U2") (pin "285") (pinfunction "BIAS_4__20_285") (pintype "passive"))
      (node (ref "U2") (pin "352") (pinfunction "NC__C_3_352") (pintype "passive"))
      (node (ref "U2") (pin "353") (pinfunction "NC__C_4_353") (pintype "passive"))
      (node (ref "U2") (pin "356") (pinfunction "NC__C_7_356") (pintype "passive"))
      (node (ref "U2") (pin "359") (pinfunction "NC__C_10_359") (pintype "passive"))
      (node (ref "U6") (pin "C11") (pinfunction "pad_rx_reset_async_C11") (pintype "passive"))
    )
    (net (code "183") (name "/sig_K17") (class "Default")
      (node (ref "J1") (pin "K17") (pintype "input"))
      (node (ref "U1") (pin "A6") (pinfunction "ASE_anode_0_5_E44_A6") (pintype "input"))
      (node (ref "U2") (pin "124") (pinfunction "BIAS_4__9_124") (pintype "passive"))
      (node (ref "U2") (pin "140") (pinfunction "BIAS_4__10_140") (pintype "passive"))
      (node (ref "U2") (pin "153") (pinfunction "BIAS_4__11_153") (pintype "passive"))
      (node (ref "U2") (pin "169") (pinfunction "BIAS_4__12_169") (pintype "passive"))
      (node (ref "U2") (pin "37") (pinfunction "BIAS_4__3_37") (pintype "passive"))
      (node (ref "U4") (pin "G11") (pinfunction "AnalogLinks_Rx_5_P_G11") (pintype "input"))
    )
    (net (code "184") (name "/sig_L1") (class "Default")
      (node (ref "J1") (pin "L1") (pintype "input"))
      (node (ref "U1") (pin "O6") (pinfunction "idler_PD_anode_1_v_E20_O6") (pintype "input"))
      (node (ref "U2") (pin "101") (pinfunction "BIAS_1__7_8_101") (pintype "passive"))
      (node (ref "U2") (pin "14") (pinfunction "BIAS_1__1_2_14") (pintype "passive"))
      (node (ref "U2") (pin "188") (pinfunction "BIAS_1__13_14_188") (pintype "passive"))
      (node (ref "U2") (pin "217") (pinfunction "BIAS_1__15_16_217") (pintype "passive"))
      (node (ref "U2") (pin "72") (pinfunction "BIAS_1__5_6_72") (pintype "passive"))
      (node (ref "U6") (pin "A9") (pinfunction "pad_s_update_A9") (pintype "passive"))
    )
    (net (code "185") (name "/sig_L2") (class "Default")
      (node (ref "J1") (pin "L2") (pintype "input"))
      (node (ref "U1") (pin "Q6") (pinfunction "idler_PD_anode_3_v_E20_Q6") (pintype "input"))
      (node (ref "U2") (pin "102") (pinfunction "BIAS_2__7_8_102") (pintype "passive"))
      (node (ref "U2") (pin "15") (pinfunction "BIAS_2__1_2_15") (pintype "passive"))
      (node (ref "U2") (pin "189") (pinfunction "BIAS_2__13_14_189") (pintype "passive"))
      (node (ref "U2") (pin "218") (pinfunction "BIAS_2__15_16_218") (pintype "passive"))
      (node (ref "U2") (pin "73") (pinfunction "BIAS_2__5_6_73") (pintype "passive"))
      (node (ref "U6") (pin "C8") (pinfunction "VREF0_C8") (pintype "passive"))
    )
    (net (code "186") (name "/sig_L3") (class "Default")
      (node (ref "J1") (pin "L3") (pintype "input"))
      (node (ref "U1") (pin "P6") (pinfunction "idler_PD_anode_2_v_E20_P6") (pintype "input"))
      (node (ref "U2") (pin "103") (pinfunction "BIAS_3__7_8_103") (pintype "passive"))
      (node (ref "U2") (pin "16") (pinfunction "BIAS_3__1_2_16") (pintype "passive"))
      (node (ref "U2") (pin "190") (pinfunction "BIAS_3__13_14_190") (pintype "passive"))
      (node (ref "U2") (pin "219") (pinfunction "BIAS_3__15_16_219") (pintype "passive"))
      (node (ref "U2") (pin "357") (pinfunction "NC__C_8_357") (pintype "passive"))
      (node (ref "U2") (pin "358") (pinfunction "NC__C_9_358") (pintype "passive"))
      (node (ref "U2") (pin "74") (pinfunction "BIAS_3__5_6_74") (pintype "passive"))
      (node (ref "U6") (pin "B10") (pinfunction "pad_s_enable_tx_B10") (pintype "passive"))
    )
    (net (code "187") (name "/sig_L16") (class "Default")
      (node (ref "J1") (pin "L16") (pintype "input"))
      (node (ref "U2") (pin "131") (pinfunction "BIAS_2__9_10_131") (pintype "passive"))
      (node (ref "U2") (pin "160") (pinfunction "BIAS_2__11_12_160") (pintype "passive"))
      (node (ref "U2") (pin "44") (pinfunction "BIAS_2__3_4_44") (pintype "passive"))
    )
    (net (code "188") (name "/sig_L17") (class "Default")
      (node (ref "J1") (pin "L17") (pintype "input"))
      (node (ref "U1") (pin "B6") (pinfunction "ASE_anode_0_4_E44_B6") (pintype "input"))
      (node (ref "U2") (pin "132") (pinfunction "BIAS_3__9_10_132") (pintype "passive"))
      (node (ref "U2") (pin "161") (pinfunction "BIAS_3__11_12_161") (pintype "passive"))
      (node (ref "U2") (pin "45") (pinfunction "BIAS_3__3_4_45") (pintype "passive"))
      (node (ref "U4") (pin "F10") (pinfunction "AnalogLinks_TxIn_6_N_F10") (pintype "input"))
    )
    (net (code "189") (name "/sig_M1") (class "Default")
      (node (ref "J1") (pin "M1") (pintype "input"))
      (node (ref "U1") (pin "T7") (pinfunction "debug_PD_anode_v_E20_T7") (pintype "input"))
      (node (ref "U2") (pin "111") (pinfunction "BIAS_4__8_111") (pintype "passive"))
      (node (ref "U2") (pin "182") (pinfunction "BIAS_4__13_182") (pintype "passive"))
      (node (ref "U2") (pin "211") (pinfunction "BIAS_4__15_211") (pintype "passive"))
      (node (ref "U2") (pin "66") (pinfunction "BIAS_4__5_66") (pintype "passive"))
      (node (ref "U2") (pin "8") (pinfunction "BIAS_4__1_8") (pintype "passive"))
      (node (ref "U2") (pin "82") (pinfunction "BIAS_4__6_82") (pintype "passive"))
      (node (ref "U2") (pin "95") (pinfunction "BIAS_4__7_95") (pintype "passive"))
      (node (ref "U6") (pin "A8") (pinfunction "IREF_A8") (pintype "passive"))
    )
    (net (code "190") (name "/sig_M2") (class "Default")
      (node (ref "J1") (pin "M2") (pintype "input"))
      (node (ref "U1") (pin "U7") (pinfunction "through_PD_anode_v_E20_U7") (pintype "input"))
      (node (ref "U2") (pin "7") (pinfunction "H_3__1_7") (pintype "passive"))
      (node (ref "U6") (pin "B7") (pinfunction "VTERM_B7") (pintype "passive"))
    )
    (net (code "191") (name "/sig_M3") (class "Default")
      (node (ref "J1") (pin "M3") (pintype "input"))
      (node (ref "U1") (pin "N6") (pinfunction "idler_PD_anode_0_v_E20_N6") (pintype "input"))
      (node (ref "U2") (pin "6") (pinfunction "H_2__1_6") (pintype "passive"))
      (node (ref "U6") (pin "B9") (pinfunction "pad_s_enable_equip_B9") (pintype "passive"))
    )
    (net (code "192") (name "/sig_M16") (class "Default")
      (node (ref "J1") (pin "M16") (pintype "input"))
      (node (ref "U2") (pin "130") (pinfunction "BIAS_1__9_10_130") (pintype "passive"))
      (node (ref "U2") (pin "159") (pinfunction "BIAS_1__11_12_159") (pintype "passive"))
      (node (ref "U2") (pin "43") (pinfunction "BIAS_1__3_4_43") (pintype "passive"))
    )
    (net (code "193") (name "/sig_M17") (class "Default")
      (node (ref "J1") (pin "M17") (pintype "input"))
      (node (ref "U2") (pin "168") (pinfunction "H_3__12_168") (pintype "passive"))
      (node (ref "U4") (pin "E10") (pinfunction "AnalogLinks_TxIn_6_P_E10") (pintype "input"))
    )
    (net (code "194") (name "/sig_N1") (class "Default")
      (node (ref "J1") (pin "N1") (pintype "input"))
      (node (ref "U1") (pin "S8") (pinfunction "ASE_HeaterLabelRight_ring_0_v_E5_S8") (pintype "input"))
      (node (ref "U2") (pin "5") (pinfunction "H_1__1_5") (pintype "passive"))
    )
    (net (code "195") (name "/sig_N2") (class "Default")
      (node (ref "J1") (pin "N2") (pintype "input"))
      (node (ref "U1") (pin "T8") (pinfunction "PulseCurver_heater_GND_v_E5_T8") (pintype "input"))
      (node (ref "U2") (pin "4") (pinfunction "IBIAS_3__1_4") (pintype "passive"))
      (node (ref "U5") (pin "A1") (pinfunction "TIE_HI_A1") (pintype "input"))
    )
    (net (code "196") (name "/sig_N3") (class "Default")
      (node (ref "J1") (pin "N3") (pintype "input"))
      (node (ref "U1") (pin "S7") (pinfunction "ASE_anode_1_v_E20_S7") (pintype "input"))
      (node (ref "U2") (pin "3") (pinfunction "IBIAS_2__1_3") (pintype "passive"))
    )
    (net (code "197") (name "/sig_N16") (class "Default")
      (node (ref "J1") (pin "N16") (pintype "input"))
      (node (ref "U2") (pin "403") (pinfunction "IBIAS_3__DEEMB_403") (pintype "passive"))
    )
    (net (code "198") (name "/sig_N17") (class "Default")
      (node (ref "J1") (pin "N17") (pintype "input"))
      (node (ref "U1") (pin "F7") (pinfunction "all_cathods_v_E26_F7") (pintype "input"))
      (node (ref "U2") (pin "166") (pinfunction "H_1__12_166") (pintype "passive"))
    )
    (net (code "199") (name "/sig_N18") (class "Default")
      (node (ref "J1") (pin "N18") (pintype "input"))
      (node (ref "U1") (pin "D7") (pinfunction "Source_PD_Anode_v_E26_D7") (pintype "input"))
      (node (ref "U2") (pin "167") (pinfunction "H_2__12_167") (pintype "passive"))
      (node (ref "U4") (pin "B9") (pinfunction "S_OUT_1_B9") (pintype "input"))
    )
    (net (code "200") (name "/sig_N19") (class "Default")
      (node (ref "J1") (pin "N19") (pintype "input"))
      (node (ref "U1") (pin "G6") (pinfunction "idler_PD_anode_1_v_E26_G6") (pintype "input"))
      (node (ref "U2") (pin "162") (pinfunction "IBIAS_0__12_162") (pintype "passive"))
      (node (ref "U4") (pin "A3") (pinfunction "TIE_HI_A3") (pintype "input"))
    )
    (net (code "201") (name "/sig_P1") (class "Default")
      (node (ref "J1") (pin "P1") (pintype "input"))
      (node (ref "U1") (pin "Q7") (pinfunction "Pulse_curver_PD_anode_v_E20_Q7") (pintype "input"))
      (node (ref "U2") (pin "2") (pinfunction "IBIAS_1__1_2") (pintype "passive"))
    )
    (net (code "202") (name "/sig_P2") (class "Default")
      (node (ref "J1") (pin "P2") (pintype "input"))
      (node (ref "U1") (pin "R8") (pinfunction "ASE_HeaterLabelRight_ring_1_v_E5_R8") (pintype "input"))
      (node (ref "U2") (pin "1") (pinfunction "IBIAS_0__1_1") (pintype "passive"))
      (node (ref "U5") (pin "A2") (pinfunction "TIE_LO_A2") (pintype "input"))
    )
    (net (code "203") (name "/sig_P3") (class "Default")
      (node (ref "J1") (pin "P3") (pintype "input"))
      (node (ref "U1") (pin "R7") (pinfunction "ASE_anode_0_v_E20_R7") (pintype "input"))
      (node (ref "U2") (pin "23") (pinfunction "H_3__2_23") (pintype "passive"))
    )
    (net (code "204") (name "/sig_P16") (class "Default")
      (node (ref "J1") (pin "P16") (pintype "input"))
      (node (ref "U2") (pin "402") (pinfunction "IBIAS_2__DEEMB_402") (pintype "passive"))
    )
    (net (code "205") (name "/sig_P17") (class "Default")
      (node (ref "J1") (pin "P17") (pintype "input"))
      (node (ref "U1") (pin "G8") (pinfunction "Signal_HeaterLabelRight_ring_0_v_E12_G8") (pintype "input"))
      (node (ref "U2") (pin "165") (pinfunction "IBIAS_3__12_165") (pintype "passive"))
    )
    (net (code "206") (name "/sig_P18") (class "Default")
      (node (ref "J1") (pin "P18") (pintype "input"))
      (node (ref "U1") (pin "C8") (pinfunction "Idler_HeaterLabelRight_ring_0_v_E12_C8") (pintype "input"))
      (node (ref "U2") (pin "164") (pinfunction "IBIAS_2__12_164") (pintype "passive"))
      (node (ref "U4") (pin "B8") (pinfunction "s_clk_n_B8") (pintype "input"))
    )
    (net (code "207") (name "/sig_P19") (class "Default")
      (node (ref "J1") (pin "P19") (pintype "input"))
      (node (ref "U1") (pin "D6") (pinfunction "signal_PD_anode_1_v_E26_D6") (pintype "input"))
      (node (ref "U2") (pin "163") (pinfunction "IBIAS_1__12_163") (pintype "passive"))
      (node (ref "U4") (pin "B4") (pinfunction "s_in_1_B4") (pintype "input"))
    )
    (net (code "208") (name "/sig_R1") (class "Default")
      (node (ref "J1") (pin "R1") (pintype "input"))
      (node (ref "U1") (pin "Q9") (pinfunction "Idler_HeaterLabelRight_ring_1_v_E5_Q9") (pintype "input"))
      (node (ref "U2") (pin "22") (pinfunction "H_2__2_22") (pintype "passive"))
      (node (ref "U5") (pin "U4") (pinfunction "s_clk_p_U4") (pintype "input"))
    )
    (net (code "209") (name "/sig_R2") (class "Default")
      (node (ref "J1") (pin "R2") (pintype "input"))
      (node (ref "U1") (pin "P7") (pinfunction "input_PD_anode_v_E20_P7") (pintype "input"))
      (node (ref "U2") (pin "21") (pinfunction "H_1__2_21") (pintype "passive"))
      (node (ref "U5") (pin "A3") (pinfunction "Reset_A3") (pintype "input"))
    )
    (net (code "210") (name "/sig_R3") (class "Default")
      (node (ref "J1") (pin "R3") (pintype "input"))
      (node (ref "U1") (pin "Q8") (pinfunction "Signal_HeaterLabelRight_ring_0_v_E5_Q8") (pintype "input"))
      (node (ref "U2") (pin "20") (pinfunction "IBIAS_3__2_20") (pintype "passive"))
    )
    (net (code "211") (name "/sig_R15") (class "Default")
      (node (ref "J1") (pin "R15") (pintype "input"))
      (node (ref "U2") (pin "400") (pinfunction "IBIAS_0__DEEMB_400") (pintype "passive"))
    )
    (net (code "212") (name "/sig_R16") (class "Default")
      (node (ref "J1") (pin "R16") (pintype "input"))
      (node (ref "U2") (pin "401") (pinfunction "IBIAS_1__DEEMB_401") (pintype "passive"))
    )
    (net (code "213") (name "/sig_R17") (class "Default")
      (node (ref "J1") (pin "R17") (pintype "input"))
      (node (ref "U1") (pin "G7") (pinfunction "Pulse_curver_PD_anode_v_E26_G7") (pintype "input"))
      (node (ref "U2") (pin "148") (pinfunction "IBIAS_2__11_148") (pintype "passive"))
    )
    (net (code "214") (name "/sig_R18") (class "Default")
      (node (ref "J1") (pin "R18") (pintype "input"))
      (node (ref "U1") (pin "D8") (pinfunction "Signal_HeaterLabelLeft_ring_3_v_E12_D8") (pintype "input"))
      (node (ref "U2") (pin "152") (pinfunction "H_3__11_152") (pintype "passive"))
      (node (ref "U4") (pin "A8") (pinfunction "s_clk_p_A8") (pintype "input"))
    )
    (net (code "215") (name "/sig_R19") (class "Default")
      (node (ref "J1") (pin "R19") (pintype "input"))
      (node (ref "U1") (pin "E6") (pinfunction "signal_PD_anode_0_v_E26_E6") (pintype "input"))
      (node (ref "U2") (pin "149") (pinfunction "IBIAS_3__11_149") (pintype "passive"))
      (node (ref "U4") (pin "A4") (pinfunction "TIE_LO_A4") (pintype "input"))
    )
    (net (code "216") (name "/sig_T1") (class "Default")
      (node (ref "J1") (pin "T1") (pintype "input"))
      (node (ref "U1") (pin "P8") (pinfunction "Signal_HeaterLabelRight_ring_1_v_E5_P8") (pintype "input"))
      (node (ref "U2") (pin "19") (pinfunction "IBIAS_2__2_19") (pintype "passive"))
      (node (ref "U5") (pin "T9") (pinfunction "s_enable_3_T9") (pintype "input"))
      (node (ref "U6") (pin "D2") (pinfunction "ibias_rx_2_D2") (pintype "passive"))
    )
    (net (code "217") (name "/sig_T2") (class "Default")
      (node (ref "J1") (pin "T2") (pintype "input"))
      (node (ref "U1") (pin "Q10") (pinfunction "idler_PD_anode_3_v_E5_Q10") (pintype "input"))
      (node (ref "U2") (pin "18") (pinfunction "IBIAS_1__2_18") (pintype "passive"))
      (node (ref "U5") (pin "U10") (pinfunction "s_in_4_U10") (pintype "input"))
      (node (ref "U6") (pin "C4") (pinfunction "PD_BIAS_N_C4") (pintype "passive"))
    )
    (net (code "218") (name "/sig_T3") (class "Default")
      (node (ref "J1") (pin "T3") (pintype "input"))
      (node (ref "U1") (pin "U11") (pinfunction "through_PD_anode_v_E5_U11") (pintype "input"))
      (node (ref "U2") (pin "17") (pinfunction "IBIAS_0__2_17") (pintype "passive"))
    )
    (net (code "219") (name "/sig_T17") (class "Default")
      (node (ref "J1") (pin "T17") (pintype "input"))
      (node (ref "U1") (pin "H8") (pinfunction "SPS_heater_VDD_0_v_E12_H8") (pintype "input"))
      (node (ref "U2") (pin "150") (pinfunction "H_1__11_150") (pintype "passive"))
    )
    (net (code "220") (name "/sig_T18") (class "Default")
      (node (ref "J1") (pin "T18") (pintype "input"))
      (node (ref "U1") (pin "E7") (pinfunction "input_PD_anode_v_E26_E7") (pintype "input"))
      (node (ref "U2") (pin "147") (pinfunction "IBIAS_1__11_147") (pintype "passive"))
      (node (ref "U4") (pin "B7") (pinfunction "S_ENABLE_1_B7") (pintype "input"))
    )
    (net (code "221") (name "/sig_T19") (class "Default")
      (node (ref "J1") (pin "T19") (pintype "input"))
      (node (ref "U1") (pin "B7") (pinfunction "signal_PD_anode_3_v_E26_B7") (pintype "input"))
      (node (ref "U2") (pin "151") (pinfunction "H_2__11_151") (pintype "passive"))
      (node (ref "U4") (pin "B5") (pinfunction "s_update_B5") (pintype "input"))
    )
    (net (code "222") (name "/sig_U1") (class "Default")
      (node (ref "J1") (pin "U1") (pintype "input"))
      (node (ref "U1") (pin "I6") (pinfunction "idler_PD_anode_3_v_E26_I6") (pintype "input"))
      (node (ref "U2") (pin "36") (pinfunction "H_3__3_36") (pintype "passive"))
      (node (ref "U5") (pin "U9") (pinfunction "s_enable_4_U9") (pintype "input"))
      (node (ref "U6") (pin "D5") (pinfunction "PD_BIAS_P_D5") (pintype "passive"))
    )
    (net (code "223") (name "/sig_U2") (class "Default")
      (node (ref "J1") (pin "U2") (pintype "input"))
      (node (ref "U1") (pin "L6") (pinfunction "signal_PD_anode_1_v_E20_L6") (pintype "input"))
      (node (ref "U2") (pin "30") (pinfunction "IBIAS_0__3_30") (pintype "passive"))
      (node (ref "U5") (pin "U11") (pinfunction "s_out_4_U11") (pintype "input"))
      (node (ref "U6") (pin "B1") (pinfunction "hs_clk_ibias_B1") (pintype "passive"))
    )
    (net (code "224") (name "/sig_U3") (class "Default")
      (node (ref "J1") (pin "U3") (pintype "input"))
      (node (ref "U1") (pin "H6") (pinfunction "idler_PD_anode_2_v_E26_H6") (pintype "input"))
      (node (ref "U2") (pin "33") (pinfunction "IBIAS_3__3_33") (pintype "passive"))
    )
    (net (code "225") (name "/sig_U4") (class "Default")
      (node (ref "J1") (pin "U4") (pintype "input"))
      (node (ref "U1") (pin "O7") (pinfunction "Source_PD_Anode_v_E20_O7") (pintype "input"))
      (node (ref "U2") (pin "48") (pinfunction "IBIAS_2__4_48") (pintype "passive"))
    )
    (net (code "226") (name "/sig_U5") (class "Default")
      (node (ref "J1") (pin "U5") (pintype "input"))
      (node (ref "U1") (pin "N7") (pinfunction "all_cathods_v_E20__shared_ground_N7") (pintype "input"))
      (node (ref "U2") (pin "50") (pinfunction "H_1__4_50") (pintype "passive"))
    )
    (net (code "227") (name "/sig_U6") (class "Default")
      (node (ref "J1") (pin "U6") (pintype "input"))
      (node (ref "U1") (pin "M7") (pinfunction "signal_PD_anode_2_v_E20_M7") (pintype "input"))
      (node (ref "U2") (pin "63") (pinfunction "H_1__5_63") (pintype "passive"))
    )
    (net (code "228") (name "/sig_U7") (class "Default")
      (node (ref "J1") (pin "U7") (pintype "input"))
      (node (ref "U1") (pin "M8") (pinfunction "SPS_heater_GND_0_v_E5_M8") (pintype "input"))
      (node (ref "U2") (pin "62") (pinfunction "IBIAS_3__5_62") (pintype "passive"))
    )
    (net (code "229") (name "/sig_U8") (class "Default")
      (node (ref "J1") (pin "U8") (pintype "input"))
      (node (ref "U1") (pin "L7") (pinfunction "signal_PD_anode_3_v_E20_L7") (pintype "input"))
      (node (ref "U2") (pin "77") (pinfunction "IBIAS_2__6_77") (pintype "passive"))
    )
    (net (code "230") (name "/sig_U9") (class "Default")
      (node (ref "J1") (pin "U9") (pintype "input"))
      (node (ref "U1") (pin "L8") (pinfunction "Idler_HeaterLabelRight_ring_0_v_E5_L8") (pintype "input"))
      (node (ref "U2") (pin "79") (pinfunction "H_1__6_79") (pintype "passive"))
    )
    (net (code "231") (name "/sig_U10") (class "Default")
      (node (ref "J1") (pin "U10") (pintype "input"))
      (node (ref "U1") (pin "K7") (pinfunction "through_PD_anode_v_E26_K7") (pintype "input"))
      (node (ref "U2") (pin "92") (pinfunction "H_1__7_92") (pintype "passive"))
    )
    (net (code "232") (name "/sig_U11") (class "Default")
      (node (ref "J1") (pin "U11") (pintype "input"))
      (node (ref "U1") (pin "P11") (pinfunction "input_PD_anode_v_E5_P11") (pintype "input"))
      (node (ref "U2") (pin "90") (pinfunction "IBIAS_2__7_90") (pintype "passive"))
    )
    (net (code "233") (name "/sig_U12") (class "Default")
      (node (ref "J1") (pin "U12") (pintype "input"))
      (node (ref "U1") (pin "O8") (pinfunction "Signal_HeaterLabelRight_ring_2_v_E5_O8") (pintype "input"))
      (node (ref "U2") (pin "107") (pinfunction "IBIAS_3__8_107") (pintype "passive"))
    )
    (net (code "234") (name "/sig_U13") (class "Default")
      (node (ref "J1") (pin "U13") (pintype "input"))
      (node (ref "U1") (pin "M10") (pinfunction "signal_PD_anode_0_v_E5_M10") (pintype "input"))
      (node (ref "U2") (pin "109") (pinfunction "H_2__8_109") (pintype "passive"))
    )
    (net (code "235") (name "/sig_U14") (class "Default")
      (node (ref "J1") (pin "U14") (pintype "input"))
      (node (ref "U1") (pin "J11") (pinfunction "Source_PD_Anode_v_E12_J11") (pintype "input"))
      (node (ref "U2") (pin "104") (pinfunction "IBIAS_0__8_104") (pintype "passive"))
    )
    (net (code "236") (name "/sig_U15") (class "Default")
      (node (ref "J1") (pin "U15") (pintype "input"))
      (node (ref "U1") (pin "G10") (pinfunction "idler_PD_anode_3_v_E12_G10") (pintype "input"))
      (node (ref "U2") (pin "118") (pinfunction "IBIAS_1__9_118") (pintype "passive"))
    )
    (net (code "237") (name "/sig_U16") (class "Default")
      (node (ref "J1") (pin "U16") (pintype "input"))
      (node (ref "U1") (pin "C10") (pinfunction "signal_PD_anode_0_v_E12_C10") (pintype "input"))
      (node (ref "U2") (pin "123") (pinfunction "H_3__9_123") (pintype "passive"))
    )
    (net (code "238") (name "/sig_U17") (class "Default")
      (node (ref "J1") (pin "U17") (pintype "input"))
      (node (ref "U1") (pin "H7") (pinfunction "ASE_anode_0_v_E26_H7") (pintype "input"))
      (node (ref "U2") (pin "137") (pinfunction "H_1__10_137") (pintype "passive"))
    )
    (net (code "239") (name "/sig_U18") (class "Default")
      (node (ref "J1") (pin "U18") (pintype "input"))
      (node (ref "U1") (pin "F6") (pinfunction "idler_PD_anode_0_v_E26_F6") (pintype "input"))
      (node (ref "U2") (pin "133") (pinfunction "IBIAS_0__10_133") (pintype "passive"))
      (node (ref "U4") (pin "A7") (pinfunction "s_reset_A7") (pintype "input"))
    )
    (net (code "240") (name "/sig_U19") (class "Default")
      (node (ref "J1") (pin "U19") (pintype "input"))
      (node (ref "U1") (pin "C7") (pinfunction "signal_PD_anode_2_v_E26_C7") (pintype "input"))
      (node (ref "U2") (pin "146") (pinfunction "IBIAS_0__11_146") (pintype "passive"))
      (node (ref "U4") (pin "B6") (pinfunction "reset_B6") (pintype "input"))
    )
    (net (code "241") (name "/sig_V1") (class "Default")
      (node (ref "J1") (pin "V1") (pintype "input"))
      (node (ref "U1") (pin "K8") (pinfunction "PulseCurver_heater_VDD_v_E12_K8") (pintype "input"))
      (node (ref "U2") (pin "35") (pinfunction "H_2__3_35") (pintype "passive"))
      (node (ref "U5") (pin "T8") (pinfunction "s_out_0_T8") (pintype "input"))
      (node (ref "U6") (pin "F5") (pinfunction "VREF2_F5") (pintype "passive"))
    )
    (net (code "242") (name "/sig_V2") (class "Default")
      (node (ref "J1") (pin "V2") (pintype "input"))
      (node (ref "U1") (pin "J7") (pinfunction "debug_PD_anode_v_E26_J7") (pintype "input"))
      (node (ref "U2") (pin "31") (pinfunction "IBIAS_1__3_31") (pintype "passive"))
      (node (ref "U5") (pin "S9") (pinfunction "s_in_3_S9") (pintype "input"))
      (node (ref "U6") (pin "B2") (pinfunction "MOD_HV_B2") (pintype "passive"))
    )
    (net (code "243") (name "/sig_V3") (class "Default")
      (node (ref "J1") (pin "V3") (pintype "input"))
      (node (ref "U1") (pin "J8") (pinfunction "ASE_HeaterLabelRight_ring_0_v_E12_J8") (pintype "input"))
      (node (ref "U2") (pin "49") (pinfunction "IBIAS_3__4_49") (pintype "passive"))
      (node (ref "U5") (pin "I9") (pinfunction "s_out_3_I9") (pintype "input"))
      (node (ref "U6") (pin "C2") (pinfunction "ibias_rx_1_C2") (pintype "passive"))
    )
    (net (code "244") (name "/sig_V4") (class "Default")
      (node (ref "J1") (pin "V4") (pintype "input"))
      (node (ref "U1") (pin "I7") (pinfunction "ASE_anode_1_v_E26_I7") (pintype "input"))
      (node (ref "U2") (pin "51") (pinfunction "H_2__4_51") (pintype "passive"))
      (node (ref "U5") (pin "A5") (pinfunction "s_enable_1_A5") (pintype "input"))
      (node (ref "U6") (pin "D3") (pinfunction "VREF1_D3") (pintype "passive"))
    )
    (net (code "245") (name "/sig_V5") (class "Default")
      (node (ref "J1") (pin "V5") (pintype "input"))
      (node (ref "U1") (pin "I8") (pinfunction "ASE_HeaterLabelRight_ring_1_v_E12_I8") (pintype "input"))
      (node (ref "U2") (pin "46") (pinfunction "IBIAS_0__4_46") (pintype "passive"))
      (node (ref "U5") (pin "B4") (pinfunction "s_reset_B4") (pintype "input"))
      (node (ref "U6") (pin "B3") (pinfunction "PS_HEAT_B3") (pintype "passive"))
    )
    (net (code "246") (name "/sig_V6") (class "Default")
      (node (ref "J1") (pin "V6") (pintype "input"))
      (node (ref "U1") (pin "T11") (pinfunction "debug_PD_anode_v_E5_T11") (pintype "input"))
      (node (ref "U2") (pin "60") (pinfunction "IBIAS_1__5_60") (pintype "passive"))
      (node (ref "U4") (pin "R10") (pinfunction "AnalogLinks_TxIn_0_N_R10") (pintype "input"))
    )
    (net (code "247") (name "/sig_V7") (class "Default")
      (node (ref "J1") (pin "V7") (pintype "input"))
      (node (ref "U1") (pin "S11") (pinfunction "ASE_anode_1_v_E5_S11") (pintype "input"))
      (node (ref "U2") (pin "65") (pinfunction "H_3__5_65") (pintype "passive"))
      (node (ref "U4") (pin "Q10") (pinfunction "AnalogLinks_TxIn_0_P_Q10") (pintype "input"))
    )
    (net (code "248") (name "/sig_V8") (class "Default")
      (node (ref "J1") (pin "V8") (pintype "input"))
      (node (ref "U1") (pin "R11") (pinfunction "ASE_anode_0_v_E5_R11") (pintype "input"))
      (node (ref "U2") (pin "81") (pinfunction "H_3__6_81") (pintype "passive"))
      (node (ref "U4") (pin "R11") (pinfunction "AnalogLinks_Rx_0_N_R11") (pintype "input"))
    )
    (net (code "249") (name "/sig_V9") (class "Default")
      (node (ref "J1") (pin "V9") (pintype "input"))
      (node (ref "U1") (pin "Q11") (pinfunction "ASE_anode_0_v_E5_Q11") (pintype "input"))
      (node (ref "U2") (pin "76") (pinfunction "IBIAS_1__6_76") (pintype "passive"))
      (node (ref "U4") (pin "Q11") (pinfunction "AnalogLinks_Rx_0_P_Q11") (pintype "input"))
    )
    (net (code "250") (name "/sig_V10") (class "Default")
      (node (ref "J1") (pin "V10") (pintype "input"))
      (node (ref "U1") (pin "P10") (pinfunction "idler_PD_anode_2_v_E5_P10") (pintype "input"))
      (node (ref "U2") (pin "88") (pinfunction "IBIAS_0__7_88") (pintype "passive"))
      (node (ref "U4") (pin "P10") (pinfunction "AnalogLinks_TxIn_1_N_P10") (pintype "input"))
    )
    (net (code "251") (name "/sig_V11") (class "Default")
      (node (ref "J1") (pin "V11") (pintype "input"))
      (node (ref "U1") (pin "O11") (pinfunction "Source_PD_Anode_v_E5_O11") (pintype "input"))
      (node (ref "U2") (pin "93") (pinfunction "H_2__7_93") (pintype "passive"))
      (node (ref "U4") (pin "O10") (pinfunction "AnalogLinks_TxIn_1_P_O10") (pintype "input"))
    )
    (net (code "252") (name "/sig_V12") (class "Default")
      (node (ref "J1") (pin "V12") (pintype "input"))
      (node (ref "U1") (pin "M11") (pinfunction "signal_PD_anode_2_v_E5_M11") (pintype "input"))
      (node (ref "U2") (pin "91") (pinfunction "IBIAS_3__7_91") (pintype "passive"))
      (node (ref "U4") (pin "P11") (pinfunction "AnalogLinks_Rx_1_N_P11") (pintype "input"))
    )
    (net (code "253") (name "/sig_V13") (class "Default")
      (node (ref "J1") (pin "V13") (pintype "input"))
      (node (ref "U1") (pin "L9") (pinfunction "Idler_HeaterLabelRight_ring_3_v_E5_L9") (pintype "input"))
      (node (ref "U2") (pin "106") (pinfunction "IBIAS_2__8_106") (pintype "passive"))
      (node (ref "U4") (pin "O11") (pinfunction "AnalogLinks_Rx_1_P_O11") (pintype "input"))
    )
    (net (code "254") (name "/sig_V14") (class "Default")
      (node (ref "J1") (pin "V14") (pintype "input"))
      (node (ref "U1") (pin "F11") (pinfunction "Pulse_curver_PD_anode_v_E12_F11") (pintype "input"))
      (node (ref "U2") (pin "108") (pinfunction "H_1__8_108") (pintype "passive"))
      (node (ref "U4") (pin "L11") (pinfunction "AnalogLinks_Rx_3_N_L11") (pintype "input"))
    )
    (net (code "255") (name "/sig_V15") (class "Default")
      (node (ref "J1") (pin "V15") (pintype "input"))
      (node (ref "U1") (pin "F10") (pinfunction "idler_PD_anode_2_v_E12_F10") (pintype "input"))
      (node (ref "U2") (pin "121") (pinfunction "H_1__9_121") (pintype "passive"))
      (node (ref "U4") (pin "K11") (pinfunction "AnalogLinks_Rx_3_P_K11") (pintype "input"))
    )
    (net (code "256") (name "/sig_V16") (class "Default")
      (node (ref "J1") (pin "V16") (pintype "input"))
      (node (ref "U1") (pin "C11") (pinfunction "signal_PD_anode_2_v_E12_C11") (pintype "input"))
      (node (ref "U2") (pin "119") (pinfunction "IBIAS_2__9_119") (pintype "passive"))
      (node (ref "U4") (pin "G10") (pinfunction "AnalogLinks_TxIn_5_P_G10") (pintype "input"))
    )
    (net (code "257") (name "/sig_V17") (class "Default")
      (node (ref "J1") (pin "V17") (pintype "input"))
      (node (ref "U1") (pin "C9") (pinfunction "Idler_HeaterLabelRight_ring_3_v_E12_C9") (pintype "input"))
      (node (ref "U2") (pin "135") (pinfunction "IBIAS_2__10_135") (pintype "passive"))
      (node (ref "U4") (pin "F11") (pinfunction "AnalogLinks_Rx_6_N_F11") (pintype "input"))
    )
    (net (code "258") (name "/sig_V18") (class "Default")
      (node (ref "J1") (pin "V18") (pintype "input"))
      (node (ref "U1") (pin "F8") (pinfunction "Signal_HeaterLabelRight_ring_1_v_E12_F8") (pintype "input"))
      (node (ref "U2") (pin "138") (pinfunction "H_2__10_138") (pintype "passive"))
      (node (ref "U4") (pin "C10") (pinfunction "AnalogLinks_TxIn_7_P_C10") (pintype "input"))
    )
    (net (code "259") (name "/sig_V19") (class "Default")
      (node (ref "J1") (pin "V19") (pintype "input"))
      (node (ref "U1") (pin "E8") (pinfunction "Signal_HeaterLabelRight_ring_2_v_E12_E8") (pintype "input"))
      (node (ref "U2") (pin "134") (pinfunction "IBIAS_1__10_134") (pintype "passive"))
      (node (ref "U4") (pin "C11") (pinfunction "AnalogLinks_Rx_7_P_C11") (pintype "input"))
    )
    (net (code "260") (name "/sig_W1") (class "Default")
      (node (ref "J1") (pin "W1") (pintype "input"))
      (node (ref "U1") (pin "O10") (pinfunction "idler_PD_anode_1_v_E5_O10") (pintype "input"))
      (node (ref "U2") (pin "34") (pinfunction "H_1__3_34") (pintype "passive"))
      (node (ref "U5") (pin "T6") (pinfunction "s_in_0_T6") (pintype "input"))
      (node (ref "U6") (pin "E2") (pinfunction "MOD_HEAT_E2") (pintype "passive"))
    )
    (net (code "261") (name "/sig_W2") (class "Default")
      (node (ref "J1") (pin "W2") (pintype "input"))
      (node (ref "U1") (pin "N11") (pinfunction "all_cathods_v_E5__shared_ground_N11") (pintype "input"))
      (node (ref "U2") (pin "32") (pinfunction "IBIAS_2__3_32") (pintype "passive"))
      (node (ref "U5") (pin "U6") (pinfunction "s_enable_0_U6") (pintype "input"))
      (node (ref "U6") (pin "E1") (pinfunction "pad_s_out_tx_E1") (pintype "passive"))
    )
    (net (code "262") (name "/sig_W3") (class "Default")
      (node (ref "J1") (pin "W3") (pintype "input"))
      (node (ref "U1") (pin "N10") (pinfunction "idler_PD_anode_0_v_E5_N10") (pintype "input"))
      (node (ref "U2") (pin "52") (pinfunction "H_3__4_52") (pintype "passive"))
      (node (ref "U5") (pin "T5") (pinfunction "s_update_T5") (pintype "input"))
      (node (ref "U6") (pin "F2") (pinfunction "pad_s_out_equip_F2") (pintype "passive"))
    )
    (net (code "263") (name "/sig_W4") (class "Default")
      (node (ref "J1") (pin "W4") (pintype "input"))
      (node (ref "U1") (pin "L11") (pinfunction "signal_PD_anode_3_v_E5_L11") (pintype "input"))
      (node (ref "U2") (pin "47") (pinfunction "IBIAS_1__4_47") (pintype "passive"))
      (node (ref "U5") (pin "U5") (pinfunction "s_clk_n_U5") (pintype "input"))
      (node (ref "U6") (pin "F1") (pinfunction "pad_s_out_rx_F1") (pintype "passive"))
    )
    (net (code "264") (name "/sig_W5") (class "Default")
      (node (ref "J1") (pin "W5") (pintype "input"))
      (node (ref "U1") (pin "L10") (pinfunction "signal_PD_anode_1_v_E5_L10") (pintype "input"))
      (node (ref "U2") (pin "59") (pinfunction "IBIAS_0__5_59") (pintype "passive"))
      (node (ref "U5") (pin "T4") (pinfunction "s_out_2_T4") (pintype "input"))
      (node (ref "U6") (pin "F7") (pinfunction "VB_RING_F7") (pintype "passive"))
    )
    (net (code "265") (name "/sig_W6") (class "Default")
      (node (ref "J1") (pin "W6") (pintype "input"))
      (node (ref "U1") (pin "K11") (pinfunction "through_PD_anode_v_E12_K11") (pintype "input"))
      (node (ref "U2") (pin "64") (pinfunction "H_2__5_64") (pintype "passive"))
      (node (ref "U4") (pin "N10") (pinfunction "AnalogLinks_TxIn_2_N_N10") (pintype "input"))
    )
    (net (code "266") (name "/sig_W7") (class "Default")
      (node (ref "J1") (pin "W7") (pintype "input"))
      (node (ref "U1") (pin "M9") (pinfunction "Idler_HeaterLabelRight_ring_2_v_E5_M9") (pintype "input"))
      (node (ref "U2") (pin "61") (pinfunction "IBIAS_2__5_61") (pintype "passive"))
      (node (ref "U4") (pin "M10") (pinfunction "AnalogLinks_TxIn_2_P_M10") (pintype "input"))
    )
    (net (code "267") (name "/sig_W8") (class "Default")
      (node (ref "J1") (pin "W8") (pintype "input"))
      (node (ref "U1") (pin "I11") (pinfunction "debug_PD_anode_v_E12_I11") (pintype "input"))
      (node (ref "U2") (pin "78") (pinfunction "IBIAS_3__6_78") (pintype "passive"))
      (node (ref "U4") (pin "N11") (pinfunction "AnalogLinks_Rx_2_N_N11") (pintype "input"))
    )
    (net (code "268") (name "/sig_W9") (class "Default")
      (node (ref "J1") (pin "W9") (pintype "input"))
      (node (ref "U1") (pin "N8") (pinfunction "Signal_HeaterLabelRight_ring_3_v_E5_N8") (pintype "input"))
      (node (ref "U2") (pin "80") (pinfunction "H_2__6_80") (pintype "passive"))
      (node (ref "U4") (pin "M11") (pinfunction "AnalogLinks_Rx_2_P_M11") (pintype "input"))
    )
    (net (code "269") (name "/sig_W10") (class "Default")
      (node (ref "J1") (pin "W10") (pintype "input"))
      (node (ref "U1") (pin "H11") (pinfunction "ASE_anode_1_v_E12_H11") (pintype "input"))
      (node (ref "U2") (pin "75") (pinfunction "IBIAS_0__6_75") (pintype "passive"))
      (node (ref "U4") (pin "L10") (pinfunction "AnalogLinks_TxIn_3_N_L10") (pintype "input"))
    )
    (net (code "270") (name "/sig_W11") (class "Default")
      (node (ref "J1") (pin "W11") (pintype "input"))
      (node (ref "U1") (pin "H9") (pinfunction "Idler_HeaterLabelRight_ring_1_v_E12_H9") (pintype "input"))
      (node (ref "U2") (pin "89") (pinfunction "IBIAS_1__7_89") (pintype "passive"))
      (node (ref "U4") (pin "K10") (pinfunction "AnalogLinks_TxIn_3_P_K10") (pintype "input"))
    )
    (net (code "271") (name "/sig_W12") (class "Default")
      (node (ref "J1") (pin "W12") (pintype "input"))
      (node (ref "U1") (pin "G11") (pinfunction "ASE_anode_0_v_E12_G11") (pintype "input"))
      (node (ref "U2") (pin "94") (pinfunction "H_3__7_94") (pintype "passive"))
      (node (ref "U4") (pin "J10") (pinfunction "AnalogLinks_TxIn_4_N_J10") (pintype "input"))
    )
    (net (code "272") (name "/sig_W13") (class "Default")
      (node (ref "J1") (pin "W13") (pintype "input"))
      (node (ref "U1") (pin "E11") (pinfunction "input_PD_anode_v_E12_E11") (pintype "input"))
      (node (ref "U2") (pin "110") (pinfunction "H_3__8_110") (pintype "passive"))
      (node (ref "U4") (pin "I10") (pinfunction "AnalogLinks_TxIn_4_P_I10") (pintype "input"))
    )
    (net (code "273") (name "/sig_W14") (class "Default")
      (node (ref "J1") (pin "W14") (pintype "input"))
      (node (ref "U1") (pin "E10") (pinfunction "idler_PD_anode_1_v_E12_E10") (pintype "input"))
      (node (ref "U2") (pin "105") (pinfunction "IBIAS_1__8_105") (pintype "passive"))
      (node (ref "U4") (pin "J11") (pinfunction "AnalogLinks_Rx_4_N_J11") (pintype "input"))
    )
    (net (code "274") (name "/sig_W15") (class "Default")
      (node (ref "J1") (pin "W15") (pintype "input"))
      (node (ref "U1") (pin "D11") (pinfunction "Pulse_curverAndPD_cathode_v_E12__all_cathodes_D11") (pintype "input"))
      (node (ref "U2") (pin "117") (pinfunction "IBIAS_0__9_117") (pintype "passive"))
      (node (ref "U4") (pin "I11") (pinfunction "AnalogLinks_Rx_4_P_I11") (pintype "input"))
    )
    (net (code "275") (name "/sig_W16") (class "Default")
      (node (ref "J1") (pin "W16") (pintype "input"))
      (node (ref "U1") (pin "D10") (pinfunction "idler_PD_anode_0_v_E12_D10") (pintype "input"))
      (node (ref "U2") (pin "122") (pinfunction "H_2__9_122") (pintype "passive"))
      (node (ref "U4") (pin "H10") (pinfunction "AnalogLinks_TxIn_5_N_H10") (pintype "input"))
    )
    (net (code "276") (name "/sig_W17") (class "Default")
      (node (ref "J1") (pin "W17") (pintype "input"))
      (node (ref "U1") (pin "B11") (pinfunction "signal_PD_anode_3_v_E12_B11") (pintype "input"))
      (node (ref "U2") (pin "120") (pinfunction "IBIAS_3__9_120") (pintype "passive"))
      (node (ref "U4") (pin "E11") (pinfunction "AnalogLinks_Rx_6_P_E11") (pintype "input"))
    )
    (net (code "277") (name "/sig_W18") (class "Default")
      (node (ref "J1") (pin "W18") (pintype "input"))
      (node (ref "U1") (pin "B10") (pinfunction "signal_PD_anode_1_v_E12_B10") (pintype "input"))
      (node (ref "U2") (pin "136") (pinfunction "IBIAS_3__10_136") (pintype "passive"))
      (node (ref "U4") (pin "D10") (pinfunction "AnalogLinks_TxIn_7_N_D10") (pintype "input"))
    )
    (net (code "278") (name "/sig_W19") (class "Default")
      (node (ref "J1") (pin "W19") (pintype "input"))
      (node (ref "U1") (pin "D9") (pinfunction "Idler_HeaterLabelRight_ring_2_v_E12_D9") (pintype "input"))
      (node (ref "U2") (pin "139") (pinfunction "H_3__10_139") (pintype "passive"))
      (node (ref "U4") (pin "D11") (pinfunction "AnalogLinks_Rx_7_N_D11") (pintype "input"))
    )
    (net (code "279") (name "/us__CML_clk_n") (class "Default")
      (node (ref "J1") (pin "D6") (pintype "input"))
      (node (ref "U5") (pin "K1") (pinfunction "CML_clkn_K1") (pintype "input"))
    )
    (net (code "280") (name "/us__CML_clk_p") (class "Default")
      (node (ref "J1") (pin "D5") (pintype "input"))
      (node (ref "U5") (pin "K2") (pinfunction "CML_clkp_K2") (pintype "input"))
    )
    (net (code "281") (name "/us__rx_out_0_n") (class "Default")
      (node (ref "J1") (pin "D4") (pintype "input"))
      (node (ref "U5") (pin "O2") (pinfunction "rx_out_n_0_O2") (pintype "input"))
    )
    (net (code "282") (name "/us__rx_out_0_p") (class "Default")
      (node (ref "J1") (pin "E4") (pintype "input"))
      (node (ref "U5") (pin "O1") (pinfunction "rx_out_p_0_O1") (pintype "input"))
    )
    (net (code "283") (name "/us__rx_out_1_n") (class "Default")
      (node (ref "J1") (pin "E12") (pintype "input"))
      (node (ref "U5") (pin "G1") (pinfunction "rx_out_n_1_G1") (pintype "input"))
    )
    (net (code "284") (name "/us__rx_out_1_p") (class "Default")
      (node (ref "J1") (pin "E11") (pintype "input"))
      (node (ref "U5") (pin "G2") (pinfunction "rx_out_p_1_G2") (pintype "input"))
    )
    (net (code "285") (name "/us__rx_out_2_n") (class "Default")
      (node (ref "J1") (pin "D12") (pintype "input"))
      (node (ref "U5") (pin "F1") (pinfunction "rx_out_n_2_F1") (pintype "input"))
    )
    (net (code "286") (name "/us__rx_out_2_p") (class "Default")
      (node (ref "J1") (pin "D11") (pintype "input"))
      (node (ref "U5") (pin "F2") (pinfunction "rx_out_p_2_F2") (pintype "input"))
    )
    (net (code "287") (name "/us__rx_out_3_n") (class "Default")
      (node (ref "J1") (pin "M5") (pintype "input"))
      (node (ref "U5") (pin "P2") (pinfunction "rx_out_n_3_P2") (pintype "input"))
    )
    (net (code "288") (name "/us__rx_out_3_p") (class "Default")
      (node (ref "J1") (pin "M4") (pintype "input"))
      (node (ref "U5") (pin "P1") (pinfunction "rx_out_p_3_P1") (pintype "input"))
    )
    (net (code "289") (name "/us__rx_out_4_n") (class "Default")
      (node (ref "J1") (pin "K4") (pintype "input"))
      (node (ref "U5") (pin "Q2") (pinfunction "rx_out_n_4_Q2") (pintype "input"))
    )
    (net (code "290") (name "/us__rx_out_4_p") (class "Default")
      (node (ref "J1") (pin "L4") (pintype "input"))
      (node (ref "U5") (pin "Q1") (pinfunction "rx_out_p_4_Q1") (pintype "input"))
    )
    (net (code "291") (name "/us__rx_out_5_n") (class "Default")
      (node (ref "J1") (pin "D10") (pintype "input"))
      (node (ref "U5") (pin "E1") (pinfunction "rx_out_n_5_E1") (pintype "input"))
    )
    (net (code "292") (name "/us__rx_out_5_p") (class "Default")
      (node (ref "J1") (pin "D9") (pintype "input"))
      (node (ref "U5") (pin "E2") (pinfunction "rx_out_p_5_E2") (pintype "input"))
    )
    (net (code "293") (name "/us__rx_out_6_n") (class "Default")
      (node (ref "J1") (pin "D8") (pintype "input"))
      (node (ref "U5") (pin "D1") (pinfunction "rx_out_n_6_D1") (pintype "input"))
    )
    (net (code "294") (name "/us__rx_out_6_p") (class "Default")
      (node (ref "J1") (pin "D7") (pintype "input"))
      (node (ref "U5") (pin "D2") (pinfunction "rx_out_p_6_D2") (pintype "input"))
    )
    (net (code "295") (name "/us__rx_out_7_n") (class "Default")
      (node (ref "J1") (pin "K5") (pintype "input"))
      (node (ref "U5") (pin "R2") (pinfunction "rx_out_n_7_R2") (pintype "input"))
    )
    (net (code "296") (name "/us__rx_out_7_p") (class "Default")
      (node (ref "J1") (pin "L5") (pintype "input"))
      (node (ref "U5") (pin "R1") (pinfunction "rx_out_p_7_R1") (pintype "input"))
    )
    (net (code "297") (name "/us__rx_out_8_n") (class "Default")
      (node (ref "J1") (pin "J5") (pintype "input"))
      (node (ref "U5") (pin "L11") (pinfunction "rx_out_n_8_L11") (pintype "input"))
    )
    (net (code "298") (name "/us__rx_out_8_p") (class "Default")
      (node (ref "J1") (pin "H5") (pintype "input"))
      (node (ref "U5") (pin "K11") (pinfunction "rx_out_p_8_K11") (pintype "input"))
    )
    (net (code "299") (name "/us__rx_out_9_n") (class "Default")
      (node (ref "J1") (pin "E8") (pintype "input"))
      (node (ref "U5") (pin "A9") (pinfunction "rx_out_n_9_A9") (pintype "input"))
    )
    (net (code "300") (name "/us__rx_out_9_p") (class "Default")
      (node (ref "J1") (pin "E7") (pintype "input"))
      (node (ref "U5") (pin "A8") (pinfunction "rx_out_p_9_A8") (pintype "input"))
    )
    (net (code "301") (name "/us__rx_out_10_n") (class "Default")
      (node (ref "J1") (pin "E9") (pintype "input"))
      (node (ref "U5") (pin "A11") (pinfunction "rx_out_n_10_A11") (pintype "input"))
    )
    (net (code "302") (name "/us__rx_out_10_p") (class "Default")
      (node (ref "J1") (pin "E10") (pintype "input"))
      (node (ref "U5") (pin "A10") (pinfunction "rx_out_p_10_A10") (pintype "input"))
    )
    (net (code "303") (name "/us__rx_out_11_n") (class "Default")
      (node (ref "J1") (pin "G5") (pintype "input"))
      (node (ref "U5") (pin "J11") (pinfunction "rx_out_n_11_J11") (pintype "input"))
    )
    (net (code "304") (name "/us__rx_out_11_p") (class "Default")
      (node (ref "J1") (pin "F5") (pintype "input"))
      (node (ref "U5") (pin "I11") (pinfunction "rx_out_p_11_I11") (pintype "input"))
    )
    (net (code "305") (name "/us__rx_out_12_n") (class "Default")
      (node (ref "J1") (pin "G4") (pintype "input"))
      (node (ref "U5") (pin "P11") (pinfunction "rx_out_n_12_P11") (pintype "input"))
    )
    (net (code "306") (name "/us__rx_out_12_p") (class "Default")
      (node (ref "J1") (pin "F4") (pintype "input"))
      (node (ref "U5") (pin "O11") (pinfunction "rx_out_p_12_O11") (pintype "input"))
    )
    (net (code "307") (name "/us__rx_out_13_n") (class "Default")
      (node (ref "J1") (pin "E5") (pintype "input"))
      (node (ref "U5") (pin "E11") (pinfunction "rx_out_n_13_E11") (pintype "input"))
    )
    (net (code "308") (name "/us__rx_out_13_p") (class "Default")
      (node (ref "J1") (pin "E6") (pintype "input"))
      (node (ref "U5") (pin "D11") (pinfunction "rx_out_p_13_D11") (pintype "input"))
    )
    (net (code "309") (name "/us__rx_out_14_n") (class "Default")
      (node (ref "J1") (pin "J4") (pintype "input"))
      (node (ref "U5") (pin "R11") (pinfunction "rx_out_n_14_R11") (pintype "input"))
    )
    (net (code "310") (name "/us__rx_out_14_p") (class "Default")
      (node (ref "J1") (pin "H4") (pintype "input"))
      (node (ref "U5") (pin "Q11") (pinfunction "rx_out_p_14_Q11") (pintype "input"))
    )
    (net (code "311") (name "unconnected-(U2D-NC_0__DEEMB-Pad404)") (class "Default")
      (node (ref "U2") (pin "404") (pinfunction "NC_0__DEEMB_404") (pintype "passive+no_connect"))
    )
    (net (code "312") (name "unconnected-(U2D-NC__C_0-Pad349)") (class "Default")
      (node (ref "U2") (pin "349") (pinfunction "NC__C_0_349") (pintype "passive+no_connect"))
    )
    (net (code "313") (name "unconnected-(U2D-NC__C_1-Pad350)") (class "Default")
      (node (ref "U2") (pin "350") (pinfunction "NC__C_1_350") (pintype "passive+no_connect"))
    )
    (net (code "314") (name "unconnected-(U2D-NC__C_2-Pad351)") (class "Default")
      (node (ref "U2") (pin "351") (pinfunction "NC__C_2_351") (pintype "passive+no_connect"))
    )
    (net (code "315") (name "unconnected-(U2D-NC__C_5-Pad354)") (class "Default")
      (node (ref "U2") (pin "354") (pinfunction "NC__C_5_354") (pintype "passive+no_connect"))
    )
    (net (code "316") (name "unconnected-(U2D-NC__C_6-Pad355)") (class "Default")
      (node (ref "U2") (pin "355") (pinfunction "NC__C_6_355") (pintype "passive+no_connect"))
    )
    (net (code "317") (name "unconnected-(U2D-NC__C_11-Pad360)") (class "Default")
      (node (ref "U2") (pin "360") (pinfunction "NC__C_11_360") (pintype "passive+no_connect"))
    )
    (net (code "318") (name "unconnected-(U2D-NC__C_12-Pad361)") (class "Default")
      (node (ref "U2") (pin "361") (pinfunction "NC__C_12_361") (pintype "passive+no_connect"))
    )
    (net (code "319") (name "unconnected-(U2D-NC__C_13-Pad362)") (class "Default")
      (node (ref "U2") (pin "362") (pinfunction "NC__C_13_362") (pintype "passive+no_connect"))
    )
    (net (code "320") (name "unconnected-(U2D-NC__C_14-Pad363)") (class "Default")
      (node (ref "U2") (pin "363") (pinfunction "NC__C_14_363") (pintype "passive+no_connect"))
    )
    (net (code "321") (name "unconnected-(U2D-NC__C_15-Pad364)") (class "Default")
      (node (ref "U2") (pin "364") (pinfunction "NC__C_15_364") (pintype "passive+no_connect"))
    )
    (net (code "322") (name "unconnected-(U2D-NC__C_17-Pad366)") (class "Default")
      (node (ref "U2") (pin "366") (pinfunction "NC__C_17_366") (pintype "passive+no_connect"))
    )
  )
)
